# Welder_PSU.net
KiCad netlist of a schematic drawn in EAGLE
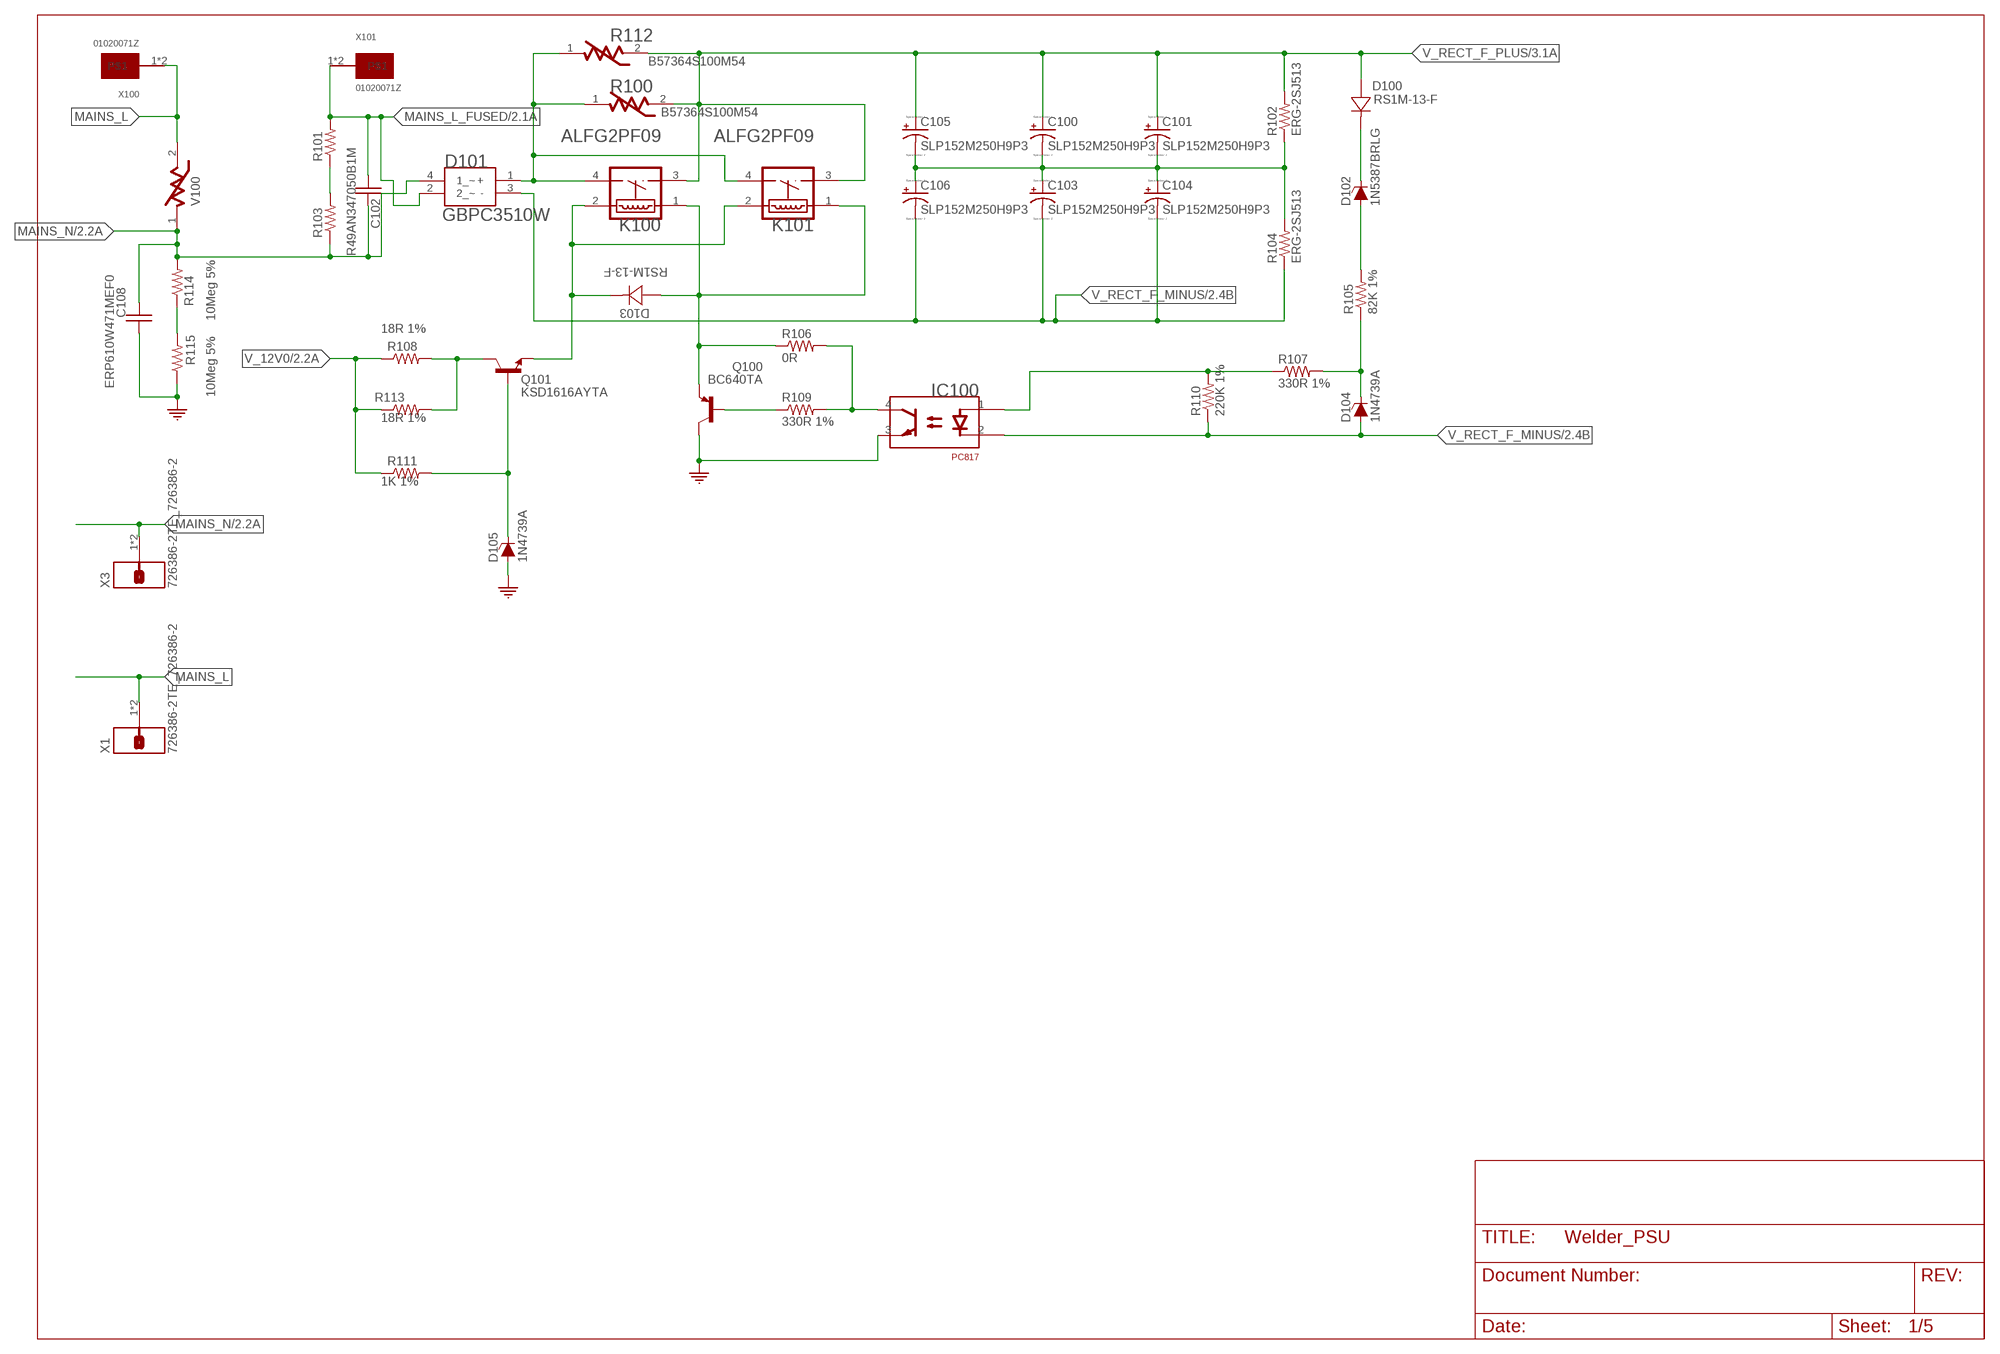
[diagram p0: schematic, sheet 1]
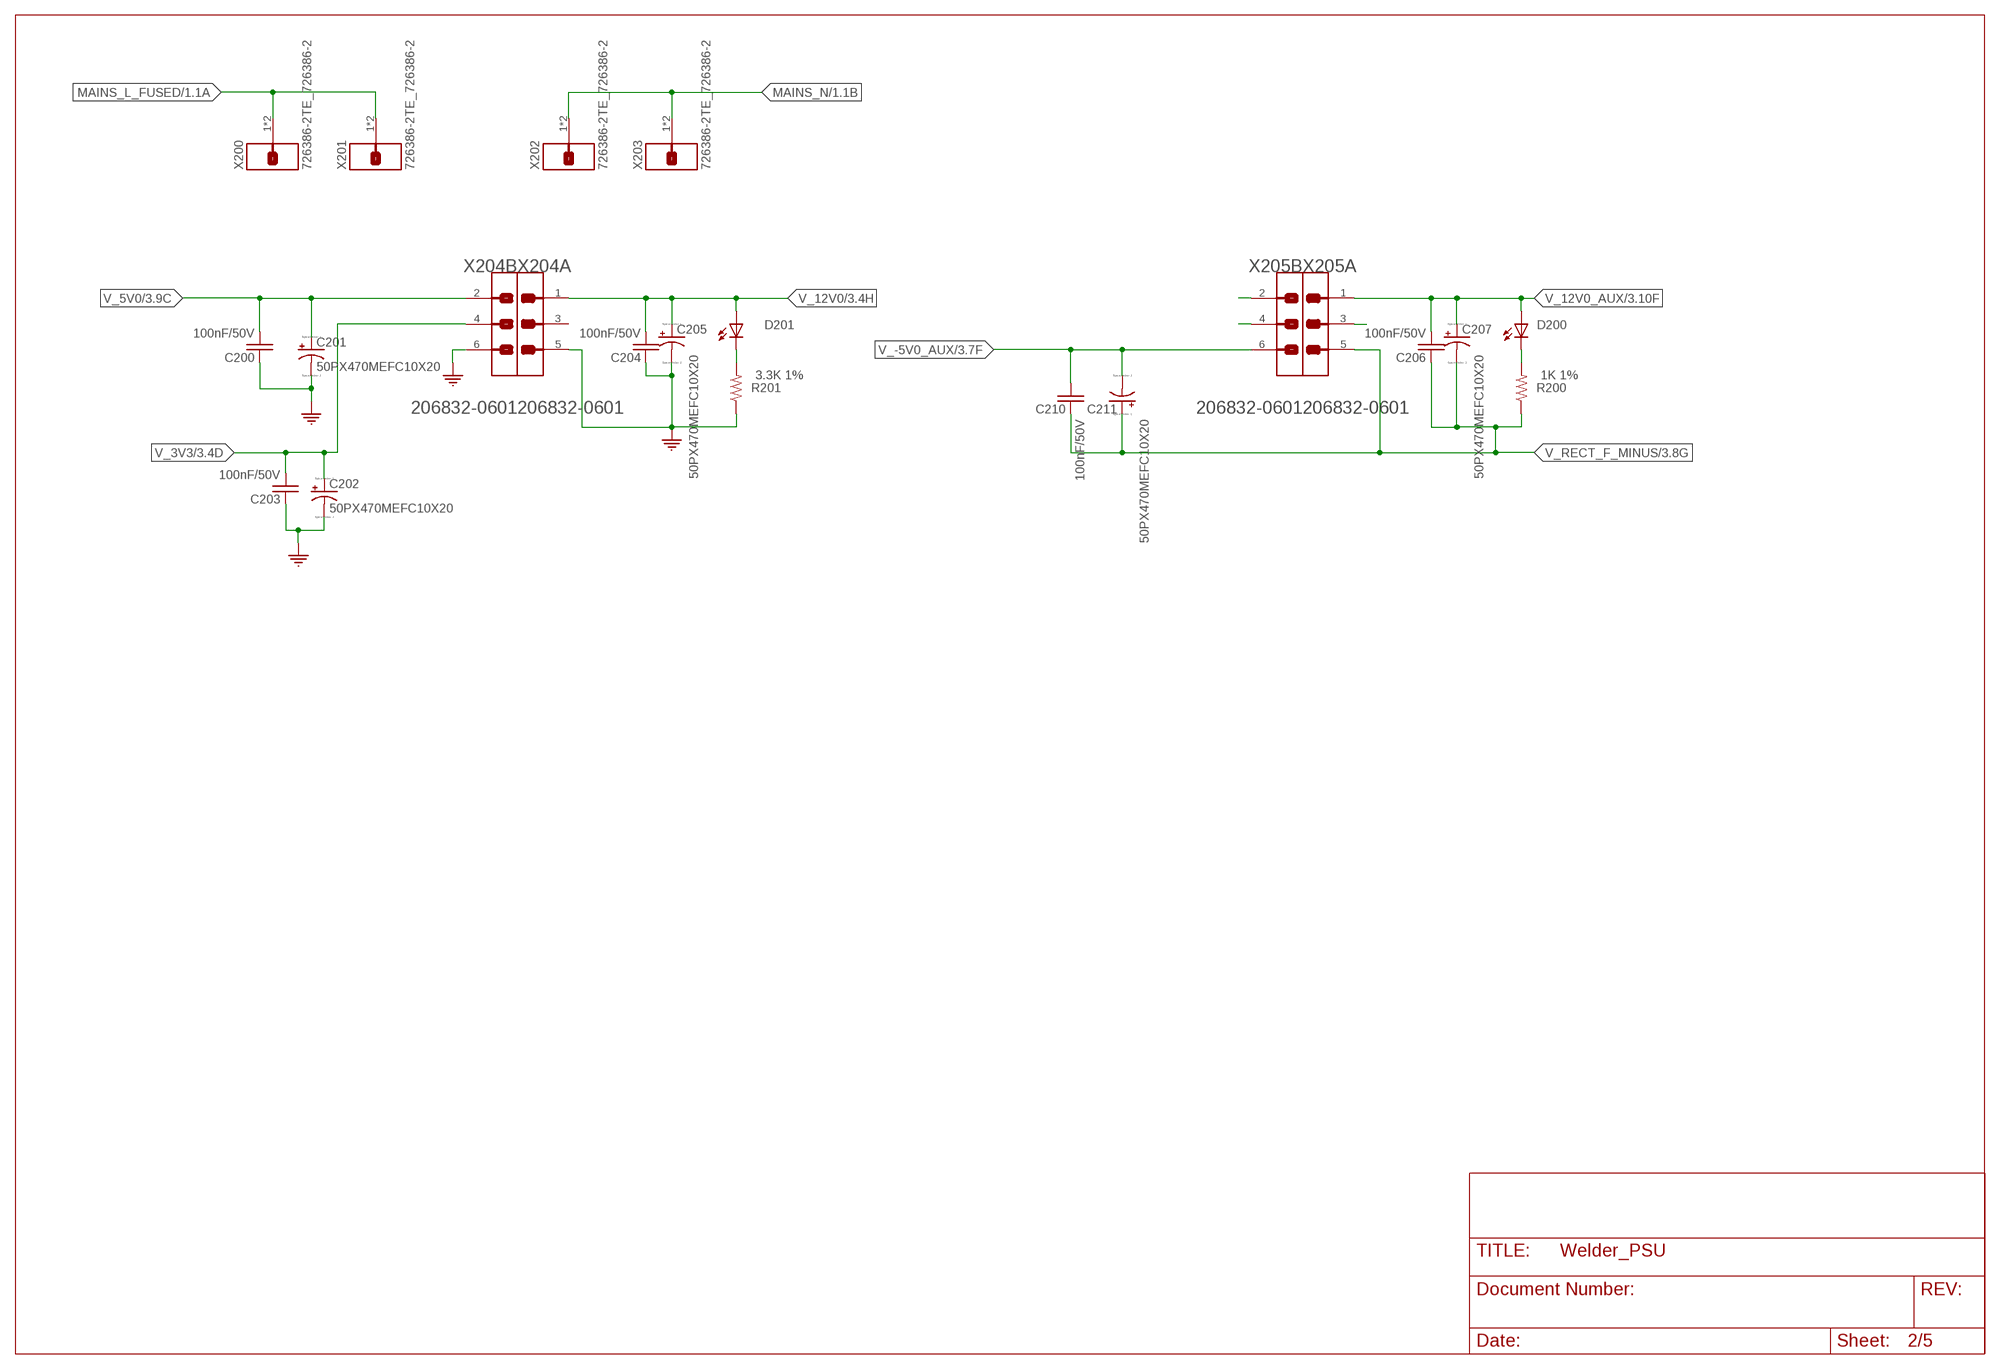
[diagram p1: schematic, sheet 2]
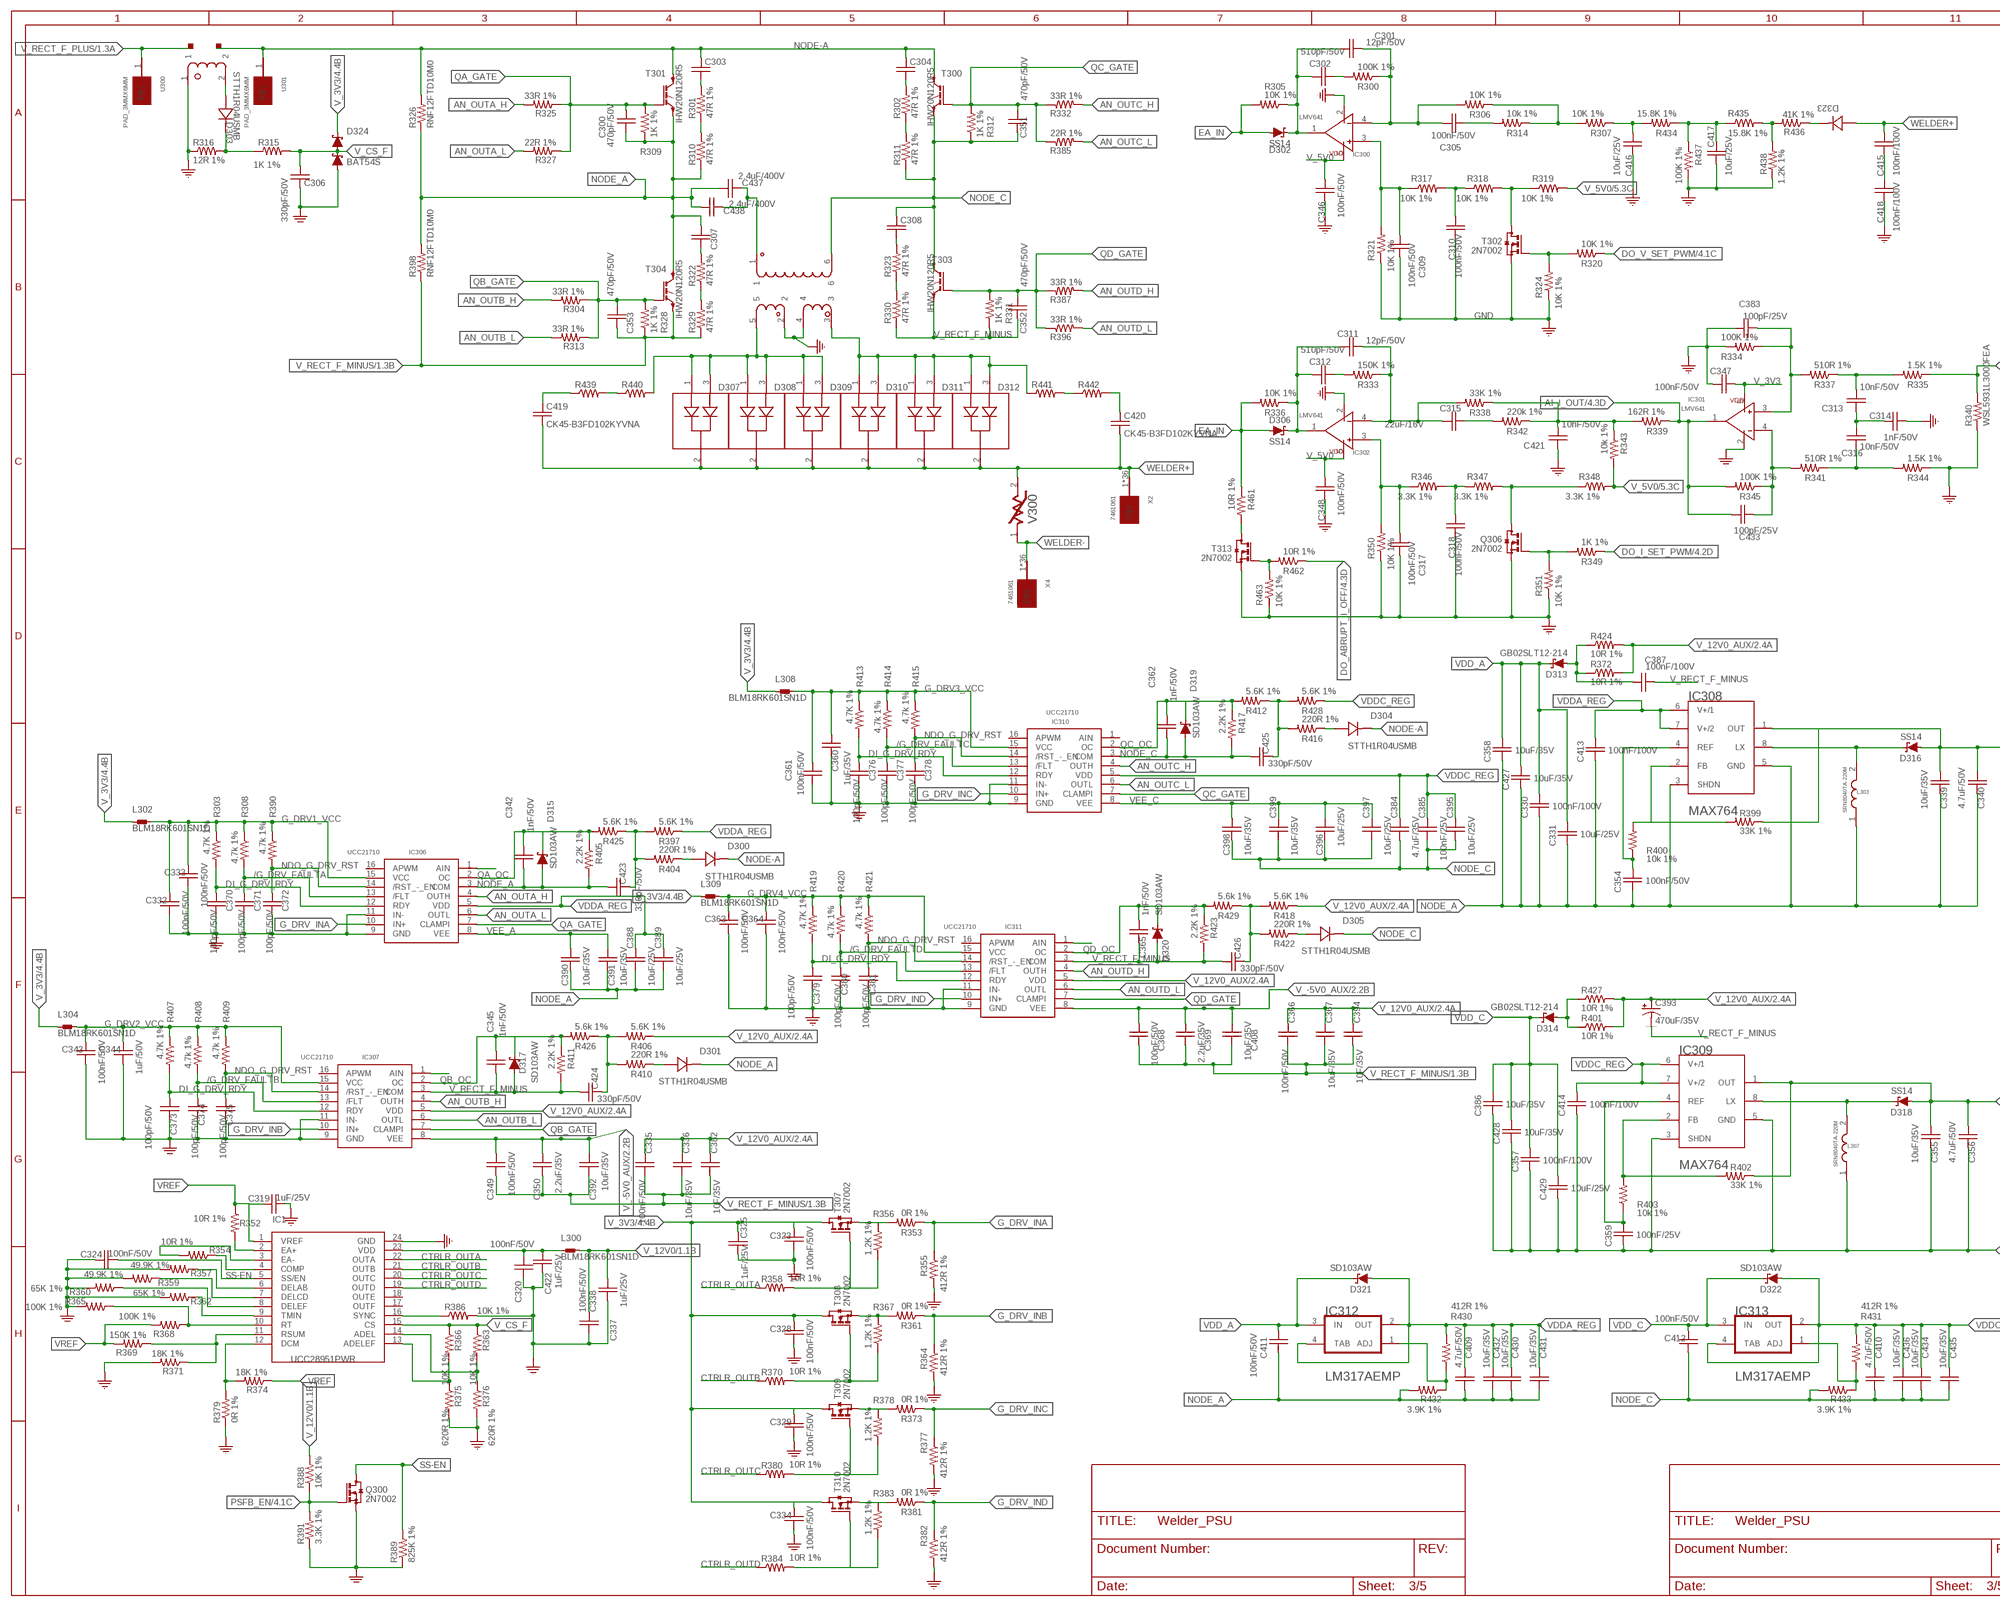
[diagram p2: schematic, sheet 3, part 1 of 2]
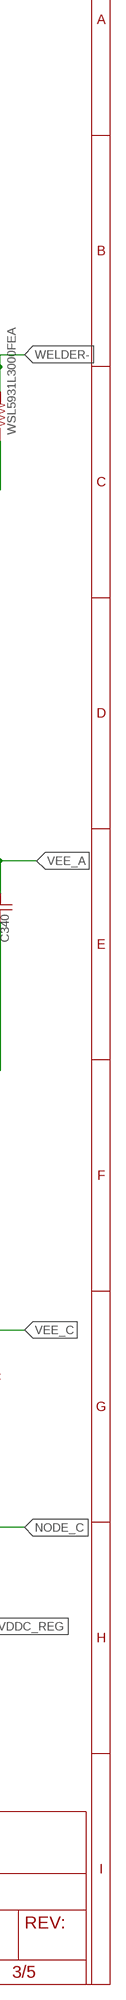
[diagram p3: schematic, sheet 3, part 2 of 2]
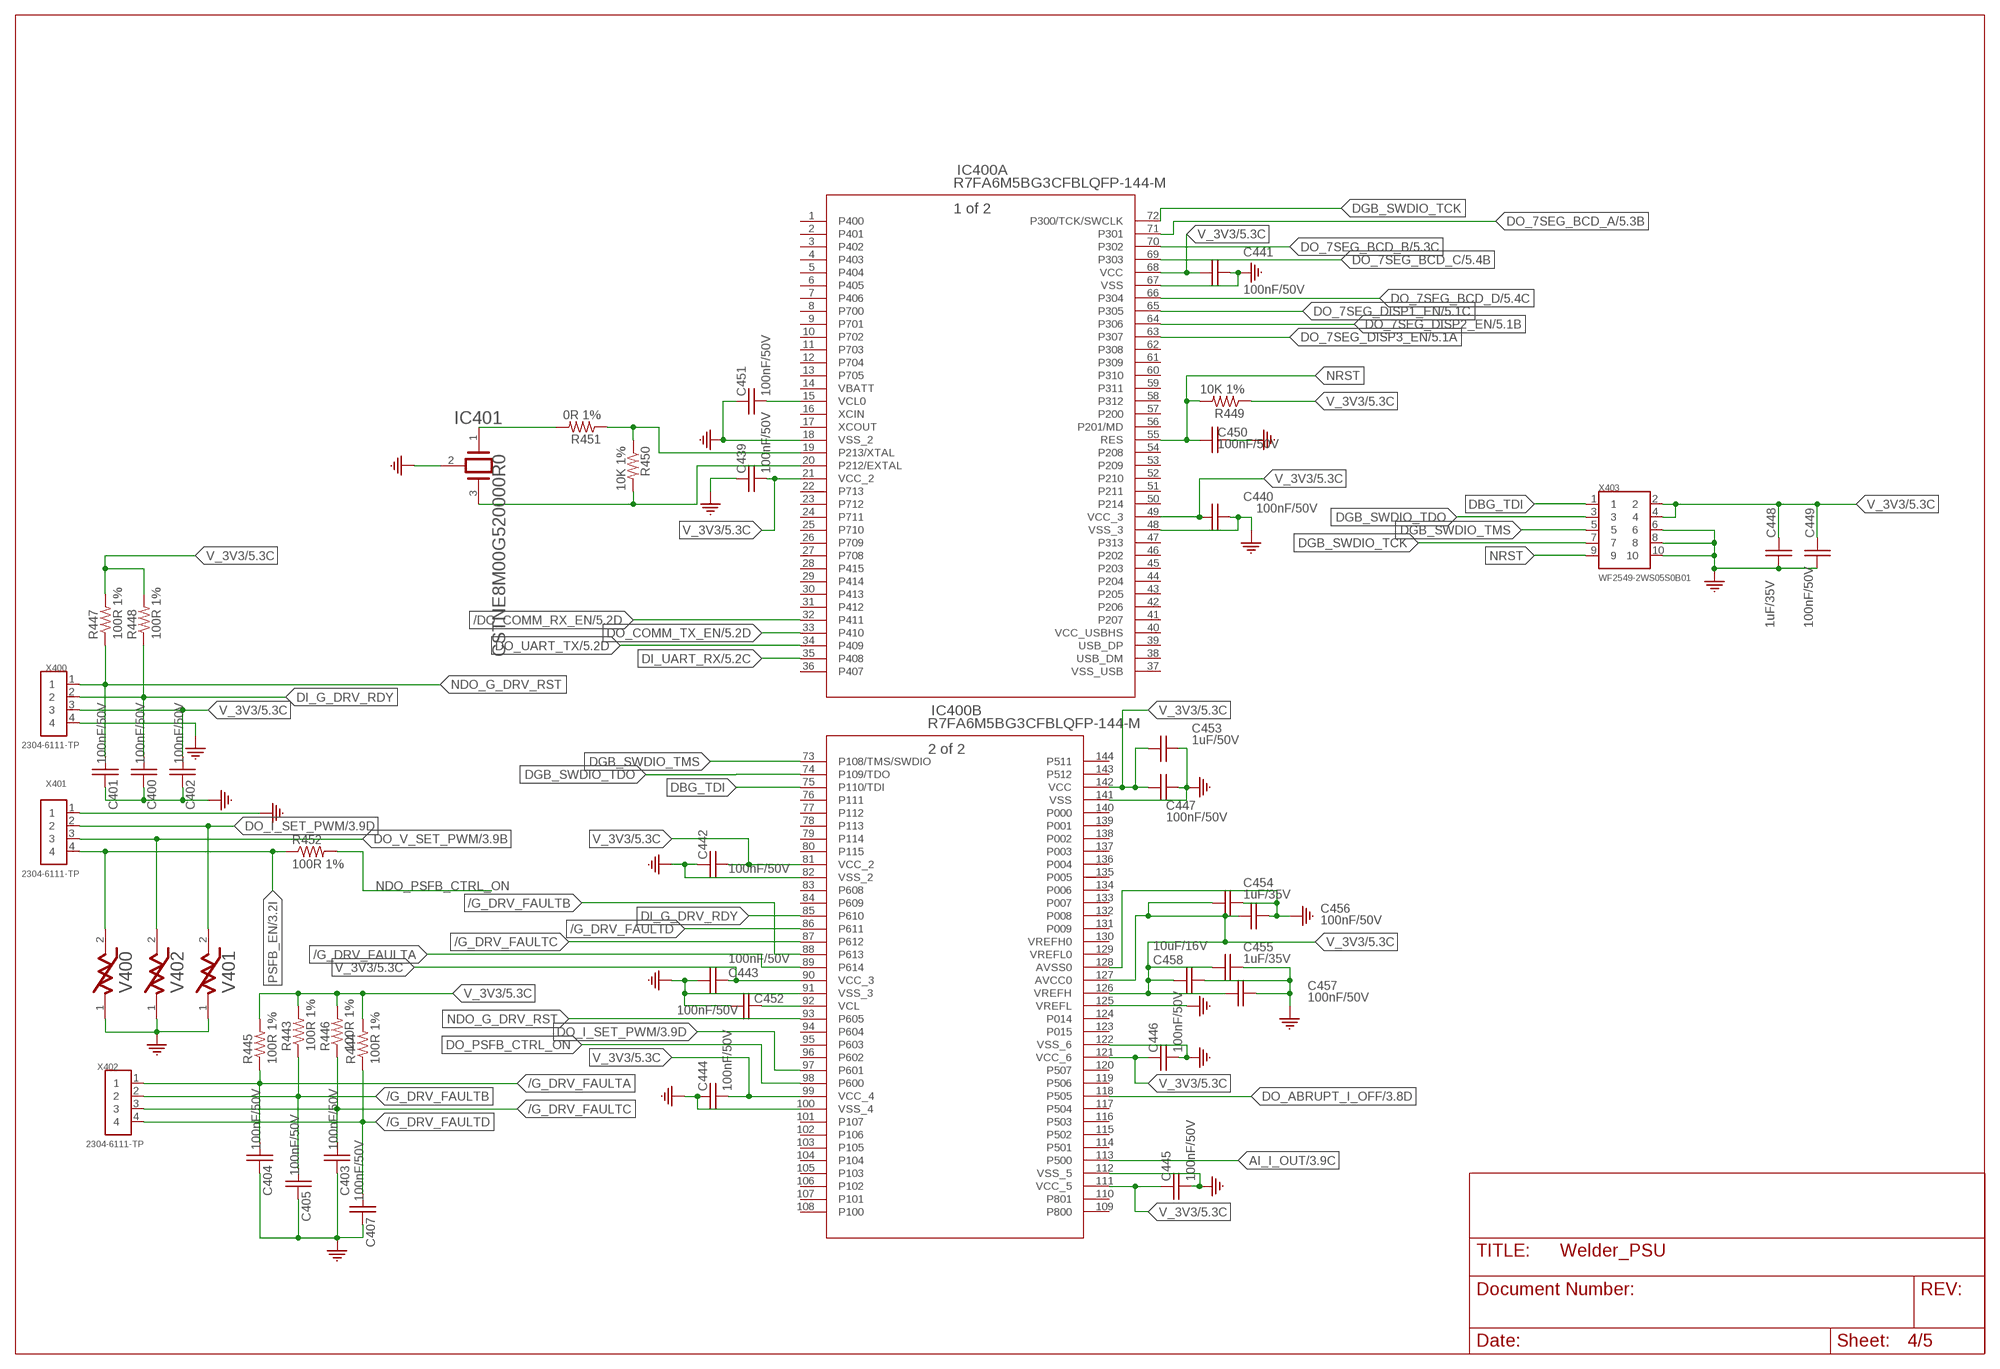
[diagram p4: schematic, sheet 4]
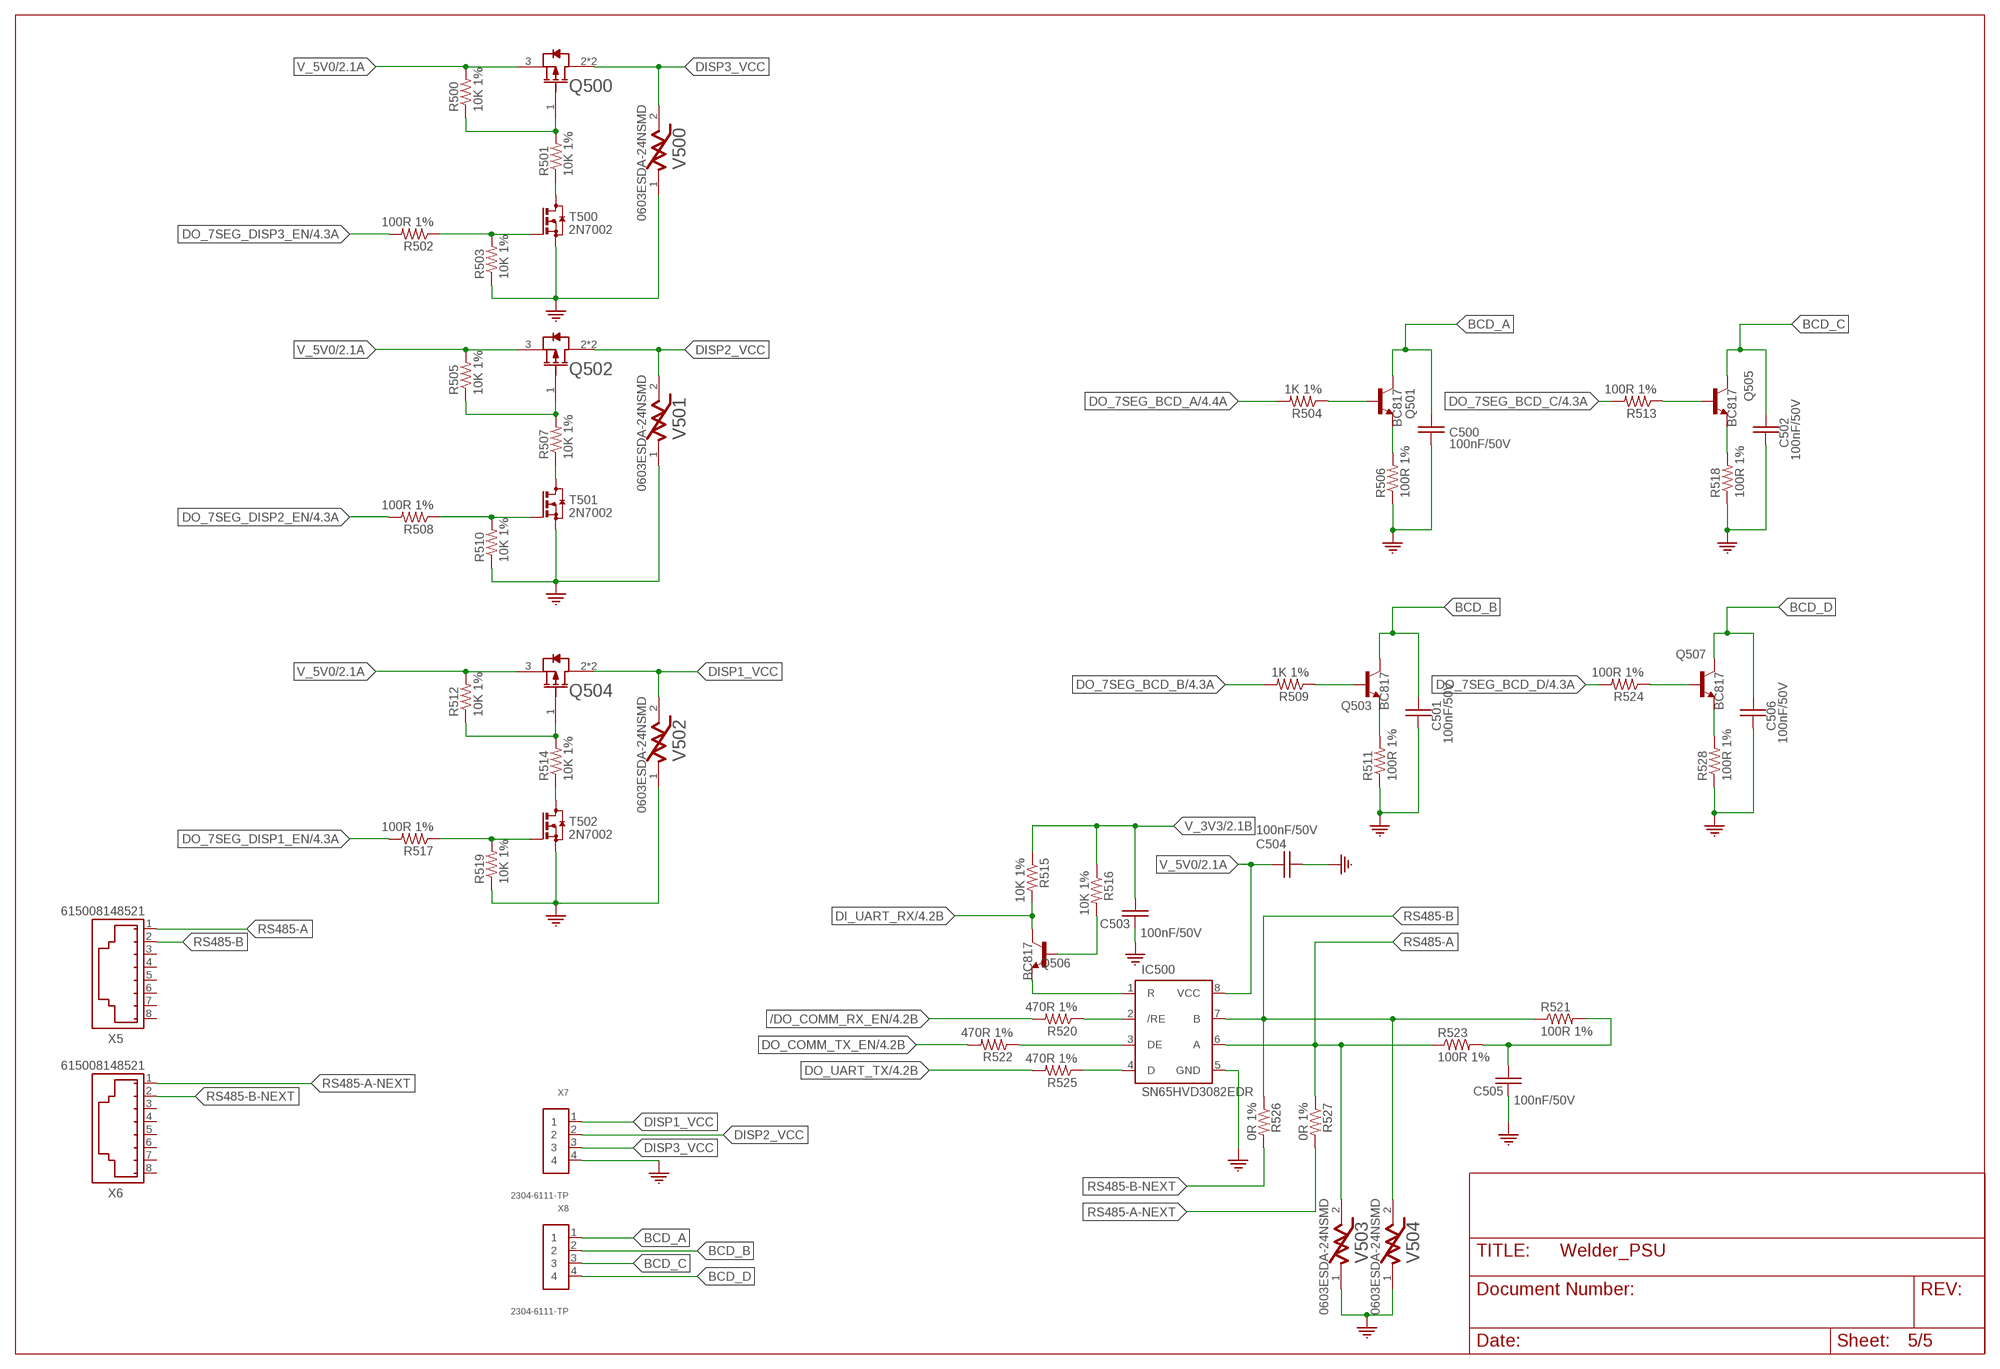
[diagram p5: schematic, sheet 5]

(export (version "E")
  (design (tool "Eeschema 10.0.6"))
  (components
    (comp (ref "C400")
      (value "100nF/50V")
      (footprint "eagle-import:EIA0603")
      (libsource (lib "eagle-import") (part "C_0603EIA0603"))
    )
    (comp (ref "C401")
      (value "100nF/50V")
      (footprint "eagle-import:EIA0603")
      (libsource (lib "eagle-import") (part "C_0603EIA0603"))
    )
    (comp (ref "C402")
      (value "100nF/50V")
      (footprint "eagle-import:EIA0603")
      (libsource (lib "eagle-import") (part "C_0603EIA0603"))
    )
    (comp (ref "C403")
      (value "100nF/50V")
      (footprint "eagle-import:EIA0603")
      (libsource (lib "eagle-import") (part "C_0603EIA0603"))
    )
    (comp (ref "C404")
      (value "100nF/50V")
      (footprint "eagle-import:EIA0603")
      (libsource (lib "eagle-import") (part "C_0603EIA0603"))
    )
    (comp (ref "C405")
      (value "100nF/50V")
      (footprint "eagle-import:EIA0603")
      (libsource (lib "eagle-import") (part "C_0603EIA0603"))
    )
    (comp (ref "C407")
      (value "100nF/50V")
      (footprint "eagle-import:EIA0603")
      (libsource (lib "eagle-import") (part "C_0603EIA0603"))
    )
    (comp (ref "C439")
      (value "100nF/50V")
      (footprint "eagle-import:EIA0603")
      (libsource (lib "eagle-import") (part "C_0603EIA0603"))
    )
    (comp (ref "C440")
      (value "100nF/50V")
      (footprint "eagle-import:EIA0603")
      (libsource (lib "eagle-import") (part "C_0603EIA0603"))
    )
    (comp (ref "C441")
      (value "100nF/50V")
      (footprint "eagle-import:EIA0603")
      (libsource (lib "eagle-import") (part "C_0603EIA0603"))
    )
    (comp (ref "C442")
      (value "100nF/50V")
      (footprint "eagle-import:EIA0603")
      (libsource (lib "eagle-import") (part "C_0603EIA0603"))
    )
    (comp (ref "C443")
      (value "100nF/50V")
      (footprint "eagle-import:EIA0603")
      (libsource (lib "eagle-import") (part "C_0603EIA0603"))
    )
    (comp (ref "C444")
      (value "100nF/50V")
      (footprint "eagle-import:EIA0603")
      (libsource (lib "eagle-import") (part "C_0603EIA0603"))
    )
    (comp (ref "C445")
      (value "100nF/50V")
      (footprint "eagle-import:EIA0603")
      (libsource (lib "eagle-import") (part "C_0603EIA0603"))
    )
    (comp (ref "C446")
      (value "100nF/50V")
      (footprint "eagle-import:EIA0603")
      (libsource (lib "eagle-import") (part "C_0603EIA0603"))
    )
    (comp (ref "C447")
      (value "100nF/50V")
      (footprint "eagle-import:EIA0603")
      (libsource (lib "eagle-import") (part "C_0603EIA0603"))
    )
    (comp (ref "C448")
      (value "1uF/35V")
      (footprint "eagle-import:EIA0603")
      (libsource (lib "eagle-import") (part "C_0603EIA0603"))
    )
    (comp (ref "C449")
      (value "100nF/50V")
      (footprint "eagle-import:EIA0603")
      (libsource (lib "eagle-import") (part "C_0603EIA0603"))
    )
    (comp (ref "C450")
      (value "100nF/50V")
      (footprint "eagle-import:EIA0603")
      (libsource (lib "eagle-import") (part "C_0603EIA0603"))
    )
    (comp (ref "C451")
      (value "100nF/50V")
      (footprint "eagle-import:EIA0603")
      (libsource (lib "eagle-import") (part "C_0603EIA0603"))
    )
    (comp (ref "C452")
      (value "100nF/50V")
      (footprint "eagle-import:EIA0603")
      (libsource (lib "eagle-import") (part "C_0603EIA0603"))
    )
    (comp (ref "C453")
      (value "1uF/50V")
      (footprint "eagle-import:EIA0603")
      (libsource (lib "eagle-import") (part "C_0603EIA0603"))
    )
    (comp (ref "C454")
      (value "1uF/35V")
      (footprint "eagle-import:EIA0603")
      (libsource (lib "eagle-import") (part "C_0603EIA0603"))
    )
    (comp (ref "C455")
      (value "1uF/35V")
      (footprint "eagle-import:EIA0603")
      (libsource (lib "eagle-import") (part "C_0603EIA0603"))
    )
    (comp (ref "C456")
      (value "100nF/50V")
      (footprint "eagle-import:EIA0603")
      (libsource (lib "eagle-import") (part "C_0603EIA0603"))
    )
    (comp (ref "C457")
      (value "100nF/50V")
      (footprint "eagle-import:EIA0603")
      (libsource (lib "eagle-import") (part "C_0603EIA0603"))
    )
    (comp (ref "C458")
      (value "10uF/16V")
      (footprint "eagle-import:EIA0603")
      (libsource (lib "eagle-import") (part "C_0603EIA0603"))
    )
    (comp (ref "IC400")
      (value "R7FA6M5BG3CFBLQFP-144-M")
      (footprint "eagle-import:LQFP-144-M")
      (fields (field (name "MFR") "Renesas"))
      (libsource (lib "eagle-import") (part "R7FA6M5BG3CFBLQFP-144-M"))
    )
    (comp (ref "IC401")
      (value "CSTNE8M00G520000R0")
      (footprint "eagle-import:CSTNE8M00G520000R0")
      (fields (field (name "MFR") "Murata"))
      (libsource (lib "eagle-import") (part "CSTNE8M00G520000R0"))
    )
    (comp (ref "R443")
      (value "100R 1%")
      (footprint "eagle-import:EIA0603")
      (libsource (lib "eagle-import") (part "R_0603"))
    )
    (comp (ref "R444")
      (value "100R 1%")
      (footprint "eagle-import:EIA0603")
      (libsource (lib "eagle-import") (part "R_0603"))
    )
    (comp (ref "R445")
      (value "100R 1%")
      (footprint "eagle-import:EIA0603")
      (libsource (lib "eagle-import") (part "R_0603"))
    )
    (comp (ref "R446")
      (value "100R 1%")
      (footprint "eagle-import:EIA0603")
      (libsource (lib "eagle-import") (part "R_0603"))
    )
    (comp (ref "R447")
      (value "100R 1%")
      (footprint "eagle-import:EIA0603")
      (libsource (lib "eagle-import") (part "R_0603"))
    )
    (comp (ref "R448")
      (value "100R 1%")
      (footprint "eagle-import:EIA0603")
      (libsource (lib "eagle-import") (part "R_0603"))
    )
    (comp (ref "R449")
      (value "10K 1%")
      (footprint "eagle-import:EIA0603")
      (libsource (lib "eagle-import") (part "R_0603"))
    )
    (comp (ref "R450")
      (value "10K 1%")
      (footprint "eagle-import:EIA0603")
      (libsource (lib "eagle-import") (part "R_0603"))
    )
    (comp (ref "R451")
      (value "0R 1%")
      (footprint "eagle-import:EIA0603")
      (libsource (lib "eagle-import") (part "R_0603"))
    )
    (comp (ref "R452")
      (value "100R 1%")
      (footprint "eagle-import:EIA0603")
      (libsource (lib "eagle-import") (part "R_0603"))
    )
    (comp (ref "V400")
      (value "0603ESDA-24NSMD")
      (footprint "eagle-import:EIA0603")
      (fields (field (name "MFR") "Bourns"))
      (libsource (lib "eagle-import") (part "0603ESDA-24NSMD"))
    )
    (comp (ref "V401")
      (value "0603ESDA-24NSMD")
      (footprint "eagle-import:EIA0603")
      (fields (field (name "MFR") "Bourns"))
      (libsource (lib "eagle-import") (part "0603ESDA-24NSMD"))
    )
    (comp (ref "V402")
      (value "0603ESDA-24NSMD")
      (footprint "eagle-import:EIA0603")
      (fields (field (name "MFR") "Bourns"))
      (libsource (lib "eagle-import") (part "0603ESDA-24NSMD"))
    )
    (comp (ref "X400")
      (value "2304-6111-TP")
      (footprint "eagle-import:X04_100MIL")
      (fields (field (name "MFR") "3M"))
      (libsource (lib "eagle-import") (part "2304-6111-TP"))
    )
    (comp (ref "X401")
      (value "2304-6111-TP")
      (footprint "eagle-import:X04_100MIL")
      (fields (field (name "MFR") "3M"))
      (libsource (lib "eagle-import") (part "2304-6111-TP"))
    )
    (comp (ref "X402")
      (value "2304-6111-TP")
      (footprint "eagle-import:X04_100MIL")
      (fields (field (name "MFR") "3M"))
      (libsource (lib "eagle-import") (part "2304-6111-TP"))
    )
    (comp (ref "X403")
      (value "WF2549-2WS05S0B01")
      (footprint "eagle-import:X10_100MIL_2XROW_VERT")
      (fields (field (name "MFR") "WCON"))
      (libsource (lib "eagle-import") (part "WF2549-2WS05S0B01"))
    )
    (comp (ref "C200")
      (value "100nF/50V")
      (footprint "eagle-import:EIA0603")
      (libsource (lib "eagle-import") (part "C_0603EIA0603"))
    )
    (comp (ref "C201")
      (value "50PX470MEFC10X20")
      (footprint "eagle-import:CAPACITOR-ELKO-RM5-10X16")
      (fields (field (name "MFR") "Rubicon"))
      (libsource (lib "eagle-import") (part "50PX470MEFC10X20"))
    )
    (comp (ref "C202")
      (value "50PX470MEFC10X20")
      (footprint "eagle-import:CAPACITOR-ELKO-RM5-10X16")
      (fields (field (name "MFR") "Rubicon"))
      (libsource (lib "eagle-import") (part "50PX470MEFC10X20"))
    )
    (comp (ref "C203")
      (value "100nF/50V")
      (footprint "eagle-import:EIA0603")
      (libsource (lib "eagle-import") (part "C_0603EIA0603"))
    )
    (comp (ref "C204")
      (value "100nF/50V")
      (footprint "eagle-import:EIA0603")
      (libsource (lib "eagle-import") (part "C_0603EIA0603"))
    )
    (comp (ref "C205")
      (value "50PX470MEFC10X20")
      (footprint "eagle-import:CAPACITOR-ELKO-RM5-10X16")
      (fields (field (name "MFR") "Rubicon"))
      (libsource (lib "eagle-import") (part "50PX470MEFC10X20"))
    )
    (comp (ref "C206")
      (value "100nF/50V")
      (footprint "eagle-import:EIA0603")
      (libsource (lib "eagle-import") (part "C_0603EIA0603"))
    )
    (comp (ref "C207")
      (value "50PX470MEFC10X20")
      (footprint "eagle-import:CAPACITOR-ELKO-RM5-10X16")
      (fields (field (name "MFR") "Rubicon"))
      (libsource (lib "eagle-import") (part "50PX470MEFC10X20"))
    )
    (comp (ref "C210")
      (value "100nF/50V")
      (footprint "eagle-import:EIA0603")
      (libsource (lib "eagle-import") (part "C_0603EIA0603"))
    )
    (comp (ref "C211")
      (value "50PX470MEFC10X20")
      (footprint "eagle-import:CAPACITOR-ELKO-RM5-10X16")
      (fields (field (name "MFR") "Rubicon"))
      (libsource (lib "eagle-import") (part "50PX470MEFC10X20"))
    )
    (comp (ref "D200")
      (value "26-21/GPC-F3138B/CA")
      (footprint "eagle-import:SMD1206-LED")
      (fields (field (name "MFR") "Everlight"))
      (libsource (lib "eagle-import") (part "26-21/GPC-F3138B/CA"))
    )
    (comp (ref "D201")
      (value "26-21/GPC-F3138B/CA")
      (footprint "eagle-import:SMD1206-LED")
      (fields (field (name "MFR") "Everlight"))
      (libsource (lib "eagle-import") (part "26-21/GPC-F3138B/CA"))
    )
    (comp (ref "R200")
      (value "1K 1%")
      (footprint "eagle-import:EIA0603")
      (libsource (lib "eagle-import") (part "R_0603"))
    )
    (comp (ref "R201")
      (value "3.3K 1%")
      (footprint "eagle-import:EIA0603")
      (libsource (lib "eagle-import") (part "R_0603"))
    )
    (comp (ref "X200")
      (value "726386-2TE_726386-2")
      (footprint "eagle-import:TE_726386-2")
      (fields
        (field (name "DIGIKEY_PART_NUMBER") "A114371-ND")
        (field (name "MF") "TE")
        (field (name "MOUSER_PART_NUMBER") "571-726386-2")
      )
      (libsource (lib "eagle-import") (part "726386-2TE_726386-2"))
    )
    (comp (ref "X201")
      (value "726386-2TE_726386-2")
      (footprint "eagle-import:TE_726386-2")
      (fields
        (field (name "DIGIKEY_PART_NUMBER") "A114371-ND")
        (field (name "MF") "TE")
        (field (name "MOUSER_PART_NUMBER") "571-726386-2")
      )
      (libsource (lib "eagle-import") (part "726386-2TE_726386-2"))
    )
    (comp (ref "X202")
      (value "726386-2TE_726386-2")
      (footprint "eagle-import:TE_726386-2")
      (fields
        (field (name "DIGIKEY_PART_NUMBER") "A114371-ND")
        (field (name "MF") "TE")
        (field (name "MOUSER_PART_NUMBER") "571-726386-2")
      )
      (libsource (lib "eagle-import") (part "726386-2TE_726386-2"))
    )
    (comp (ref "X203")
      (value "726386-2TE_726386-2")
      (footprint "eagle-import:TE_726386-2")
      (fields
        (field (name "DIGIKEY_PART_NUMBER") "A114371-ND")
        (field (name "MF") "TE")
        (field (name "MOUSER_PART_NUMBER") "571-726386-2")
      )
      (libsource (lib "eagle-import") (part "726386-2TE_726386-2"))
    )
    (comp (ref "X204")
      (value "MOLEX_206832-0601MOLEX_206832-0601")
      (footprint "eagle-import:MOLEX_206832-0601")
      (fields (field (name "MFR") "Molex"))
      (libsource (lib "eagle-import") (part "MOLEX_206832-0601MOLEX_206832-0601"))
    )
    (comp (ref "X205")
      (value "MOLEX_206832-0601MOLEX_206832-0601")
      (footprint "eagle-import:MOLEX_206832-0601")
      (fields (field (name "MFR") "Molex"))
      (libsource (lib "eagle-import") (part "MOLEX_206832-0601MOLEX_206832-0601"))
    )
    (comp (ref "C100")
      (value "SLP152M250H9P3")
      (footprint "eagle-import:CAPACITOR-ELKO-400V-RM10-35X50")
      (fields (field (name "MFR") "Cornell"))
      (libsource (lib "eagle-import") (part "SLP152M250H9P3"))
    )
    (comp (ref "C101")
      (value "SLP152M250H9P3")
      (footprint "eagle-import:CAPACITOR-ELKO-400V-RM10-35X50")
      (fields (field (name "MFR") "Cornell"))
      (libsource (lib "eagle-import") (part "SLP152M250H9P3"))
    )
    (comp (ref "C102")
      (value "R49AN347050B1M")
      (footprint "eagle-import:R49AN347050B1M")
      (fields (field (name "MFR") "Kemet"))
      (libsource (lib "eagle-import") (part "R49AN347050B1M"))
    )
    (comp (ref "C103")
      (value "SLP152M250H9P3")
      (footprint "eagle-import:CAPACITOR-ELKO-400V-RM10-35X50")
      (fields (field (name "MFR") "Cornell"))
      (libsource (lib "eagle-import") (part "SLP152M250H9P3"))
    )
    (comp (ref "C104")
      (value "SLP152M250H9P3")
      (footprint "eagle-import:CAPACITOR-ELKO-400V-RM10-35X50")
      (fields (field (name "MFR") "Cornell"))
      (libsource (lib "eagle-import") (part "SLP152M250H9P3"))
    )
    (comp (ref "C105")
      (value "SLP152M250H9P3")
      (footprint "eagle-import:CAPACITOR-ELKO-400V-RM10-35X50")
      (fields (field (name "MFR") "Cornell"))
      (libsource (lib "eagle-import") (part "SLP152M250H9P3"))
    )
    (comp (ref "C106")
      (value "SLP152M250H9P3")
      (footprint "eagle-import:CAPACITOR-ELKO-400V-RM10-35X50")
      (fields (field (name "MFR") "Cornell"))
      (libsource (lib "eagle-import") (part "SLP152M250H9P3"))
    )
    (comp (ref "C108")
      (value "ERP610W471MEF0")
      (footprint "eagle-import:CAPACITOR-FILM-RM12.5MM-12MM")
      (fields (field (name "MFR") "Vishay"))
      (libsource (lib "eagle-import") (part "ERP610W471MEF0"))
    )
    (comp (ref "D100")
      (value "RS1M-13-F")
      (footprint "eagle-import:SMA-DIODE")
      (fields (field (name "MFR") "Diodes") (field (name "PART_VALUE") "RS1M-13-F"))
      (libsource (lib "eagle-import") (part "RS1M-13-F"))
    )
    (comp (ref "D101")
      (value "GBPC3510W")
      (footprint "eagle-import:GBPC3510W")
      (libsource (lib "eagle-import") (part "GBPC3510W"))
    )
    (comp (ref "D102")
      (value "1N5387BRLG")
      (footprint "eagle-import:DO-201AD")
      (fields (field (name "MFR") "On Semi"))
      (libsource (lib "eagle-import") (part "1N5387BRLG"))
    )
    (comp (ref "D103")
      (value "RS1M-13-F")
      (footprint "eagle-import:SMA-DIODE")
      (fields (field (name "MFR") "Diodes"))
      (libsource (lib "eagle-import") (part "RS1M-13-F"))
    )
    (comp (ref "D104")
      (value "1N4739A")
      (footprint "eagle-import:DO-201AD")
      (libsource (lib "eagle-import") (part "1N4739A"))
    )
    (comp (ref "D105")
      (value "1N4739A")
      (footprint "eagle-import:DO-201AD")
      (libsource (lib "eagle-import") (part "1N4739A"))
    )
    (comp (ref "IC100")
      (value "PC817")
      (footprint "eagle-import:DIP04")
      (fields (field (name "MFR") "Sharp, UTC"))
      (libsource (lib "eagle-import") (part "PC817"))
    )
    (comp (ref "K100")
      (value "PANASONIC_ALFG2PF09PANASONIC_ALFG2PF09_0_0")
      (footprint "eagle-import:PANASONIC_ALFG2PF09_0")
      (fields (field (name "MF") "Panasonic") (field (name "MPN") "ALFG2PF09"))
      (libsource (lib "eagle-import") (part "PANASONIC_ALFG2PF09PANASONIC_ALFG2PF09_0_0"))
    )
    (comp (ref "K101")
      (value "PANASONIC_ALFG2PF09PANASONIC_ALFG2PF09_0_0")
      (footprint "eagle-import:PANASONIC_ALFG2PF09_0")
      (fields (field (name "MF") "Panasonic") (field (name "MPN") "ALFG2PF09"))
      (libsource (lib "eagle-import") (part "PANASONIC_ALFG2PF09PANASONIC_ALFG2PF09_0_0"))
    )
    (comp (ref "Q100")
      (value "BC640TA")
      (footprint "eagle-import:TO-92")
      (fields (field (name "MFR") "On Semi, "))
      (libsource (lib "eagle-import") (part "BC640TA"))
    )
    (comp (ref "Q101")
      (value "KSD1616AYTA")
      (footprint "eagle-import:TO-92")
      (fields (field (name "MFR") "On Semi"))
      (libsource (lib "eagle-import") (part "KSD1616AYTA"))
    )
    (comp (ref "R100")
      (value "B57364S100M54")
      (footprint "eagle-import:VARISTOR_D25_P7.5")
      (libsource (lib "eagle-import") (part "B57364S100M54"))
    )
    (comp (ref "R101")
      (value "R_1206EIA1206")
      (footprint "eagle-import:EIA1206")
      (libsource (lib "eagle-import") (part "R_1206EIA1206"))
    )
    (comp (ref "R102")
      (value "ERG-2SJ513")
      (footprint "eagle-import:ERG-2S")
      (fields (field (name "MFR") "Panasonic"))
      (libsource (lib "eagle-import") (part "ERG-2SJ513"))
    )
    (comp (ref "R103")
      (value "R_1206EIA1206")
      (footprint "eagle-import:EIA1206")
      (libsource (lib "eagle-import") (part "R_1206EIA1206"))
    )
    (comp (ref "R104")
      (value "ERG-2SJ513")
      (footprint "eagle-import:ERG-2S")
      (fields (field (name "MFR") "Panasonic"))
      (libsource (lib "eagle-import") (part "ERG-2SJ513"))
    )
    (comp (ref "R105")
      (value "82K 1%")
      (footprint "eagle-import:R2010")
      (libsource (lib "eagle-import") (part "R_2010"))
    )
    (comp (ref "R106")
      (value "0R")
      (footprint "eagle-import:EIA0603")
      (libsource (lib "eagle-import") (part "R_0603"))
    )
    (comp (ref "R107")
      (value "330R 1%")
      (footprint "eagle-import:EIA0603")
      (libsource (lib "eagle-import") (part "R_0603"))
    )
    (comp (ref "R108")
      (value "R_2010EIA2010")
      (footprint "eagle-import:EIA2010")
      (fields (field (name "PART_VALUE") "18R 1%"))
      (libsource (lib "eagle-import") (part "R_2010EIA2010"))
    )
    (comp (ref "R109")
      (value "330R 1%")
      (footprint "eagle-import:EIA0603")
      (libsource (lib "eagle-import") (part "R_0603"))
    )
    (comp (ref "R110")
      (value "220K 1%")
      (footprint "eagle-import:EIA0603")
      (libsource (lib "eagle-import") (part "R_0603"))
    )
    (comp (ref "R111")
      (value "R_1206EIA1206")
      (footprint "eagle-import:EIA1206")
      (fields (field (name "PART_VALUE") "1K 1%"))
      (libsource (lib "eagle-import") (part "R_1206EIA1206"))
    )
    (comp (ref "R112")
      (value "B57364S100M54")
      (footprint "eagle-import:VARISTOR_D25_P7.5")
      (libsource (lib "eagle-import") (part "B57364S100M54"))
    )
    (comp (ref "R113")
      (value "R_2010EIA2010")
      (footprint "eagle-import:EIA2010")
      (fields (field (name "PART_VALUE") "18R 1%"))
      (libsource (lib "eagle-import") (part "R_2010EIA2010"))
    )
    (comp (ref "R114")
      (value "RNF12FTD10M0")
      (footprint "eagle-import:RES-RM12.5-VR37")
      (fields (field (name "MFR") "Stackpole Electronics Inc") (field (name "PART_VALUE") "10Meg 5%"))
      (libsource (lib "eagle-import") (part "RNF12FTD10M0"))
    )
    (comp (ref "R115")
      (value "RNF12FTD10M0")
      (footprint "eagle-import:RES-RM12.5-VR37")
      (fields (field (name "MFR") "Stackpole Electronics Inc") (field (name "PART_VALUE") "10Meg 5%"))
      (libsource (lib "eagle-import") (part "RNF12FTD10M0"))
    )
    (comp (ref "V100")
      (value "B72205S0271K101B72205S2131K101")
      (footprint "eagle-import:EPCOS_B72205S0271K101_0")
      (fields (field (name "MFR") "EPCOS"))
      (libsource (lib "eagle-import") (part "B72205S0271K101B72205S2131K101"))
    )
    (comp (ref "X1")
      (value "726386-2TE_726386-2")
      (footprint "eagle-import:TE_726386-2")
      (fields
        (field (name "DIGIKEY_PART_NUMBER") "A114371-ND")
        (field (name "MF") "TE")
        (field (name "MOUSER_PART_NUMBER") "571-726386-2")
      )
      (libsource (lib "eagle-import") (part "726386-2TE_726386-2"))
    )
    (comp (ref "X3")
      (value "726386-2TE_726386-2")
      (footprint "eagle-import:TE_726386-2")
      (fields
        (field (name "DIGIKEY_PART_NUMBER") "A114371-ND")
        (field (name "MF") "TE")
        (field (name "MOUSER_PART_NUMBER") "571-726386-2")
      )
      (libsource (lib "eagle-import") (part "726386-2TE_726386-2"))
    )
    (comp (ref "X100")
      (value "01020071Z")
      (footprint "eagle-import:FUSE_CLIP_01020071Z")
      (fields (field (name "MFR") "LittleFuse"))
      (libsource (lib "eagle-import") (part "01020071Z"))
    )
    (comp (ref "X101")
      (value "01020071Z")
      (footprint "eagle-import:FUSE_CLIP_01020071Z")
      (fields (field (name "MFR") "LittleFuse"))
      (libsource (lib "eagle-import") (part "01020071Z"))
    )
    (comp (ref "C300")
      (value "470pF/50V")
      (footprint "eagle-import:EIA0603")
      (libsource (lib "eagle-import") (part "C_0603EIA0603"))
    )
    (comp (ref "C301")
      (value "12pF/50V")
      (footprint "eagle-import:EIA0603")
      (libsource (lib "eagle-import") (part "C_0603EIA0603"))
    )
    (comp (ref "C302")
      (value "510pF/50V")
      (footprint "eagle-import:EIA0603")
      (libsource (lib "eagle-import") (part "C_0603EIA0603"))
    )
    (comp (ref "C303")
      (value "HVCC153Y6P471MEAX")
      (footprint "eagle-import:CAPACITOR-FILM-RM12.5MM-12MM")
      (fields (field (name "MFR") "Vishay"))
      (libsource (lib "eagle-import") (part "HVCC153Y6P471MEAX"))
    )
    (comp (ref "C304")
      (value "HVCC153Y6P471MEAX")
      (footprint "eagle-import:CAPACITOR-FILM-RM12.5MM-12MM")
      (fields (field (name "MFR") "Vishay"))
      (libsource (lib "eagle-import") (part "HVCC153Y6P471MEAX"))
    )
    (comp (ref "C305")
      (value "100nF/50V")
      (footprint "eagle-import:EIA0603")
      (libsource (lib "eagle-import") (part "C_0603EIA0603"))
    )
    (comp (ref "C306")
      (value "330pF/50V")
      (footprint "eagle-import:EIA0603")
      (libsource (lib "eagle-import") (part "C_0603EIA0603"))
    )
    (comp (ref "C307")
      (value "HVCC153Y6P471MEAX")
      (footprint "eagle-import:CAPACITOR-FILM-RM12.5MM-12MM")
      (fields (field (name "MFR") "Vishay"))
      (libsource (lib "eagle-import") (part "HVCC153Y6P471MEAX"))
    )
    (comp (ref "C308")
      (value "HVCC153Y6P471MEAX")
      (footprint "eagle-import:CAPACITOR-FILM-RM12.5MM-12MM")
      (fields (field (name "MFR") "Vishay"))
      (libsource (lib "eagle-import") (part "HVCC153Y6P471MEAX"))
    )
    (comp (ref "C309")
      (value "100nF/50V")
      (footprint "eagle-import:EIA0603")
      (libsource (lib "eagle-import") (part "C_0603EIA0603"))
    )
    (comp (ref "C310")
      (value "100nF/50V")
      (footprint "eagle-import:EIA0603")
      (libsource (lib "eagle-import") (part "C_0603EIA0603"))
    )
    (comp (ref "C311")
      (value "12pF/50V")
      (footprint "eagle-import:EIA0603")
      (libsource (lib "eagle-import") (part "C_0603EIA0603"))
    )
    (comp (ref "C312")
      (value "510pF/50V")
      (footprint "eagle-import:EIA0603")
      (libsource (lib "eagle-import") (part "C_0603EIA0603"))
    )
    (comp (ref "C313")
      (value "10nF/50V")
      (footprint "eagle-import:EIA0603")
      (libsource (lib "eagle-import") (part "C_0603EIA0603"))
    )
    (comp (ref "C314")
      (value "1nF/50V")
      (footprint "eagle-import:EIA0603")
      (libsource (lib "eagle-import") (part "C_0603EIA0603"))
    )
    (comp (ref "C315")
      (value "22uF/16V")
      (footprint "eagle-import:EIA0603")
      (libsource (lib "eagle-import") (part "C_0603EIA0603"))
    )
    (comp (ref "C316")
      (value "10nF/50V")
      (footprint "eagle-import:EIA0603")
      (libsource (lib "eagle-import") (part "C_0603EIA0603"))
    )
    (comp (ref "C317")
      (value "100nF/50V")
      (footprint "eagle-import:EIA0603")
      (libsource (lib "eagle-import") (part "C_0603EIA0603"))
    )
    (comp (ref "C318")
      (value "100nF/50V")
      (footprint "eagle-import:EIA0603")
      (libsource (lib "eagle-import") (part "C_0603EIA0603"))
    )
    (comp (ref "C319")
      (value "1uF/25V")
      (footprint "eagle-import:EIA0603")
      (libsource (lib "eagle-import") (part "C_0603EIA0603"))
    )
    (comp (ref "C320")
      (value "100nF/50V")
      (footprint "eagle-import:EIA0603")
      (libsource (lib "eagle-import") (part "C_0603EIA0603"))
    )
    (comp (ref "C323")
      (value "100nF/50V")
      (footprint "eagle-import:EIA0603")
      (libsource (lib "eagle-import") (part "C_0603EIA0603"))
    )
    (comp (ref "C324")
      (value "100nF/50V")
      (footprint "eagle-import:EIA0603")
      (libsource (lib "eagle-import") (part "C_0603EIA0603"))
    )
    (comp (ref "C325")
      (value "1uF/25V")
      (footprint "eagle-import:EIA0603")
      (libsource (lib "eagle-import") (part "C_0603EIA0603"))
    )
    (comp (ref "C328")
      (value "100nF/50V")
      (footprint "eagle-import:EIA0603")
      (libsource (lib "eagle-import") (part "C_0603EIA0603"))
    )
    (comp (ref "C329")
      (value "100nF/50V")
      (footprint "eagle-import:EIA0603")
      (libsource (lib "eagle-import") (part "C_0603EIA0603"))
    )
    (comp (ref "C330")
      (value "100nF/100V")
      (footprint "eagle-import:EIA0603")
      (libsource (lib "eagle-import") (part "C_0603EIA0603"))
    )
    (comp (ref "C331")
      (value "10uF/25V")
      (footprint "eagle-import:EIA0603")
      (libsource (lib "eagle-import") (part "C_0603EIA0603"))
    )
    (comp (ref "C332")
      (value "100nF/50V")
      (footprint "eagle-import:EIA0603")
      (libsource (lib "eagle-import") (part "C_0603EIA0603"))
    )
    (comp (ref "C333")
      (value "100nF/50V")
      (footprint "eagle-import:EIA0603")
      (libsource (lib "eagle-import") (part "C_0603EIA0603"))
    )
    (comp (ref "C334")
      (value "100nF/50V")
      (footprint "eagle-import:EIA0603")
      (libsource (lib "eagle-import") (part "C_0603EIA0603"))
    )
    (comp (ref "C335")
      (value "100nF/50V")
      (footprint "eagle-import:EIA0603")
      (libsource (lib "eagle-import") (part "C_0603EIA0603"))
    )
    (comp (ref "C336")
      (value "10uF/35V")
      (footprint "eagle-import:EIA0603")
      (libsource (lib "eagle-import") (part "C_0603EIA0603"))
    )
    (comp (ref "C337")
      (value "1uF/25V")
      (footprint "eagle-import:EIA0603")
      (libsource (lib "eagle-import") (part "C_0603EIA0603"))
    )
    (comp (ref "C338")
      (value "100nF/50V")
      (footprint "eagle-import:EIA0603")
      (libsource (lib "eagle-import") (part "C_0603EIA0603"))
    )
    (comp (ref "C339")
      (value "10uF/35V")
      (footprint "eagle-import:EIA0603")
      (libsource (lib "eagle-import") (part "C_0603EIA0603"))
    )
    (comp (ref "C340")
      (value "4.7uF/50V")
      (footprint "eagle-import:EIA0603")
      (libsource (lib "eagle-import") (part "C_0603EIA0603"))
    )
    (comp (ref "C342")
      (value "1nF/50V")
      (footprint "eagle-import:EIA0603")
      (libsource (lib "eagle-import") (part "C_0603EIA0603"))
    )
    (comp (ref "C343")
      (value "100nF/50V")
      (footprint "eagle-import:EIA0603")
      (libsource (lib "eagle-import") (part "C_0603EIA0603"))
    )
    (comp (ref "C344")
      (value "1uF/50V")
      (footprint "eagle-import:EIA0603")
      (libsource (lib "eagle-import") (part "C_0603EIA0603"))
    )
    (comp (ref "C345")
      (value "1nF/50V")
      (footprint "eagle-import:EIA0603")
      (libsource (lib "eagle-import") (part "C_0603EIA0603"))
    )
    (comp (ref "C346")
      (value "100nF/50V")
      (footprint "eagle-import:EIA0603")
      (libsource (lib "eagle-import") (part "C_0603EIA0603"))
    )
    (comp (ref "C347")
      (value "100nF/50V")
      (footprint "eagle-import:EIA0603")
      (libsource (lib "eagle-import") (part "C_0603EIA0603"))
    )
    (comp (ref "C348")
      (value "100nF/50V")
      (footprint "eagle-import:EIA0603")
      (libsource (lib "eagle-import") (part "C_0603EIA0603"))
    )
    (comp (ref "C349")
      (value "100nF/50V")
      (footprint "eagle-import:EIA0603")
      (libsource (lib "eagle-import") (part "C_0603EIA0603"))
    )
    (comp (ref "C350")
      (value "2.2uF/35V")
      (footprint "eagle-import:EIA0603")
      (libsource (lib "eagle-import") (part "C_0603EIA0603"))
    )
    (comp (ref "C351")
      (value "470pF/50V")
      (footprint "eagle-import:EIA0603")
      (libsource (lib "eagle-import") (part "C_0603EIA0603"))
    )
    (comp (ref "C352")
      (value "470pF/50V")
      (footprint "eagle-import:EIA0603")
      (libsource (lib "eagle-import") (part "C_0603EIA0603"))
    )
    (comp (ref "C353")
      (value "470pF/50V")
      (footprint "eagle-import:EIA0603")
      (libsource (lib "eagle-import") (part "C_0603EIA0603"))
    )
    (comp (ref "C354")
      (value "100nF/50V")
      (footprint "eagle-import:EIA0603")
      (libsource (lib "eagle-import") (part "C_0603EIA0603"))
    )
    (comp (ref "C355")
      (value "10uF/35V")
      (footprint "eagle-import:EIA0603")
      (libsource (lib "eagle-import") (part "C_0603EIA0603"))
    )
    (comp (ref "C356")
      (value "4.7uF/50V")
      (footprint "eagle-import:EIA0603")
      (libsource (lib "eagle-import") (part "C_0603EIA0603"))
    )
    (comp (ref "C357")
      (value "100nF/100V")
      (footprint "eagle-import:EIA0603")
      (libsource (lib "eagle-import") (part "C_0603EIA0603"))
    )
    (comp (ref "C358")
      (value "10uF/35V")
      (footprint "eagle-import:EIA0603")
      (libsource (lib "eagle-import") (part "C_0603EIA0603"))
    )
    (comp (ref "C359")
      (value "100nF/25V")
      (footprint "eagle-import:EIA0603")
      (libsource (lib "eagle-import") (part "C_0603EIA0603"))
    )
    (comp (ref "C360")
      (value "1uF/35V")
      (footprint "eagle-import:EIA0603")
      (libsource (lib "eagle-import") (part "C_0603EIA0603"))
    )
    (comp (ref "C361")
      (value "100nF/50V")
      (footprint "eagle-import:EIA0603")
      (libsource (lib "eagle-import") (part "C_0603EIA0603"))
    )
    (comp (ref "C362")
      (value "1nF/50V")
      (footprint "eagle-import:EIA0603")
      (libsource (lib "eagle-import") (part "C_0603EIA0603"))
    )
    (comp (ref "C363")
      (value "100nF/50V")
      (footprint "eagle-import:EIA0603")
      (libsource (lib "eagle-import") (part "C_0603EIA0603"))
    )
    (comp (ref "C364")
      (value "100nF/50V")
      (footprint "eagle-import:EIA0603")
      (libsource (lib "eagle-import") (part "C_0603EIA0603"))
    )
    (comp (ref "C365")
      (value "1nF/50V")
      (footprint "eagle-import:EIA0603")
      (libsource (lib "eagle-import") (part "C_0603EIA0603"))
    )
    (comp (ref "C366")
      (value "100nF/50V")
      (footprint "eagle-import:EIA0603")
      (libsource (lib "eagle-import") (part "C_0603EIA0603"))
    )
    (comp (ref "C367")
      (value "10uF/35V")
      (footprint "eagle-import:EIA0603")
      (libsource (lib "eagle-import") (part "C_0603EIA0603"))
    )
    (comp (ref "C368")
      (value "100nF/50V")
      (footprint "eagle-import:EIA0603")
      (libsource (lib "eagle-import") (part "C_0603EIA0603"))
    )
    (comp (ref "C369")
      (value "2.2uF/35V")
      (footprint "eagle-import:EIA0603")
      (libsource (lib "eagle-import") (part "C_0603EIA0603"))
    )
    (comp (ref "C370")
      (value "100pF/50V")
      (footprint "eagle-import:EIA0603")
      (libsource (lib "eagle-import") (part "C_0603EIA0603"))
    )
    (comp (ref "C371")
      (value "100pF/50V")
      (footprint "eagle-import:EIA0603")
      (libsource (lib "eagle-import") (part "C_0603EIA0603"))
    )
    (comp (ref "C372")
      (value "100pF/50V")
      (footprint "eagle-import:EIA0603")
      (libsource (lib "eagle-import") (part "C_0603EIA0603"))
    )
    (comp (ref "C373")
      (value "100pF/50V")
      (footprint "eagle-import:EIA0603")
      (libsource (lib "eagle-import") (part "C_0603EIA0603"))
    )
    (comp (ref "C374")
      (value "100pF/50V")
      (footprint "eagle-import:EIA0603")
      (libsource (lib "eagle-import") (part "C_0603EIA0603"))
    )
    (comp (ref "C375")
      (value "100pF/50V")
      (footprint "eagle-import:EIA0603")
      (libsource (lib "eagle-import") (part "C_0603EIA0603"))
    )
    (comp (ref "C376")
      (value "100pF/50V")
      (footprint "eagle-import:EIA0603")
      (libsource (lib "eagle-import") (part "C_0603EIA0603"))
    )
    (comp (ref "C377")
      (value "100pF/50V")
      (footprint "eagle-import:EIA0603")
      (libsource (lib "eagle-import") (part "C_0603EIA0603"))
    )
    (comp (ref "C378")
      (value "100pF/50V")
      (footprint "eagle-import:EIA0603")
      (libsource (lib "eagle-import") (part "C_0603EIA0603"))
    )
    (comp (ref "C379")
      (value "100pF/50V")
      (footprint "eagle-import:EIA0603")
      (libsource (lib "eagle-import") (part "C_0603EIA0603"))
    )
    (comp (ref "C380")
      (value "100pF/50V")
      (footprint "eagle-import:EIA0603")
      (libsource (lib "eagle-import") (part "C_0603EIA0603"))
    )
    (comp (ref "C381")
      (value "100pF/50V")
      (footprint "eagle-import:EIA0603")
      (libsource (lib "eagle-import") (part "C_0603EIA0603"))
    )
    (comp (ref "C382")
      (value "10F/35V")
      (footprint "eagle-import:EIA0603")
      (libsource (lib "eagle-import") (part "C_0603EIA0603"))
    )
    (comp (ref "C383")
      (value "100pF/25V")
      (footprint "eagle-import:EIA0603")
      (libsource (lib "eagle-import") (part "C_0603EIA0603"))
    )
    (comp (ref "C384")
      (value "4.7uF/35V")
      (footprint "eagle-import:EIA0603")
      (libsource (lib "eagle-import") (part "C_0603EIA0603"))
    )
    (comp (ref "C385")
      (value "100nF/25V")
      (footprint "eagle-import:EIA0603")
      (libsource (lib "eagle-import") (part "C_0603EIA0603"))
    )
    (comp (ref "C386")
      (value "10uF/35V")
      (footprint "eagle-import:EIA0603")
      (libsource (lib "eagle-import") (part "C_0603EIA0603"))
    )
    (comp (ref "C387")
      (value "100nF/100V")
      (footprint "eagle-import:EIA0603")
      (libsource (lib "eagle-import") (part "C_0603EIA0603"))
    )
    (comp (ref "C388")
      (value "10uF/25V")
      (footprint "eagle-import:EIA0603")
      (libsource (lib "eagle-import") (part "C_0603EIA0603"))
    )
    (comp (ref "C389")
      (value "10uF/25V")
      (footprint "eagle-import:EIA0603")
      (libsource (lib "eagle-import") (part "C_0603EIA0603"))
    )
    (comp (ref "C390")
      (value "10uF/35V")
      (footprint "eagle-import:EIA0603")
      (libsource (lib "eagle-import") (part "C_0603EIA0603"))
    )
    (comp (ref "C391")
      (value "10uF/35V")
      (footprint "eagle-import:EIA0603")
      (libsource (lib "eagle-import") (part "C_0603EIA0603"))
    )
    (comp (ref "C392")
      (value "10uF/35V")
      (footprint "eagle-import:EIA0603")
      (libsource (lib "eagle-import") (part "C_0603EIA0603"))
    )
    (comp (ref "C393")
      (value "470uF/35V")
      (footprint "eagle-import:CAPACITOR-ELKO-RM5-10X16")
      (fields (field (name "MFR") "Rubicon"))
      (libsource (lib "eagle-import") (part "50PX470MEFC10X20"))
    )
    (comp (ref "C394")
      (value "10F/35V")
      (footprint "eagle-import:EIA0603")
      (libsource (lib "eagle-import") (part "C_0603EIA0603"))
    )
    (comp (ref "C395")
      (value "10uF/25V")
      (footprint "eagle-import:EIA0603")
      (libsource (lib "eagle-import") (part "C_0603EIA0603"))
    )
    (comp (ref "C396")
      (value "10uF/25V")
      (footprint "eagle-import:EIA0603")
      (libsource (lib "eagle-import") (part "C_0603EIA0603"))
    )
    (comp (ref "C397")
      (value "10uF/25V")
      (footprint "eagle-import:EIA0603")
      (libsource (lib "eagle-import") (part "C_0603EIA0603"))
    )
    (comp (ref "C398")
      (value "10uF/35V")
      (footprint "eagle-import:EIA0603")
      (libsource (lib "eagle-import") (part "C_0603EIA0603"))
    )
    (comp (ref "C399")
      (value "10uF/35V")
      (footprint "eagle-import:EIA0603")
      (libsource (lib "eagle-import") (part "C_0603EIA0603"))
    )
    (comp (ref "C408")
      (value "10uF/35V")
      (footprint "eagle-import:EIA0603")
      (libsource (lib "eagle-import") (part "C_0603EIA0603"))
    )
    (comp (ref "C409")
      (value "4.7uF/50V")
      (footprint "eagle-import:EIA0603")
      (libsource (lib "eagle-import") (part "C_0603EIA0603"))
    )
    (comp (ref "C410")
      (value "4.7uF/50V")
      (footprint "eagle-import:EIA0603")
      (libsource (lib "eagle-import") (part "C_0603EIA0603"))
    )
    (comp (ref "C411")
      (value "100nF/50V")
      (footprint "eagle-import:EIA0603")
      (libsource (lib "eagle-import") (part "C_0603EIA0603"))
    )
    (comp (ref "C412")
      (value "100nF/50V")
      (footprint "eagle-import:EIA0603")
      (libsource (lib "eagle-import") (part "C_0603EIA0603"))
    )
    (comp (ref "C413")
      (value "100nF/100V")
      (footprint "eagle-import:EIA0603")
      (libsource (lib "eagle-import") (part "C_0603EIA0603"))
    )
    (comp (ref "C414")
      (value "100nF/100V")
      (footprint "eagle-import:EIA0603")
      (libsource (lib "eagle-import") (part "C_0603EIA0603"))
    )
    (comp (ref "C415")
      (value "100nF/100V")
      (footprint "eagle-import:EIA0603")
      (libsource (lib "eagle-import") (part "C_0603EIA0603"))
    )
    (comp (ref "C416")
      (value "10uF/25V")
      (footprint "eagle-import:EIA0603")
      (libsource (lib "eagle-import") (part "C_0603EIA0603"))
    )
    (comp (ref "C417")
      (value "10uF/25V")
      (footprint "eagle-import:EIA0603")
      (libsource (lib "eagle-import") (part "C_0603EIA0603"))
    )
    (comp (ref "C418")
      (value "100nF/100V")
      (footprint "eagle-import:EIA0603")
      (libsource (lib "eagle-import") (part "C_0603EIA0603"))
    )
    (comp (ref "C419")
      (value "CK45-B3FD102KYVNA")
      (footprint "eagle-import:C_DISC_P7.5D12")
      (fields (field (name "MFR") "TDK"))
      (libsource (lib "eagle-import") (part "CK45-B3FD102KYVNA"))
    )
    (comp (ref "C420")
      (value "CK45-B3FD102KYVNA")
      (footprint "eagle-import:C_DISC_P7.5D12")
      (fields (field (name "MFR") "TDK"))
      (libsource (lib "eagle-import") (part "CK45-B3FD102KYVNA"))
    )
    (comp (ref "C421")
      (value "10nF/50V")
      (footprint "eagle-import:EIA0603")
      (libsource (lib "eagle-import") (part "C_0603EIA0603"))
    )
    (comp (ref "C422")
      (value "1uF/25V")
      (footprint "eagle-import:EIA0603")
      (libsource (lib "eagle-import") (part "C_0603EIA0603"))
    )
    (comp (ref "C423")
      (value "330pF/50V")
      (footprint "eagle-import:EIA0603")
      (libsource (lib "eagle-import") (part "C_0603EIA0603"))
    )
    (comp (ref "C424")
      (value "330pF/50V")
      (footprint "eagle-import:EIA0603")
      (libsource (lib "eagle-import") (part "C_0603EIA0603"))
    )
    (comp (ref "C425")
      (value "330pF/50V")
      (footprint "eagle-import:EIA0603")
      (libsource (lib "eagle-import") (part "C_0603EIA0603"))
    )
    (comp (ref "C426")
      (value "330pF/50V")
      (footprint "eagle-import:EIA0603")
      (libsource (lib "eagle-import") (part "C_0603EIA0603"))
    )
    (comp (ref "C427")
      (value "10uF/35V")
      (footprint "eagle-import:EIA0603")
      (libsource (lib "eagle-import") (part "C_0603EIA0603"))
    )
    (comp (ref "C428")
      (value "10uF/35V")
      (footprint "eagle-import:EIA0603")
      (libsource (lib "eagle-import") (part "C_0603EIA0603"))
    )
    (comp (ref "C429")
      (value "10uF/25V")
      (footprint "eagle-import:EIA0603")
      (libsource (lib "eagle-import") (part "C_0603EIA0603"))
    )
    (comp (ref "C430")
      (value "10uF/35V")
      (footprint "eagle-import:EIA0603")
      (libsource (lib "eagle-import") (part "C_0603EIA0603"))
    )
    (comp (ref "C431")
      (value "10uF/35V")
      (footprint "eagle-import:EIA0603")
      (libsource (lib "eagle-import") (part "C_0603EIA0603"))
    )
    (comp (ref "C432")
      (value "10uF/35V")
      (footprint "eagle-import:EIA0603")
      (libsource (lib "eagle-import") (part "C_0603EIA0603"))
    )
    (comp (ref "C433")
      (value "100pF/25V")
      (footprint "eagle-import:EIA0603")
      (libsource (lib "eagle-import") (part "C_0603EIA0603"))
    )
    (comp (ref "C434")
      (value "10uF/35V")
      (footprint "eagle-import:EIA0603")
      (libsource (lib "eagle-import") (part "C_0603EIA0603"))
    )
    (comp (ref "C435")
      (value "10uF/35V")
      (footprint "eagle-import:EIA0603")
      (libsource (lib "eagle-import") (part "C_0603EIA0603"))
    )
    (comp (ref "C436")
      (value "10uF/35V")
      (footprint "eagle-import:EIA0603")
      (libsource (lib "eagle-import") (part "C_0603EIA0603"))
    )
    (comp (ref "C437")
      (value "ECW-F4245JLB")
      (footprint "eagle-import:CAPACITOR-FILM-RM17.5-28X17.5X25")
      (fields (field (name "MFR") "Panasonic") (field (name "PART_VALUE") "2.4uF/400V"))
      (libsource (lib "eagle-import") (part "ECW-F4245JLB"))
    )
    (comp (ref "C438")
      (value "ECW-F4245JLB")
      (footprint "eagle-import:CAPACITOR-FILM-RM17.5-28X17.5X25")
      (fields (field (name "MFR") "Panasonic") (field (name "PART_VALUE") "2.4uF/400V"))
      (libsource (lib "eagle-import") (part "ECW-F4245JLB"))
    )
    (comp (ref "D300")
      (value "STTH1R04USMB")
      (footprint "eagle-import:SMB")
      (libsource (lib "eagle-import") (part "STTH1R04USMB"))
    )
    (comp (ref "D301")
      (value "STTH1R04USMB")
      (footprint "eagle-import:SMB")
      (libsource (lib "eagle-import") (part "STTH1R04USMB"))
    )
    (comp (ref "D302")
      (value "SS14")
      (footprint "eagle-import:SMA")
      (fields (field (name "MFR") "MCC"))
      (libsource (lib "eagle-import") (part "SS14"))
    )
    (comp (ref "D303")
      (value "STTH1R04USMB")
      (footprint "eagle-import:SMB")
      (libsource (lib "eagle-import") (part "STTH1R04USMB"))
    )
    (comp (ref "D304")
      (value "STTH1R04USMB")
      (footprint "eagle-import:SMB")
      (libsource (lib "eagle-import") (part "STTH1R04USMB"))
    )
    (comp (ref "D305")
      (value "STTH1R04USMB")
      (footprint "eagle-import:SMB")
      (libsource (lib "eagle-import") (part "STTH1R04USMB"))
    )
    (comp (ref "D306")
      (value "SS14")
      (footprint "eagle-import:SMA")
      (fields (field (name "MFR") "MCC"))
      (libsource (lib "eagle-import") (part "SS14"))
    )
    (comp (ref "D307")
      (value "FEP30DP-E3/45TO-247AD")
      (footprint "eagle-import:TO-247AD")
      (libsource (lib "eagle-import") (part "FEP30DP-E3/45TO-247AD"))
    )
    (comp (ref "D308")
      (value "FEP30DP-E3/45TO-247AD")
      (footprint "eagle-import:TO-247AD")
      (libsource (lib "eagle-import") (part "FEP30DP-E3/45TO-247AD"))
    )
    (comp (ref "D309")
      (value "FEP30DP-E3/45TO-247AD")
      (footprint "eagle-import:TO-247AD")
      (libsource (lib "eagle-import") (part "FEP30DP-E3/45TO-247AD"))
    )
    (comp (ref "D310")
      (value "FEP30DP-E3/45TO-247AD")
      (footprint "eagle-import:TO-247AD")
      (libsource (lib "eagle-import") (part "FEP30DP-E3/45TO-247AD"))
    )
    (comp (ref "D311")
      (value "FEP30DP-E3/45TO-247AD")
      (footprint "eagle-import:TO-247AD")
      (libsource (lib "eagle-import") (part "FEP30DP-E3/45TO-247AD"))
    )
    (comp (ref "D312")
      (value "FEP30DP-E3/45TO-247AD")
      (footprint "eagle-import:TO-247AD")
      (libsource (lib "eagle-import") (part "FEP30DP-E3/45TO-247AD"))
    )
    (comp (ref "D313")
      (value "GB02SLT12-214")
      (footprint "eagle-import:SMB")
      (fields (field (name "MFR") "GeneSic"))
      (libsource (lib "eagle-import") (part "GB02SLT12-214"))
    )
    (comp (ref "D314")
      (value "GB02SLT12-214")
      (footprint "eagle-import:SMB")
      (fields (field (name "MFR") "GeneSic"))
      (libsource (lib "eagle-import") (part "GB02SLT12-214"))
    )
    (comp (ref "D315")
      (value "SD103AW")
      (footprint "eagle-import:SOD-323")
      (fields (field (name "MFR") "Onsemi, Guanddong Hottech"))
      (libsource (lib "eagle-import") (part "SD103AW"))
    )
    (comp (ref "D316")
      (value "SS14")
      (footprint "eagle-import:SMA")
      (fields (field (name "MFR") "MCC"))
      (libsource (lib "eagle-import") (part "SS14"))
    )
    (comp (ref "D317")
      (value "SD103AW")
      (footprint "eagle-import:SOD-323")
      (fields (field (name "MFR") "Onsemi, Guanddong Hottech"))
      (libsource (lib "eagle-import") (part "SD103AW"))
    )
    (comp (ref "D318")
      (value "SS14")
      (footprint "eagle-import:SMA")
      (fields (field (name "MFR") "MCC"))
      (libsource (lib "eagle-import") (part "SS14"))
    )
    (comp (ref "D319")
      (value "SD103AW")
      (footprint "eagle-import:SOD-323")
      (fields (field (name "MFR") "Onsemi, Guanddong Hottech"))
      (libsource (lib "eagle-import") (part "SD103AW"))
    )
    (comp (ref "D320")
      (value "SD103AW")
      (footprint "eagle-import:SOD-323")
      (fields (field (name "MFR") "Onsemi, Guanddong Hottech"))
      (libsource (lib "eagle-import") (part "SD103AW"))
    )
    (comp (ref "D321")
      (value "SD103AW")
      (footprint "eagle-import:SOD-323")
      (fields (field (name "MFR") "Onsemi, Guanddong Hottech"))
      (libsource (lib "eagle-import") (part "SD103AW"))
    )
    (comp (ref "D322")
      (value "SD103AW")
      (footprint "eagle-import:SOD-323")
      (fields (field (name "MFR") "Onsemi, Guanddong Hottech"))
      (libsource (lib "eagle-import") (part "SD103AW"))
    )
    (comp (ref "D323")
      (value "STTH1R04USMB")
      (footprint "eagle-import:SMB")
      (libsource (lib "eagle-import") (part "STTH1R04USMB"))
    )
    (comp (ref "D324")
      (value "BAT54S")
      (footprint "eagle-import:SOT23DUALDIODE")
      (fields (field (name "MFR") "HT"))
      (libsource (lib "eagle-import") (part "BAT54S"))
    )
    (comp (ref "IC1")
      (value "UCC28951PWR")
      (footprint "eagle-import:TSSOP24")
      (fields (field (name "MFR") "Texas Instruments"))
      (libsource (lib "eagle-import") (part "UCC28951PWR"))
    )
    (comp (ref "IC300")
      (value "LMV641")
      (footprint "eagle-import:SOT-23-5")
      (fields (field (name "MFR") "Texas Instruments"))
      (libsource (lib "eagle-import") (part "LMV641"))
    )
    (comp (ref "IC301")
      (value "LMV641")
      (footprint "eagle-import:SOT-23-5")
      (fields (field (name "MFR") "Texas Instruments"))
      (libsource (lib "eagle-import") (part "LMV641"))
    )
    (comp (ref "IC302")
      (value "LMV641")
      (footprint "eagle-import:SOT-23-5")
      (fields (field (name "MFR") "Texas Instruments"))
      (libsource (lib "eagle-import") (part "LMV641"))
    )
    (comp (ref "IC306")
      (value "UCC21710")
      (footprint "eagle-import:SOIC16_WIDE_HV")
      (libsource (lib "eagle-import") (part "UCC21710"))
    )
    (comp (ref "IC307")
      (value "UCC21710")
      (footprint "eagle-import:SOIC16_WIDE_HV")
      (libsource (lib "eagle-import") (part "UCC21710"))
    )
    (comp (ref "IC308")
      (value "MAX764CSA+")
      (footprint "eagle-import:SOIC8")
      (fields (field (name "MFR") "Max IC"))
      (libsource (lib "eagle-import") (part "MAX764CSA+"))
    )
    (comp (ref "IC309")
      (value "MAX764CSA+")
      (footprint "eagle-import:SOIC8")
      (fields (field (name "MFR") "Max IC"))
      (libsource (lib "eagle-import") (part "MAX764CSA+"))
    )
    (comp (ref "IC310")
      (value "UCC21710")
      (footprint "eagle-import:SOIC16_WIDE_HV")
      (libsource (lib "eagle-import") (part "UCC21710"))
    )
    (comp (ref "IC311")
      (value "UCC21710")
      (footprint "eagle-import:SOIC16_WIDE_HV")
      (libsource (lib "eagle-import") (part "UCC21710"))
    )
    (comp (ref "IC312")
      (value "LM317AEMP")
      (footprint "eagle-import:SOT223_LM317AEMP")
      (libsource (lib "eagle-import") (part "LM317AEMP"))
    )
    (comp (ref "IC313")
      (value "LM317AEMP")
      (footprint "eagle-import:SOT223_LM317AEMP")
      (libsource (lib "eagle-import") (part "LM317AEMP"))
    )
    (comp (ref "L300")
      (value "BLM18RK601SN1D")
      (footprint "eagle-import:0603")
      (fields (field (name "MFR") "Murata"))
      (libsource (lib "eagle-import") (part "BLM18RK601SN1D"))
    )
    (comp (ref "L302")
      (value "BLM18RK601SN1D")
      (footprint "eagle-import:0603")
      (fields (field (name "MFR") "Murata"))
      (libsource (lib "eagle-import") (part "BLM18RK601SN1D"))
    )
    (comp (ref "L303")
      (value "SRN8040TA-220M")
      (footprint "eagle-import:SRN8040TA-220M")
      (fields (field (name "MFR") "Bourns"))
      (libsource (lib "eagle-import") (part "SRN8040TA-220M"))
    )
    (comp (ref "L304")
      (value "BLM18RK601SN1D")
      (footprint "eagle-import:0603")
      (fields (field (name "MFR") "Murata"))
      (libsource (lib "eagle-import") (part "BLM18RK601SN1D"))
    )
    (comp (ref "L307")
      (value "SRN8040TA-220M")
      (footprint "eagle-import:SRN8040TA-220M")
      (fields (field (name "MFR") "Bourns"))
      (libsource (lib "eagle-import") (part "SRN8040TA-220M"))
    )
    (comp (ref "L308")
      (value "BLM18RK601SN1D")
      (footprint "eagle-import:0603")
      (fields (field (name "MFR") "Murata"))
      (libsource (lib "eagle-import") (part "BLM18RK601SN1D"))
    )
    (comp (ref "L309")
      (value "BLM18RK601SN1D")
      (footprint "eagle-import:0603")
      (fields (field (name "MFR") "Murata"))
      (libsource (lib "eagle-import") (part "BLM18RK601SN1D"))
    )
    (comp (ref "Q300")
      (value "2N7002")
      (footprint "eagle-import:SOT23")
      (fields (field (name "MFR") "Diodes, Guangdong Hotetech,NXP"))
      (libsource (lib "eagle-import") (part "2N7002"))
    )
    (comp (ref "Q306")
      (value "2N7002")
      (footprint "eagle-import:SOT23")
      (fields (field (name "MFR") "Diodes, Guangdong Hotetech,NXP"))
      (libsource (lib "eagle-import") (part "2N7002"))
    )
    (comp (ref "R300")
      (value "100K 1%")
      (footprint "eagle-import:EIA0603")
      (libsource (lib "eagle-import") (part "R_0603"))
    )
    (comp (ref "R301")
      (value "47R 1%")
      (footprint "eagle-import:R2512")
      (libsource (lib "eagle-import") (part "R-US_R2512"))
    )
    (comp (ref "R302")
      (value "47R 1%")
      (footprint "eagle-import:R2512")
      (libsource (lib "eagle-import") (part "R-US_R2512"))
    )
    (comp (ref "R303")
      (value "4.7K 1%")
      (footprint "eagle-import:EIA0603")
      (libsource (lib "eagle-import") (part "R_0603"))
    )
    (comp (ref "R304")
      (value "33R 1%")
      (footprint "eagle-import:EIA2010")
      (libsource (lib "eagle-import") (part "R_2010EIA2010"))
    )
    (comp (ref "R305")
      (value "10K 1%")
      (footprint "eagle-import:EIA0603")
      (libsource (lib "eagle-import") (part "R_0603"))
    )
    (comp (ref "R306")
      (value "10K 1%")
      (footprint "eagle-import:EIA0603")
      (libsource (lib "eagle-import") (part "R_0603"))
    )
    (comp (ref "R307")
      (value "10K 1%")
      (footprint "eagle-import:EIA0603")
      (libsource (lib "eagle-import") (part "R_0603"))
    )
    (comp (ref "R308")
      (value "4.7k 1%")
      (footprint "eagle-import:EIA0603")
      (libsource (lib "eagle-import") (part "R_0603"))
    )
    (comp (ref "R309")
      (value "1K 1%")
      (footprint "eagle-import:EIA2010")
      (libsource (lib "eagle-import") (part "R_2010EIA2010"))
    )
    (comp (ref "R310")
      (value "47R 1%")
      (footprint "eagle-import:R2512")
      (libsource (lib "eagle-import") (part "R-US_R2512"))
    )
    (comp (ref "R311")
      (value "47R 1%")
      (footprint "eagle-import:R2512")
      (libsource (lib "eagle-import") (part "R-US_R2512"))
    )
    (comp (ref "R312")
      (value "1K 1%")
      (footprint "eagle-import:EIA2010")
      (libsource (lib "eagle-import") (part "R_2010EIA2010"))
    )
    (comp (ref "R313")
      (value "33R 1%")
      (footprint "eagle-import:EIA2010")
      (libsource (lib "eagle-import") (part "R_2010EIA2010"))
    )
    (comp (ref "R314")
      (value "10k 1%")
      (footprint "eagle-import:EIA0603")
      (libsource (lib "eagle-import") (part "R_0603"))
    )
    (comp (ref "R315")
      (value "1K 1%")
      (footprint "eagle-import:EIA0603")
      (libsource (lib "eagle-import") (part "R_0603"))
    )
    (comp (ref "R316")
      (value "12R 1%")
      (footprint "eagle-import:EIA2512")
      (libsource (lib "eagle-import") (part "R_2512"))
    )
    (comp (ref "R317")
      (value "10K 1%")
      (footprint "eagle-import:EIA0603")
      (libsource (lib "eagle-import") (part "R_0603"))
    )
    (comp (ref "R318")
      (value "10K 1%")
      (footprint "eagle-import:EIA0603")
      (libsource (lib "eagle-import") (part "R_0603"))
    )
    (comp (ref "R319")
      (value "10K 1%")
      (footprint "eagle-import:EIA0603")
      (libsource (lib "eagle-import") (part "R_0603"))
    )
    (comp (ref "R320")
      (value "10K 1%")
      (footprint "eagle-import:EIA0603")
      (libsource (lib "eagle-import") (part "R_0603"))
    )
    (comp (ref "R321")
      (value "10K 1%")
      (footprint "eagle-import:EIA0603")
      (libsource (lib "eagle-import") (part "R_0603"))
    )
    (comp (ref "R322")
      (value "47R 1%")
      (footprint "eagle-import:R2512")
      (libsource (lib "eagle-import") (part "R-US_R2512"))
    )
    (comp (ref "R323")
      (value "47R 1%")
      (footprint "eagle-import:R2512")
      (libsource (lib "eagle-import") (part "R-US_R2512"))
    )
    (comp (ref "R324")
      (value "10K 1%")
      (footprint "eagle-import:EIA0603")
      (libsource (lib "eagle-import") (part "R_0603"))
    )
    (comp (ref "R325")
      (value "33R 1%")
      (footprint "eagle-import:EIA2010")
      (libsource (lib "eagle-import") (part "R_2010EIA2010"))
    )
    (comp (ref "R326")
      (value "RNF12FTD10M0")
      (footprint "eagle-import:RES-RM12.5-VR37")
      (fields (field (name "MFR") "Stackpole Electronics Inc"))
      (libsource (lib "eagle-import") (part "RNF12FTD10M0"))
    )
    (comp (ref "R327")
      (value "22R 1%")
      (footprint "eagle-import:EIA2010")
      (libsource (lib "eagle-import") (part "R_2010EIA2010"))
    )
    (comp (ref "R328")
      (value "1K 1%")
      (footprint "eagle-import:EIA2010")
      (libsource (lib "eagle-import") (part "R_2010EIA2010"))
    )
    (comp (ref "R329")
      (value "47R 1%")
      (footprint "eagle-import:R2512")
      (libsource (lib "eagle-import") (part "R-US_R2512"))
    )
    (comp (ref "R330")
      (value "47R 1%")
      (footprint "eagle-import:R2512")
      (libsource (lib "eagle-import") (part "R-US_R2512"))
    )
    (comp (ref "R331")
      (value "1K 1%")
      (footprint "eagle-import:EIA2010")
      (libsource (lib "eagle-import") (part "R_2010EIA2010"))
    )
    (comp (ref "R332")
      (value "33R 1%")
      (footprint "eagle-import:EIA2010")
      (libsource (lib "eagle-import") (part "R_2010EIA2010"))
    )
    (comp (ref "R333")
      (value "150K 1%")
      (footprint "eagle-import:EIA0603")
      (libsource (lib "eagle-import") (part "R_0603"))
    )
    (comp (ref "R334")
      (value "100K 1%")
      (footprint "eagle-import:EIA0603")
      (libsource (lib "eagle-import") (part "R_0603"))
    )
    (comp (ref "R335")
      (value "1.5K 1%")
      (footprint "eagle-import:EIA0603")
      (libsource (lib "eagle-import") (part "R_0603"))
    )
    (comp (ref "R336")
      (value "10K 1%")
      (footprint "eagle-import:EIA0603")
      (libsource (lib "eagle-import") (part "R_0603"))
    )
    (comp (ref "R337")
      (value "510R 1%")
      (footprint "eagle-import:EIA0603")
      (libsource (lib "eagle-import") (part "R_0603"))
    )
    (comp (ref "R338")
      (value "33K 1%")
      (footprint "eagle-import:EIA0603")
      (libsource (lib "eagle-import") (part "R_0603"))
    )
    (comp (ref "R339")
      (value "162R 1%")
      (footprint "eagle-import:EIA0603")
      (libsource (lib "eagle-import") (part "R_0603"))
    )
    (comp (ref "R340")
      (value "WSL5931L3000FEA")
      (footprint "eagle-import:WSLP3921")
      (fields (field (name "MFR") "Vishay"))
      (libsource (lib "eagle-import") (part "WSL5931L3000FEA"))
    )
    (comp (ref "R341")
      (value "510R 1%")
      (footprint "eagle-import:EIA0603")
      (libsource (lib "eagle-import") (part "R_0603"))
    )
    (comp (ref "R342")
      (value "220k 1%")
      (footprint "eagle-import:EIA0603")
      (libsource (lib "eagle-import") (part "R_0603"))
    )
    (comp (ref "R343")
      (value "10k 1%")
      (footprint "eagle-import:EIA0603")
      (libsource (lib "eagle-import") (part "R_0603"))
    )
    (comp (ref "R344")
      (value "1.5K 1%")
      (footprint "eagle-import:EIA0603")
      (libsource (lib "eagle-import") (part "R_0603"))
    )
    (comp (ref "R345")
      (value "100K 1%")
      (footprint "eagle-import:EIA0603")
      (libsource (lib "eagle-import") (part "R_0603"))
    )
    (comp (ref "R346")
      (value "3.3K 1%")
      (footprint "eagle-import:EIA0603")
      (libsource (lib "eagle-import") (part "R_0603"))
    )
    (comp (ref "R347")
      (value "3.3K 1%")
      (footprint "eagle-import:EIA0603")
      (libsource (lib "eagle-import") (part "R_0603"))
    )
    (comp (ref "R348")
      (value "3.3K 1%")
      (footprint "eagle-import:EIA0603")
      (libsource (lib "eagle-import") (part "R_0603"))
    )
    (comp (ref "R349")
      (value "1K 1%")
      (footprint "eagle-import:EIA0603")
      (libsource (lib "eagle-import") (part "R_0603"))
    )
    (comp (ref "R350")
      (value "10K 1%")
      (footprint "eagle-import:EIA0603")
      (libsource (lib "eagle-import") (part "R_0603"))
    )
    (comp (ref "R351")
      (value "10K 1%")
      (footprint "eagle-import:EIA0603")
      (libsource (lib "eagle-import") (part "R_0603"))
    )
    (comp (ref "R352")
      (value "10R 1%")
      (footprint "eagle-import:EIA0603")
      (libsource (lib "eagle-import") (part "R_0603"))
    )
    (comp (ref "R353")
      (value "0R 1%")
      (footprint "eagle-import:EIA0603")
      (libsource (lib "eagle-import") (part "R_0603"))
    )
    (comp (ref "R354")
      (value "10R 1%")
      (footprint "eagle-import:EIA0603")
      (libsource (lib "eagle-import") (part "R_0603"))
    )
    (comp (ref "R355")
      (value "412R 1%")
      (footprint "eagle-import:EIA0603")
      (libsource (lib "eagle-import") (part "R_0603"))
    )
    (comp (ref "R356")
      (value "1.2K 1%")
      (footprint "eagle-import:EIA0603")
      (libsource (lib "eagle-import") (part "R_0603"))
    )
    (comp (ref "R357")
      (value "49.9K 1%")
      (footprint "eagle-import:EIA0603")
      (libsource (lib "eagle-import") (part "R_0603"))
    )
    (comp (ref "R358")
      (value "10R 1%")
      (footprint "eagle-import:EIA0603")
      (libsource (lib "eagle-import") (part "R_0603"))
    )
    (comp (ref "R359")
      (value "49.9K 1%")
      (footprint "eagle-import:EIA0603")
      (libsource (lib "eagle-import") (part "R_0603"))
    )
    (comp (ref "R360")
      (value "65K 1%")
      (footprint "eagle-import:EIA0603")
      (libsource (lib "eagle-import") (part "R_0603"))
    )
    (comp (ref "R361")
      (value "0R 1%")
      (footprint "eagle-import:EIA0603")
      (libsource (lib "eagle-import") (part "R_0603"))
    )
    (comp (ref "R362")
      (value "65K 1%")
      (footprint "eagle-import:EIA0603")
      (libsource (lib "eagle-import") (part "R_0603"))
    )
    (comp (ref "R363")
      (value "10K 1%")
      (footprint "eagle-import:EIA0603")
      (libsource (lib "eagle-import") (part "R_0603"))
    )
    (comp (ref "R364")
      (value "412R 1%")
      (footprint "eagle-import:EIA0603")
      (libsource (lib "eagle-import") (part "R_0603"))
    )
    (comp (ref "R365")
      (value "100K 1%")
      (footprint "eagle-import:EIA0603")
      (libsource (lib "eagle-import") (part "R_0603"))
    )
    (comp (ref "R366")
      (value "10K 1%")
      (footprint "eagle-import:EIA0603")
      (libsource (lib "eagle-import") (part "R_0603"))
    )
    (comp (ref "R367")
      (value "1.2K 1%")
      (footprint "eagle-import:EIA0603")
      (libsource (lib "eagle-import") (part "R_0603"))
    )
    (comp (ref "R368")
      (value "100K 1%")
      (footprint "eagle-import:EIA0603")
      (libsource (lib "eagle-import") (part "R_0603"))
    )
    (comp (ref "R369")
      (value "150K 1%")
      (footprint "eagle-import:EIA0603")
      (libsource (lib "eagle-import") (part "R_0603"))
    )
    (comp (ref "R370")
      (value "10R 1%")
      (footprint "eagle-import:EIA0603")
      (libsource (lib "eagle-import") (part "R_0603"))
    )
    (comp (ref "R371")
      (value "18K 1%")
      (footprint "eagle-import:EIA0603")
      (libsource (lib "eagle-import") (part "R_0603"))
    )
    (comp (ref "R372")
      (value "10R 1%")
      (footprint "eagle-import:EIA2512")
      (libsource (lib "eagle-import") (part "R_2512"))
    )
    (comp (ref "R373")
      (value "0R 1%")
      (footprint "eagle-import:EIA0603")
      (libsource (lib "eagle-import") (part "R_0603"))
    )
    (comp (ref "R374")
      (value "18K 1%")
      (footprint "eagle-import:EIA0603")
      (libsource (lib "eagle-import") (part "R_0603"))
    )
    (comp (ref "R375")
      (value "620R 1%")
      (footprint "eagle-import:EIA0603")
      (libsource (lib "eagle-import") (part "R_0603"))
    )
    (comp (ref "R376")
      (value "620R 1%")
      (footprint "eagle-import:EIA0603")
      (libsource (lib "eagle-import") (part "R_0603"))
    )
    (comp (ref "R377")
      (value "412R 1%")
      (footprint "eagle-import:EIA0603")
      (libsource (lib "eagle-import") (part "R_0603"))
    )
    (comp (ref "R378")
      (value "1.2K 1%")
      (footprint "eagle-import:EIA0603")
      (libsource (lib "eagle-import") (part "R_0603"))
    )
    (comp (ref "R379")
      (value "0R 1%")
      (footprint "eagle-import:EIA0603")
      (libsource (lib "eagle-import") (part "R_0603"))
    )
    (comp (ref "R380")
      (value "10R 1%")
      (footprint "eagle-import:EIA0603")
      (libsource (lib "eagle-import") (part "R_0603"))
    )
    (comp (ref "R381")
      (value "0R 1%")
      (footprint "eagle-import:EIA0603")
      (libsource (lib "eagle-import") (part "R_0603"))
    )
    (comp (ref "R382")
      (value "412R 1%")
      (footprint "eagle-import:EIA0603")
      (libsource (lib "eagle-import") (part "R_0603"))
    )
    (comp (ref "R383")
      (value "1.2K 1%")
      (footprint "eagle-import:EIA0603")
      (libsource (lib "eagle-import") (part "R_0603"))
    )
    (comp (ref "R384")
      (value "10R 1%")
      (footprint "eagle-import:EIA0603")
      (libsource (lib "eagle-import") (part "R_0603"))
    )
    (comp (ref "R385")
      (value "22R 1%")
      (footprint "eagle-import:EIA2010")
      (libsource (lib "eagle-import") (part "R_2010EIA2010"))
    )
    (comp (ref "R386")
      (value "10K 1%")
      (footprint "eagle-import:EIA0603")
      (libsource (lib "eagle-import") (part "R_0603"))
    )
    (comp (ref "R387")
      (value "33R 1%")
      (footprint "eagle-import:EIA2010")
      (libsource (lib "eagle-import") (part "R_2010EIA2010"))
    )
    (comp (ref "R388")
      (value "10K 1%")
      (footprint "eagle-import:EIA0603")
      (libsource (lib "eagle-import") (part "R_0603"))
    )
    (comp (ref "R389")
      (value "825K 1%")
      (footprint "eagle-import:EIA0603")
      (libsource (lib "eagle-import") (part "R_0603"))
    )
    (comp (ref "R390")
      (value "4.7k 1%")
      (footprint "eagle-import:EIA0603")
      (libsource (lib "eagle-import") (part "R_0603"))
    )
    (comp (ref "R391")
      (value "3.3K 1%")
      (footprint "eagle-import:EIA0603")
      (libsource (lib "eagle-import") (part "R_0603"))
    )
    (comp (ref "R396")
      (value "33R 1%")
      (footprint "eagle-import:EIA2010")
      (libsource (lib "eagle-import") (part "R_2010EIA2010"))
    )
    (comp (ref "R397")
      (value "5.6K 1%")
      (footprint "eagle-import:EIA0603")
      (libsource (lib "eagle-import") (part "R_0603"))
    )
    (comp (ref "R398")
      (value "RNF12FTD10M0")
      (footprint "eagle-import:RES-RM12.5-VR37")
      (fields (field (name "MFR") "Stackpole Electronics Inc"))
      (libsource (lib "eagle-import") (part "RNF12FTD10M0"))
    )
    (comp (ref "R399")
      (value "33K 1%")
      (footprint "eagle-import:EIA0603")
      (libsource (lib "eagle-import") (part "R_0603"))
    )
    (comp (ref "R400")
      (value "10k 1%")
      (footprint "eagle-import:EIA0603")
      (libsource (lib "eagle-import") (part "R_0603"))
    )
    (comp (ref "R401")
      (value "10R 1%")
      (footprint "eagle-import:EIA2512")
      (libsource (lib "eagle-import") (part "R_2512"))
    )
    (comp (ref "R402")
      (value "33K 1%")
      (footprint "eagle-import:EIA0603")
      (libsource (lib "eagle-import") (part "R_0603"))
    )
    (comp (ref "R403")
      (value "10k 1%")
      (footprint "eagle-import:EIA0603")
      (libsource (lib "eagle-import") (part "R_0603"))
    )
    (comp (ref "R404")
      (value "220R 1%")
      (footprint "eagle-import:EIA0603")
      (libsource (lib "eagle-import") (part "R_0603"))
    )
    (comp (ref "R405")
      (value "2.2K 1%")
      (footprint "eagle-import:EIA0603")
      (libsource (lib "eagle-import") (part "R_0603"))
    )
    (comp (ref "R406")
      (value "5.6K 1%")
      (footprint "eagle-import:EIA0603")
      (libsource (lib "eagle-import") (part "R_0603"))
    )
    (comp (ref "R407")
      (value "4.7K 1%")
      (footprint "eagle-import:EIA0603")
      (libsource (lib "eagle-import") (part "R_0603"))
    )
    (comp (ref "R408")
      (value "4.7k 1%")
      (footprint "eagle-import:EIA0603")
      (libsource (lib "eagle-import") (part "R_0603"))
    )
    (comp (ref "R409")
      (value "4.7k 1%")
      (footprint "eagle-import:EIA0603")
      (libsource (lib "eagle-import") (part "R_0603"))
    )
    (comp (ref "R410")
      (value "220R 1%")
      (footprint "eagle-import:EIA0603")
      (libsource (lib "eagle-import") (part "R_0603"))
    )
    (comp (ref "R411")
      (value "2.2K 1%")
      (footprint "eagle-import:EIA0603")
      (libsource (lib "eagle-import") (part "R_0603"))
    )
    (comp (ref "R412")
      (value "5.6K 1%")
      (footprint "eagle-import:EIA0603")
      (libsource (lib "eagle-import") (part "R_0603"))
    )
    (comp (ref "R413")
      (value "4.7K 1%")
      (footprint "eagle-import:EIA0603")
      (libsource (lib "eagle-import") (part "R_0603"))
    )
    (comp (ref "R414")
      (value "4.7k 1%")
      (footprint "eagle-import:EIA0603")
      (libsource (lib "eagle-import") (part "R_0603"))
    )
    (comp (ref "R415")
      (value "4.7k 1%")
      (footprint "eagle-import:EIA0603")
      (libsource (lib "eagle-import") (part "R_0603"))
    )
    (comp (ref "R416")
      (value "220R 1%")
      (footprint "eagle-import:EIA0603")
      (libsource (lib "eagle-import") (part "R_0603"))
    )
    (comp (ref "R417")
      (value "2.2K 1%")
      (footprint "eagle-import:EIA0603")
      (libsource (lib "eagle-import") (part "R_0603"))
    )
    (comp (ref "R418")
      (value "5.6K 1%")
      (footprint "eagle-import:EIA0603")
      (libsource (lib "eagle-import") (part "R_0603"))
    )
    (comp (ref "R419")
      (value "4.7K 1%")
      (footprint "eagle-import:EIA0603")
      (libsource (lib "eagle-import") (part "R_0603"))
    )
    (comp (ref "R420")
      (value "4.7k 1%")
      (footprint "eagle-import:EIA0603")
      (libsource (lib "eagle-import") (part "R_0603"))
    )
    (comp (ref "R421")
      (value "4.7k 1%")
      (footprint "eagle-import:EIA0603")
      (libsource (lib "eagle-import") (part "R_0603"))
    )
    (comp (ref "R422")
      (value "220R 1%")
      (footprint "eagle-import:EIA0603")
      (libsource (lib "eagle-import") (part "R_0603"))
    )
    (comp (ref "R423")
      (value "2.2K 1%")
      (footprint "eagle-import:EIA0603")
      (libsource (lib "eagle-import") (part "R_0603"))
    )
    (comp (ref "R424")
      (value "10R 1%")
      (footprint "eagle-import:EIA2512")
      (libsource (lib "eagle-import") (part "R_2512"))
    )
    (comp (ref "R425")
      (value "5.6K 1%")
      (footprint "eagle-import:EIA0603")
      (libsource (lib "eagle-import") (part "R_0603"))
    )
    (comp (ref "R426")
      (value "5.6k 1%")
      (footprint "eagle-import:EIA0603")
      (libsource (lib "eagle-import") (part "R_0603"))
    )
    (comp (ref "R427")
      (value "10R 1%")
      (footprint "eagle-import:EIA2512")
      (libsource (lib "eagle-import") (part "R_2512"))
    )
    (comp (ref "R428")
      (value "5.6K 1%")
      (footprint "eagle-import:EIA0603")
      (libsource (lib "eagle-import") (part "R_0603"))
    )
    (comp (ref "R429")
      (value "5.6k 1%")
      (footprint "eagle-import:EIA0603")
      (libsource (lib "eagle-import") (part "R_0603"))
    )
    (comp (ref "R430")
      (value "412R 1%")
      (footprint "eagle-import:EIA0603")
      (libsource (lib "eagle-import") (part "R_0603"))
    )
    (comp (ref "R431")
      (value "412R 1%")
      (footprint "eagle-import:EIA0603")
      (libsource (lib "eagle-import") (part "R_0603"))
    )
    (comp (ref "R432")
      (value "3.9K 1%")
      (footprint "eagle-import:EIA0603")
      (libsource (lib "eagle-import") (part "R_0603"))
    )
    (comp (ref "R433")
      (value "3.9K 1%")
      (footprint "eagle-import:EIA0603")
      (libsource (lib "eagle-import") (part "R_0603"))
    )
    (comp (ref "R434")
      (value "15.8K 1%")
      (footprint "eagle-import:EIA0603")
      (libsource (lib "eagle-import") (part "R_0603"))
    )
    (comp (ref "R435")
      (value "15.8K 1%")
      (footprint "eagle-import:EIA0603")
      (libsource (lib "eagle-import") (part "R_0603"))
    )
    (comp (ref "R436")
      (value "41K 1%")
      (footprint "eagle-import:EIA2010")
      (libsource (lib "eagle-import") (part "R_2010EIA2010"))
    )
    (comp (ref "R437")
      (value "100K 1%")
      (footprint "eagle-import:EIA0603")
      (libsource (lib "eagle-import") (part "R_0603"))
    )
    (comp (ref "R438")
      (value "1.2K 1%")
      (footprint "eagle-import:EIA2010")
      (libsource (lib "eagle-import") (part "R_2010EIA2010"))
    )
    (comp (ref "R439")
      (value "RR02J22RTB")
      (footprint "eagle-import:RES-RM15-RSF1W")
      (fields (field (name "MFR") "TE Connectivity"))
      (libsource (lib "eagle-import") (part "RR02J22RTB"))
    )
    (comp (ref "R440")
      (value "RR02J22RTB")
      (footprint "eagle-import:RES-RM15-RSF1W")
      (fields (field (name "MFR") "TE Connectivity"))
      (libsource (lib "eagle-import") (part "RR02J22RTB"))
    )
    (comp (ref "R441")
      (value "RR02J22RTB")
      (footprint "eagle-import:RES-RM15-RSF1W")
      (fields (field (name "MFR") "TE Connectivity"))
      (libsource (lib "eagle-import") (part "RR02J22RTB"))
    )
    (comp (ref "R442")
      (value "RR02J22RTB")
      (footprint "eagle-import:RES-RM15-RSF1W")
      (fields (field (name "MFR") "TE Connectivity"))
      (libsource (lib "eagle-import") (part "RR02J22RTB"))
    )
    (comp (ref "R461")
      (value "10R 1%")
      (footprint "eagle-import:EIA0603")
      (libsource (lib "eagle-import") (part "R_0603"))
    )
    (comp (ref "R462")
      (value "10R 1%")
      (footprint "eagle-import:EIA0603")
      (libsource (lib "eagle-import") (part "R_0603"))
    )
    (comp (ref "R463")
      (value "10K 1%")
      (footprint "eagle-import:EIA0603")
      (libsource (lib "eagle-import") (part "R_0603"))
    )
    (comp (ref "T300")
      (value "IHW20N120R5")
      (footprint "eagle-import:TO-247AC")
      (fields (field (name "MFR") "Infineon"))
      (libsource (lib "eagle-import") (part "IHW20N120R5"))
    )
    (comp (ref "T301")
      (value "IHW20N120R5")
      (footprint "eagle-import:TO-247AC")
      (fields (field (name "MFR") "Infineon"))
      (libsource (lib "eagle-import") (part "IHW20N120R5"))
    )
    (comp (ref "T302")
      (value "2N7002")
      (footprint "eagle-import:SOT23")
      (fields (field (name "MFR") "Diodes, Guangdong Hotetech,NXP"))
      (libsource (lib "eagle-import") (part "2N7002"))
    )
    (comp (ref "T303")
      (value "IHW20N120R5")
      (footprint "eagle-import:TO-247AC")
      (fields (field (name "MFR") "Infineon"))
      (libsource (lib "eagle-import") (part "IHW20N120R5"))
    )
    (comp (ref "T304")
      (value "IHW20N120R5")
      (footprint "eagle-import:TO-247AC")
      (fields (field (name "MFR") "Infineon"))
      (libsource (lib "eagle-import") (part "IHW20N120R5"))
    )
    (comp (ref "T307")
      (value "2N7002")
      (footprint "eagle-import:SOT23")
      (fields (field (name "MFR") "Diodes, Guangdong Hotetech,NXP"))
      (libsource (lib "eagle-import") (part "2N7002"))
    )
    (comp (ref "T308")
      (value "2N7002")
      (footprint "eagle-import:SOT23")
      (fields (field (name "MFR") "Diodes, Guangdong Hotetech,NXP"))
      (libsource (lib "eagle-import") (part "2N7002"))
    )
    (comp (ref "T309")
      (value "2N7002")
      (footprint "eagle-import:SOT23")
      (fields (field (name "MFR") "Diodes, Guangdong Hotetech,NXP"))
      (libsource (lib "eagle-import") (part "2N7002"))
    )
    (comp (ref "T310")
      (value "2N7002")
      (footprint "eagle-import:SOT23")
      (fields (field (name "MFR") "Diodes, Guangdong Hotetech,NXP"))
      (libsource (lib "eagle-import") (part "2N7002"))
    )
    (comp (ref "T313")
      (value "2N7002")
      (footprint "eagle-import:SOT23")
      (fields (field (name "MFR") "Diodes, Guangdong Hotetech,NXP"))
      (libsource (lib "eagle-import") (part "2N7002"))
    )
    (comp (ref "TR300")
      (value "CST206-2A")
      (footprint "eagle-import:CST206-2A")
      (fields (field (name "MFR") "Trriad Magnetics"))
      (libsource (lib "eagle-import") (part "CST206-2A"))
    )
    (comp (ref "TR305")
      (value "11-0060-A")
      (footprint "eagle-import:11-0060-A")
      (fields (field (name "MFR") "Dongguan Speed Electronics"))
      (libsource (lib "eagle-import") (part "11-0060-A"))
    )
    (comp (ref "U300")
      (value "PAD_3MMX6MM")
      (footprint "eagle-import:PAD-3.0X6.0MM")
      (fields (field (name "MFR") "NA"))
      (libsource (lib "eagle-import") (part "PAD_3MMX6MM"))
    )
    (comp (ref "U301")
      (value "PAD_3MMX6MM")
      (footprint "eagle-import:PAD-3.0X6.0MM")
      (fields (field (name "MFR") "NA"))
      (libsource (lib "eagle-import") (part "PAD_3MMX6MM"))
    )
    (comp (ref "V300")
      (value "B72205S0271K101B72205S2131K101")
      (footprint "eagle-import:EPCOS_B72205S0271K101_0")
      (fields (field (name "MFR") "EPCOS"))
      (libsource (lib "eagle-import") (part "B72205S0271K101B72205S2131K101"))
    )
    (comp (ref "X2")
      (value "7461061")
      (footprint "eagle-import:X01_M10_7461061")
      (libsource (lib "eagle-import") (part "7461061"))
    )
    (comp (ref "X4")
      (value "7461061")
      (footprint "eagle-import:X01_M10_7461061")
      (libsource (lib "eagle-import") (part "7461061"))
    )
    (comp (ref "C500")
      (value "100nF/50V")
      (footprint "eagle-import:EIA0603")
      (libsource (lib "eagle-import") (part "C_0603EIA0603"))
    )
    (comp (ref "C501")
      (value "100nF/50V")
      (footprint "eagle-import:EIA0603")
      (libsource (lib "eagle-import") (part "C_0603EIA0603"))
    )
    (comp (ref "C502")
      (value "100nF/50V")
      (footprint "eagle-import:EIA0603")
      (libsource (lib "eagle-import") (part "C_0603EIA0603"))
    )
    (comp (ref "C503")
      (value "100nF/50V")
      (footprint "eagle-import:EIA0603")
      (libsource (lib "eagle-import") (part "C_0603EIA0603"))
    )
    (comp (ref "C504")
      (value "100nF/50V")
      (footprint "eagle-import:EIA0603")
      (libsource (lib "eagle-import") (part "C_0603EIA0603"))
    )
    (comp (ref "C505")
      (value "100nF/50V")
      (footprint "eagle-import:EIA0603")
      (libsource (lib "eagle-import") (part "C_0603EIA0603"))
    )
    (comp (ref "C506")
      (value "100nF/50V")
      (footprint "eagle-import:EIA0603")
      (libsource (lib "eagle-import") (part "C_0603EIA0603"))
    )
    (comp (ref "IC500")
      (value "SN65HVD3082EDR")
      (footprint "eagle-import:SOIC8")
      (fields (field (name "MFR") "TI,3Peak"))
      (libsource (lib "eagle-import") (part "SN65HVD3082EDR"))
    )
    (comp (ref "Q500")
      (value "DMP6185SEQ-13")
      (footprint "eagle-import:SOT223")
      (fields (field (name "MFR") "Diodes"))
      (libsource (lib "eagle-import") (part "DMP6185SEQ-13"))
    )
    (comp (ref "Q501")
      (value "BC817")
      (footprint "eagle-import:SOT23")
      (fields (field (name "MFR") "NXP"))
      (libsource (lib "eagle-import") (part "BC817"))
    )
    (comp (ref "Q502")
      (value "DMP6185SEQ-13")
      (footprint "eagle-import:SOT223")
      (fields (field (name "MFR") "Diodes"))
      (libsource (lib "eagle-import") (part "DMP6185SEQ-13"))
    )
    (comp (ref "Q503")
      (value "BC817")
      (footprint "eagle-import:SOT23")
      (fields (field (name "MFR") "NXP"))
      (libsource (lib "eagle-import") (part "BC817"))
    )
    (comp (ref "Q504")
      (value "DMP6185SEQ-13")
      (footprint "eagle-import:SOT223")
      (fields (field (name "MFR") "Diodes"))
      (libsource (lib "eagle-import") (part "DMP6185SEQ-13"))
    )
    (comp (ref "Q505")
      (value "BC817")
      (footprint "eagle-import:SOT23")
      (fields (field (name "MFR") "NXP"))
      (libsource (lib "eagle-import") (part "BC817"))
    )
    (comp (ref "Q506")
      (value "BC817")
      (footprint "eagle-import:SOT23")
      (fields (field (name "MFR") "NXP"))
      (libsource (lib "eagle-import") (part "BC817"))
    )
    (comp (ref "Q507")
      (value "BC817")
      (footprint "eagle-import:SOT23")
      (fields (field (name "MFR") "NXP"))
      (libsource (lib "eagle-import") (part "BC817"))
    )
    (comp (ref "R500")
      (value "10K 1%")
      (footprint "eagle-import:EIA0603")
      (libsource (lib "eagle-import") (part "R_0603"))
    )
    (comp (ref "R501")
      (value "10K 1%")
      (footprint "eagle-import:EIA0603")
      (libsource (lib "eagle-import") (part "R_0603"))
    )
    (comp (ref "R502")
      (value "100R 1%")
      (footprint "eagle-import:EIA0603")
      (libsource (lib "eagle-import") (part "R_0603"))
    )
    (comp (ref "R503")
      (value "10K 1%")
      (footprint "eagle-import:EIA0603")
      (libsource (lib "eagle-import") (part "R_0603"))
    )
    (comp (ref "R504")
      (value "1K 1%")
      (footprint "eagle-import:EIA0603")
      (libsource (lib "eagle-import") (part "R_0603"))
    )
    (comp (ref "R505")
      (value "10K 1%")
      (footprint "eagle-import:EIA0603")
      (libsource (lib "eagle-import") (part "R_0603"))
    )
    (comp (ref "R506")
      (value "100R 1%")
      (footprint "eagle-import:EIA0603")
      (libsource (lib "eagle-import") (part "R_0603"))
    )
    (comp (ref "R507")
      (value "10K 1%")
      (footprint "eagle-import:EIA0603")
      (libsource (lib "eagle-import") (part "R_0603"))
    )
    (comp (ref "R508")
      (value "100R 1%")
      (footprint "eagle-import:EIA0603")
      (libsource (lib "eagle-import") (part "R_0603"))
    )
    (comp (ref "R509")
      (value "1K 1%")
      (footprint "eagle-import:EIA0603")
      (libsource (lib "eagle-import") (part "R_0603"))
    )
    (comp (ref "R510")
      (value "10K 1%")
      (footprint "eagle-import:EIA0603")
      (libsource (lib "eagle-import") (part "R_0603"))
    )
    (comp (ref "R511")
      (value "100R 1%")
      (footprint "eagle-import:EIA0603")
      (libsource (lib "eagle-import") (part "R_0603"))
    )
    (comp (ref "R512")
      (value "10K 1%")
      (footprint "eagle-import:EIA0603")
      (libsource (lib "eagle-import") (part "R_0603"))
    )
    (comp (ref "R513")
      (value "100R 1%")
      (footprint "eagle-import:EIA0603")
      (libsource (lib "eagle-import") (part "R_0603"))
    )
    (comp (ref "R514")
      (value "10K 1%")
      (footprint "eagle-import:EIA0603")
      (libsource (lib "eagle-import") (part "R_0603"))
    )
    (comp (ref "R515")
      (value "10K 1%")
      (footprint "eagle-import:EIA0603")
      (libsource (lib "eagle-import") (part "R_0603"))
    )
    (comp (ref "R516")
      (value "10K 1%")
      (footprint "eagle-import:EIA0603")
      (libsource (lib "eagle-import") (part "R_0603"))
    )
    (comp (ref "R517")
      (value "100R 1%")
      (footprint "eagle-import:EIA0603")
      (libsource (lib "eagle-import") (part "R_0603"))
    )
    (comp (ref "R518")
      (value "100R 1%")
      (footprint "eagle-import:EIA0603")
      (libsource (lib "eagle-import") (part "R_0603"))
    )
    (comp (ref "R519")
      (value "10K 1%")
      (footprint "eagle-import:EIA0603")
      (libsource (lib "eagle-import") (part "R_0603"))
    )
    (comp (ref "R520")
      (value "470R 1%")
      (footprint "eagle-import:EIA0603")
      (libsource (lib "eagle-import") (part "R_0603"))
    )
    (comp (ref "R521")
      (value "100R 1%")
      (footprint "eagle-import:EIA0603")
      (libsource (lib "eagle-import") (part "R_0603"))
    )
    (comp (ref "R522")
      (value "470R 1%")
      (footprint "eagle-import:EIA0603")
      (libsource (lib "eagle-import") (part "R_0603"))
    )
    (comp (ref "R523")
      (value "100R 1%")
      (footprint "eagle-import:EIA0603")
      (libsource (lib "eagle-import") (part "R_0603"))
    )
    (comp (ref "R524")
      (value "100R 1%")
      (footprint "eagle-import:EIA0603")
      (libsource (lib "eagle-import") (part "R_0603"))
    )
    (comp (ref "R525")
      (value "470R 1%")
      (footprint "eagle-import:EIA0603")
      (libsource (lib "eagle-import") (part "R_0603"))
    )
    (comp (ref "R526")
      (value "0R 1%")
      (footprint "eagle-import:EIA0603")
      (libsource (lib "eagle-import") (part "R_0603"))
    )
    (comp (ref "R527")
      (value "0R 1%")
      (footprint "eagle-import:EIA0603")
      (libsource (lib "eagle-import") (part "R_0603"))
    )
    (comp (ref "R528")
      (value "100R 1%")
      (footprint "eagle-import:EIA0603")
      (libsource (lib "eagle-import") (part "R_0603"))
    )
    (comp (ref "T500")
      (value "2N7002")
      (footprint "eagle-import:SOT23")
      (fields (field (name "MFR") "Diodes, Guangdong Hotetech,NXP"))
      (libsource (lib "eagle-import") (part "2N7002"))
    )
    (comp (ref "T501")
      (value "2N7002")
      (footprint "eagle-import:SOT23")
      (fields (field (name "MFR") "Diodes, Guangdong Hotetech,NXP"))
      (libsource (lib "eagle-import") (part "2N7002"))
    )
    (comp (ref "T502")
      (value "2N7002")
      (footprint "eagle-import:SOT23")
      (fields (field (name "MFR") "Diodes, Guangdong Hotetech,NXP"))
      (libsource (lib "eagle-import") (part "2N7002"))
    )
    (comp (ref "V500")
      (value "0603ESDA-24NSMD")
      (footprint "eagle-import:EIA0603")
      (fields (field (name "MFR") "Bourns"))
      (libsource (lib "eagle-import") (part "0603ESDA-24NSMD"))
    )
    (comp (ref "V501")
      (value "0603ESDA-24NSMD")
      (footprint "eagle-import:EIA0603")
      (fields (field (name "MFR") "Bourns"))
      (libsource (lib "eagle-import") (part "0603ESDA-24NSMD"))
    )
    (comp (ref "V502")
      (value "0603ESDA-24NSMD")
      (footprint "eagle-import:EIA0603")
      (fields (field (name "MFR") "Bourns"))
      (libsource (lib "eagle-import") (part "0603ESDA-24NSMD"))
    )
    (comp (ref "V503")
      (value "0603ESDA-24NSMD")
      (footprint "eagle-import:EIA0603")
      (fields (field (name "MFR") "Bourns"))
      (libsource (lib "eagle-import") (part "0603ESDA-24NSMD"))
    )
    (comp (ref "V504")
      (value "0603ESDA-24NSMD")
      (footprint "eagle-import:EIA0603")
      (fields (field (name "MFR") "Bourns"))
      (libsource (lib "eagle-import") (part "0603ESDA-24NSMD"))
    )
    (comp (ref "X5")
      (value "615008148521")
      (footprint "eagle-import:615008148521")
      (fields (field (name "MFR") "Wurth Elektronik"))
      (libsource (lib "eagle-import") (part "615008148521"))
    )
    (comp (ref "X6")
      (value "615008148521")
      (footprint "eagle-import:615008148521")
      (fields (field (name "MFR") "Wurth Elektronik"))
      (libsource (lib "eagle-import") (part "615008148521"))
    )
    (comp (ref "X7")
      (value "2304-6111-TP")
      (footprint "eagle-import:X04_100MIL")
      (fields (field (name "MFR") "3M"))
      (libsource (lib "eagle-import") (part "2304-6111-TP"))
    )
    (comp (ref "X8")
      (value "2304-6111-TP")
      (footprint "eagle-import:X04_100MIL")
      (fields (field (name "MFR") "3M"))
      (libsource (lib "eagle-import") (part "2304-6111-TP"))
    )
  )
  (nets
    (net (code "1") (name "AI_I_OUT") (class "Default")
      (node (ref "C433") (pin "2") (pinfunction "2_2") (pintype "passive"))
      (node (ref "IC301") (pin "1") (pinfunction "OUT_1") (pintype "passive"))
      (node (ref "IC400") (pin "113") (pinfunction "P500_113") (pintype "bidirectional"))
      (node (ref "R339") (pin "1") (pinfunction "1_1") (pintype "passive"))
      (node (ref "R345") (pin "2") (pinfunction "2_2") (pintype "passive"))
    )
    (net (code "2") (name "AN_OUTA_H") (class "Default")
      (node (ref "IC306") (pin "4") (pinfunction "OUTH_4") (pintype "passive"))
      (node (ref "R325") (pin "2") (pinfunction "2_2") (pintype "passive"))
    )
    (net (code "3") (name "AN_OUTA_L") (class "Default")
      (node (ref "IC306") (pin "6") (pinfunction "OUTL_6") (pintype "passive"))
      (node (ref "R327") (pin "2") (pinfunction "2_2") (pintype "passive"))
    )
    (net (code "4") (name "AN_OUTB_H") (class "Default")
      (node (ref "IC307") (pin "4") (pinfunction "OUTH_4") (pintype "passive"))
      (node (ref "R304") (pin "2") (pinfunction "2_2") (pintype "passive"))
    )
    (net (code "5") (name "AN_OUTB_L") (class "Default")
      (node (ref "IC307") (pin "6") (pinfunction "OUTL_6") (pintype "passive"))
      (node (ref "R313") (pin "2") (pinfunction "2_2") (pintype "passive"))
    )
    (net (code "6") (name "AN_OUTC_H") (class "Default")
      (node (ref "IC310") (pin "4") (pinfunction "OUTH_4") (pintype "passive"))
      (node (ref "R332") (pin "2") (pinfunction "2_2") (pintype "passive"))
    )
    (net (code "7") (name "AN_OUTC_L") (class "Default")
      (node (ref "IC310") (pin "6") (pinfunction "OUTL_6") (pintype "passive"))
      (node (ref "R385") (pin "2") (pinfunction "2_2") (pintype "passive"))
    )
    (net (code "8") (name "AN_OUTD_H") (class "Default")
      (node (ref "IC311") (pin "4") (pinfunction "OUTH_4") (pintype "passive"))
      (node (ref "R387") (pin "2") (pinfunction "2_2") (pintype "passive"))
    )
    (net (code "9") (name "AN_OUTD_L") (class "Default")
      (node (ref "IC311") (pin "6") (pinfunction "OUTL_6") (pintype "passive"))
      (node (ref "R396") (pin "2") (pinfunction "2_2") (pintype "passive"))
    )
    (net (code "10") (name "BCD_A") (class "Default")
      (node (ref "C500") (pin "1") (pinfunction "1_1") (pintype "passive"))
      (node (ref "Q501") (pin "3") (pinfunction "C_3") (pintype "passive"))
      (node (ref "X8") (pin "1") (pinfunction "1_1") (pintype "bidirectional"))
    )
    (net (code "11") (name "BCD_B") (class "Default")
      (node (ref "C501") (pin "1") (pinfunction "1_1") (pintype "passive"))
      (node (ref "Q503") (pin "3") (pinfunction "C_3") (pintype "passive"))
      (node (ref "X8") (pin "2") (pinfunction "2_2") (pintype "bidirectional"))
    )
    (net (code "12") (name "BCD_C") (class "Default")
      (node (ref "C502") (pin "1") (pinfunction "1_1") (pintype "passive"))
      (node (ref "Q505") (pin "3") (pinfunction "C_3") (pintype "passive"))
      (node (ref "X8") (pin "3") (pinfunction "3_3") (pintype "bidirectional"))
    )
    (net (code "13") (name "BCD_D") (class "Default")
      (node (ref "C506") (pin "1") (pinfunction "1_1") (pintype "passive"))
      (node (ref "Q507") (pin "3") (pinfunction "C_3") (pintype "passive"))
      (node (ref "X8") (pin "4") (pinfunction "4_4") (pintype "bidirectional"))
    )
    (net (code "14") (name "CTRLR_OUTA") (class "Default")
      (node (ref "IC1") (pin "22") (pinfunction "OUTA_22") (pintype "bidirectional"))
      (node (ref "R358") (pin "1") (pinfunction "1_1") (pintype "passive"))
    )
    (net (code "15") (name "CTRLR_OUTB") (class "Default")
      (node (ref "IC1") (pin "21") (pinfunction "OUTB_21") (pintype "bidirectional"))
      (node (ref "R370") (pin "1") (pinfunction "1_1") (pintype "passive"))
    )
    (net (code "16") (name "CTRLR_OUTC") (class "Default")
      (node (ref "IC1") (pin "20") (pinfunction "OUTC_20") (pintype "bidirectional"))
      (node (ref "R380") (pin "1") (pinfunction "1_1") (pintype "passive"))
    )
    (net (code "17") (name "CTRLR_OUTD") (class "Default")
      (node (ref "IC1") (pin "19") (pinfunction "OUTD_19") (pintype "bidirectional"))
      (node (ref "R384") (pin "1") (pinfunction "1_1") (pintype "passive"))
    )
    (net (code "18") (name "DBG_TDI") (class "Default")
      (node (ref "IC400") (pin "75") (pinfunction "P110/TDI_75") (pintype "bidirectional"))
      (node (ref "X403") (pin "1") (pinfunction "1_1") (pintype "bidirectional"))
    )
    (net (code "19") (name "DGB_SWDIO_TCK") (class "Default")
      (node (ref "IC400") (pin "72") (pinfunction "P300/TCK/SWCLK_72") (pintype "bidirectional"))
      (node (ref "X403") (pin "7") (pinfunction "7_7") (pintype "bidirectional"))
    )
    (net (code "20") (name "DGB_SWDIO_TDO") (class "Default")
      (node (ref "IC400") (pin "74") (pinfunction "P109/TDO_74") (pintype "bidirectional"))
      (node (ref "X403") (pin "3") (pinfunction "3_3") (pintype "bidirectional"))
    )
    (net (code "21") (name "DGB_SWDIO_TMS") (class "Default")
      (node (ref "IC400") (pin "73") (pinfunction "P108/TMS/SWDIO_73") (pintype "bidirectional"))
      (node (ref "X403") (pin "5") (pinfunction "5_5") (pintype "bidirectional"))
    )
    (net (code "22") (name "DISP1_VCC") (class "Default")
      (node (ref "Q504") (pin "2") (pinfunction "DRAIN_2") (pintype "passive"))
      (node (ref "Q504") (pin "4") (pinfunction "DRAIN_4") (pintype "passive"))
      (node (ref "V502") (pin "2") (pinfunction "2_2") (pintype "passive"))
      (node (ref "X7") (pin "1") (pinfunction "1_1") (pintype "bidirectional"))
    )
    (net (code "23") (name "DISP2_VCC") (class "Default")
      (node (ref "Q502") (pin "2") (pinfunction "DRAIN_2") (pintype "passive"))
      (node (ref "Q502") (pin "4") (pinfunction "DRAIN_4") (pintype "passive"))
      (node (ref "V501") (pin "2") (pinfunction "2_2") (pintype "passive"))
      (node (ref "X7") (pin "2") (pinfunction "2_2") (pintype "bidirectional"))
    )
    (net (code "24") (name "DISP3_VCC") (class "Default")
      (node (ref "Q500") (pin "2") (pinfunction "DRAIN_2") (pintype "passive"))
      (node (ref "Q500") (pin "4") (pinfunction "DRAIN_4") (pintype "passive"))
      (node (ref "V500") (pin "2") (pinfunction "2_2") (pintype "passive"))
      (node (ref "X7") (pin "3") (pinfunction "3_3") (pintype "bidirectional"))
    )
    (net (code "25") (name "DI_G_DRV_RDY") (class "Default")
      (node (ref "C370") (pin "2") (pinfunction "2_2") (pintype "passive"))
      (node (ref "C373") (pin "2") (pinfunction "2_2") (pintype "passive"))
      (node (ref "C376") (pin "2") (pinfunction "2_2") (pintype "passive"))
      (node (ref "C379") (pin "2") (pinfunction "2_2") (pintype "passive"))
      (node (ref "C400") (pin "2") (pinfunction "2_2") (pintype "passive"))
      (node (ref "IC306") (pin "12") (pinfunction "RDY_12") (pintype "passive"))
      (node (ref "IC307") (pin "12") (pinfunction "RDY_12") (pintype "passive"))
      (node (ref "IC310") (pin "12") (pinfunction "RDY_12") (pintype "passive"))
      (node (ref "IC311") (pin "12") (pinfunction "RDY_12") (pintype "passive"))
      (node (ref "IC400") (pin "85") (pinfunction "P610_85") (pintype "bidirectional"))
      (node (ref "R303") (pin "2") (pinfunction "2_2") (pintype "passive"))
      (node (ref "R407") (pin "2") (pinfunction "2_2") (pintype "passive"))
      (node (ref "R413") (pin "2") (pinfunction "2_2") (pintype "passive"))
      (node (ref "R419") (pin "2") (pinfunction "2_2") (pintype "passive"))
      (node (ref "R448") (pin "1") (pinfunction "1_1") (pintype "passive"))
      (node (ref "X400") (pin "2") (pinfunction "2_2") (pintype "bidirectional"))
    )
    (net (code "26") (name "DI_UART_RX") (class "Default")
      (node (ref "IC400") (pin "35") (pinfunction "P408_35") (pintype "bidirectional"))
      (node (ref "Q506") (pin "3") (pinfunction "C_3") (pintype "passive"))
      (node (ref "R515") (pin "2") (pinfunction "2_2") (pintype "passive"))
    )
    (net (code "27") (name "DO_7SEG_BCD_A") (class "Default")
      (node (ref "IC400") (pin "71") (pinfunction "P301_71") (pintype "bidirectional"))
      (node (ref "R504") (pin "2") (pinfunction "2_2") (pintype "passive"))
    )
    (net (code "28") (name "DO_7SEG_BCD_B") (class "Default")
      (node (ref "IC400") (pin "70") (pinfunction "P302_70") (pintype "bidirectional"))
      (node (ref "R509") (pin "2") (pinfunction "2_2") (pintype "passive"))
    )
    (net (code "29") (name "DO_7SEG_BCD_C") (class "Default")
      (node (ref "IC400") (pin "69") (pinfunction "P303_69") (pintype "bidirectional"))
      (node (ref "R513") (pin "2") (pinfunction "2_2") (pintype "passive"))
    )
    (net (code "30") (name "DO_7SEG_BCD_D") (class "Default")
      (node (ref "IC400") (pin "66") (pinfunction "P304_66") (pintype "bidirectional"))
      (node (ref "R524") (pin "2") (pinfunction "2_2") (pintype "passive"))
    )
    (net (code "31") (name "DO_7SEG_DISP1_EN") (class "Default")
      (node (ref "IC400") (pin "65") (pinfunction "P305_65") (pintype "bidirectional"))
      (node (ref "R517") (pin "2") (pinfunction "2_2") (pintype "passive"))
    )
    (net (code "32") (name "DO_7SEG_DISP2_EN") (class "Default")
      (node (ref "IC400") (pin "64") (pinfunction "P306_64") (pintype "bidirectional"))
      (node (ref "R508") (pin "2") (pinfunction "2_2") (pintype "passive"))
    )
    (net (code "33") (name "DO_7SEG_DISP3_EN") (class "Default")
      (node (ref "IC400") (pin "63") (pinfunction "P307_63") (pintype "bidirectional"))
      (node (ref "R502") (pin "2") (pinfunction "2_2") (pintype "passive"))
    )
    (net (code "34") (name "DO_ABRUPT_I_OFF") (class "Default")
      (node (ref "IC400") (pin "118") (pinfunction "P505_118") (pintype "bidirectional"))
      (node (ref "R462") (pin "1") (pinfunction "1_1") (pintype "passive"))
    )
    (net (code "35") (name "DO_COMM_TX_EN") (class "Default")
      (node (ref "IC400") (pin "33") (pinfunction "P410_33") (pintype "bidirectional"))
      (node (ref "R522") (pin "2") (pinfunction "2_2") (pintype "passive"))
    )
    (net (code "36") (name "DO_I_SET_PWM") (class "Default")
      (node (ref "IC400") (pin "97") (pinfunction "P601_97") (pintype "bidirectional"))
      (node (ref "R349") (pin "1") (pinfunction "1_1") (pintype "passive"))
      (node (ref "V401") (pin "2") (pinfunction "2_2") (pintype "passive"))
      (node (ref "X401") (pin "2") (pinfunction "2_2") (pintype "bidirectional"))
    )
    (net (code "37") (name "DO_PSFB_CTRL_ON") (class "Default")
      (node (ref "IC400") (pin "98") (pinfunction "P600_98") (pintype "bidirectional"))
    )
    (net (code "38") (name "DO_UART_TX") (class "Default")
      (node (ref "IC400") (pin "34") (pinfunction "P409_34") (pintype "bidirectional"))
      (node (ref "R525") (pin "2") (pinfunction "2_2") (pintype "passive"))
    )
    (net (code "39") (name "DO_V_SET_PWM") (class "Default")
      (node (ref "R320") (pin "1") (pinfunction "1_1") (pintype "passive"))
      (node (ref "V402") (pin "2") (pinfunction "2_2") (pintype "passive"))
      (node (ref "X401") (pin "3") (pinfunction "3_3") (pintype "bidirectional"))
    )
    (net (code "40") (name "EA_IN") (class "Default")
      (node (ref "D302") (pin "2") (pinfunction "A_2") (pintype "passive"))
      (node (ref "D306") (pin "2") (pinfunction "A_2") (pintype "passive"))
      (node (ref "R305") (pin "2") (pinfunction "2_2") (pintype "passive"))
      (node (ref "R336") (pin "2") (pinfunction "2_2") (pintype "passive"))
      (node (ref "R461") (pin "1") (pinfunction "1_1") (pintype "passive"))
    )
    (net (code "41") (name "GND") (class "Default")
      (node (ref "C108") (pin "1") (pinfunction "1_1") (pintype "passive"))
      (node (ref "C200") (pin "1") (pinfunction "1_1") (pintype "passive"))
      (node (ref "C201") (pin "2") (pinfunction "-_2") (pintype "passive"))
      (node (ref "C202") (pin "2") (pinfunction "-_2") (pintype "passive"))
      (node (ref "C203") (pin "1") (pinfunction "1_1") (pintype "passive"))
      (node (ref "C204") (pin "1") (pinfunction "1_1") (pintype "passive"))
      (node (ref "C205") (pin "2") (pinfunction "-_2") (pintype "passive"))
      (node (ref "C306") (pin "1") (pinfunction "1_1") (pintype "passive"))
      (node (ref "C309") (pin "2") (pinfunction "2_2") (pintype "passive"))
      (node (ref "C310") (pin "2") (pinfunction "2_2") (pintype "passive"))
      (node (ref "C314") (pin "2") (pinfunction "2_2") (pintype "passive"))
      (node (ref "C317") (pin "2") (pinfunction "2_2") (pintype "passive"))
      (node (ref "C318") (pin "2") (pinfunction "2_2") (pintype "passive"))
      (node (ref "C319") (pin "2") (pinfunction "2_2") (pintype "passive"))
      (node (ref "C320") (pin "1") (pinfunction "1_1") (pintype "passive"))
      (node (ref "C323") (pin "1") (pinfunction "1_1") (pintype "passive"))
      (node (ref "C324") (pin "1") (pinfunction "1_1") (pintype "passive"))
      (node (ref "C325") (pin "2") (pinfunction "2_2") (pintype "passive"))
      (node (ref "C328") (pin "1") (pinfunction "1_1") (pintype "passive"))
      (node (ref "C329") (pin "1") (pinfunction "1_1") (pintype "passive"))
      (node (ref "C332") (pin "1") (pinfunction "1_1") (pintype "passive"))
      (node (ref "C333") (pin "1") (pinfunction "1_1") (pintype "passive"))
      (node (ref "C334") (pin "1") (pinfunction "1_1") (pintype "passive"))
      (node (ref "C337") (pin "2") (pinfunction "2_2") (pintype "passive"))
      (node (ref "C338") (pin "1") (pinfunction "1_1") (pintype "passive"))
      (node (ref "C343") (pin "1") (pinfunction "1_1") (pintype "passive"))
      (node (ref "C344") (pin "1") (pinfunction "1_1") (pintype "passive"))
      (node (ref "C346") (pin "2") (pinfunction "2_2") (pintype "passive"))
      (node (ref "C347") (pin "2") (pinfunction "2_2") (pintype "passive"))
      (node (ref "C348") (pin "2") (pinfunction "2_2") (pintype "passive"))
      (node (ref "C360") (pin "1") (pinfunction "1_1") (pintype "passive"))
      (node (ref "C361") (pin "1") (pinfunction "1_1") (pintype "passive"))
      (node (ref "C363") (pin "1") (pinfunction "1_1") (pintype "passive"))
      (node (ref "C364") (pin "1") (pinfunction "1_1") (pintype "passive"))
      (node (ref "C370") (pin "1") (pinfunction "1_1") (pintype "passive"))
      (node (ref "C371") (pin "1") (pinfunction "1_1") (pintype "passive"))
      (node (ref "C372") (pin "1") (pinfunction "1_1") (pintype "passive"))
      (node (ref "C373") (pin "1") (pinfunction "1_1") (pintype "passive"))
      (node (ref "C374") (pin "1") (pinfunction "1_1") (pintype "passive"))
      (node (ref "C375") (pin "1") (pinfunction "1_1") (pintype "passive"))
      (node (ref "C376") (pin "1") (pinfunction "1_1") (pintype "passive"))
      (node (ref "C377") (pin "1") (pinfunction "1_1") (pintype "passive"))
      (node (ref "C378") (pin "1") (pinfunction "1_1") (pintype "passive"))
      (node (ref "C379") (pin "1") (pinfunction "1_1") (pintype "passive"))
      (node (ref "C380") (pin "1") (pinfunction "1_1") (pintype "passive"))
      (node (ref "C381") (pin "1") (pinfunction "1_1") (pintype "passive"))
      (node (ref "C383") (pin "1") (pinfunction "1_1") (pintype "passive"))
      (node (ref "C400") (pin "1") (pinfunction "1_1") (pintype "passive"))
      (node (ref "C401") (pin "1") (pinfunction "1_1") (pintype "passive"))
      (node (ref "C402") (pin "1") (pinfunction "1_1") (pintype "passive"))
      (node (ref "C403") (pin "1") (pinfunction "1_1") (pintype "passive"))
      (node (ref "C404") (pin "1") (pinfunction "1_1") (pintype "passive"))
      (node (ref "C405") (pin "1") (pinfunction "1_1") (pintype "passive"))
      (node (ref "C407") (pin "1") (pinfunction "1_1") (pintype "passive"))
      (node (ref "C416") (pin "2") (pinfunction "2_2") (pintype "passive"))
      (node (ref "C417") (pin "2") (pinfunction "2_2") (pintype "passive"))
      (node (ref "C418") (pin "2") (pinfunction "2_2") (pintype "passive"))
      (node (ref "C421") (pin "1") (pinfunction "1_1") (pintype "passive"))
      (node (ref "C422") (pin "2") (pinfunction "2_2") (pintype "passive"))
      (node (ref "C439") (pin "1") (pinfunction "1_1") (pintype "passive"))
      (node (ref "C440") (pin "2") (pinfunction "2_2") (pintype "passive"))
      (node (ref "C441") (pin "2") (pinfunction "2_2") (pintype "passive"))
      (node (ref "C442") (pin "1") (pinfunction "1_1") (pintype "passive"))
      (node (ref "C443") (pin "1") (pinfunction "1_1") (pintype "passive"))
      (node (ref "C444") (pin "1") (pinfunction "1_1") (pintype "passive"))
      (node (ref "C445") (pin "2") (pinfunction "2_2") (pintype "passive"))
      (node (ref "C446") (pin "2") (pinfunction "2_2") (pintype "passive"))
      (node (ref "C447") (pin "2") (pinfunction "2_2") (pintype "passive"))
      (node (ref "C448") (pin "1") (pinfunction "1_1") (pintype "passive"))
      (node (ref "C449") (pin "1") (pinfunction "1_1") (pintype "passive"))
      (node (ref "C450") (pin "2") (pinfunction "2_2") (pintype "passive"))
      (node (ref "C451") (pin "1") (pinfunction "1_1") (pintype "passive"))
      (node (ref "C452") (pin "2") (pinfunction "2_2") (pintype "passive"))
      (node (ref "C453") (pin "2") (pinfunction "2_2") (pintype "passive"))
      (node (ref "C454") (pin "2") (pinfunction "2_2") (pintype "passive"))
      (node (ref "C455") (pin "2") (pinfunction "2_2") (pintype "passive"))
      (node (ref "C456") (pin "2") (pinfunction "2_2") (pintype "passive"))
      (node (ref "C457") (pin "2") (pinfunction "2_2") (pintype "passive"))
      (node (ref "C458") (pin "2") (pinfunction "2_2") (pintype "passive"))
      (node (ref "C500") (pin "2") (pinfunction "2_2") (pintype "passive"))
      (node (ref "C501") (pin "2") (pinfunction "2_2") (pintype "passive"))
      (node (ref "C502") (pin "2") (pinfunction "2_2") (pintype "passive"))
      (node (ref "C503") (pin "1") (pinfunction "1_1") (pintype "passive"))
      (node (ref "C504") (pin "1") (pinfunction "1_1") (pintype "passive"))
      (node (ref "C505") (pin "1") (pinfunction "1_1") (pintype "passive"))
      (node (ref "C506") (pin "2") (pinfunction "2_2") (pintype "passive"))
      (node (ref "D105") (pin "A") (pinfunction "A_A") (pintype "passive"))
      (node (ref "D324") (pin "1") (pinfunction "A1_1") (pintype "passive"))
      (node (ref "IC1") (pin "24") (pinfunction "GND_24") (pintype "bidirectional"))
      (node (ref "IC100") (pin "3") (pinfunction "EMITTER_3") (pintype "passive"))
      (node (ref "IC300") (pin "2") (pinfunction "VEE_2") (pintype "passive"))
      (node (ref "IC301") (pin "2") (pinfunction "VEE_2") (pintype "passive"))
      (node (ref "IC302") (pin "2") (pinfunction "VEE_2") (pintype "passive"))
      (node (ref "IC306") (pin "11") (pinfunction "IN-_11") (pintype "passive"))
      (node (ref "IC306") (pin "9") (pinfunction "GND_9") (pintype "passive"))
      (node (ref "IC307") (pin "11") (pinfunction "IN-_11") (pintype "passive"))
      (node (ref "IC307") (pin "9") (pinfunction "GND_9") (pintype "passive"))
      (node (ref "IC310") (pin "11") (pinfunction "IN-_11") (pintype "passive"))
      (node (ref "IC310") (pin "9") (pinfunction "GND_9") (pintype "passive"))
      (node (ref "IC311") (pin "11") (pinfunction "IN-_11") (pintype "passive"))
      (node (ref "IC311") (pin "9") (pinfunction "GND_9") (pintype "passive"))
      (node (ref "IC400") (pin "100") (pinfunction "VSS_4_100") (pintype "power_in"))
      (node (ref "IC400") (pin "112") (pinfunction "VSS_5_112") (pintype "power_in"))
      (node (ref "IC400") (pin "122") (pinfunction "VSS_6_122") (pintype "power_in"))
      (node (ref "IC400") (pin "125") (pinfunction "VREFL_125") (pintype "power_in"))
      (node (ref "IC400") (pin "128") (pinfunction "AVSS0_128") (pintype "power_in"))
      (node (ref "IC400") (pin "141") (pinfunction "VSS_141") (pintype "power_in"))
      (node (ref "IC400") (pin "18") (pinfunction "VSS_2_18") (pintype "power_in"))
      (node (ref "IC400") (pin "48") (pinfunction "VSS_3_48") (pintype "power_in"))
      (node (ref "IC400") (pin "67") (pinfunction "VSS_67") (pintype "power_in"))
      (node (ref "IC400") (pin "82") (pinfunction "VSS_2_82") (pintype "power_in"))
      (node (ref "IC400") (pin "91") (pinfunction "VSS_3_91") (pintype "power_in"))
      (node (ref "IC401") (pin "2") (pinfunction "GND_2") (pintype "power_in"))
      (node (ref "IC500") (pin "5") (pinfunction "GND_5") (pintype "bidirectional"))
      (node (ref "Q100") (pin "2") (pinfunction "C_2") (pintype "passive"))
      (node (ref "Q300") (pin "2") (pinfunction "S_2") (pintype "passive"))
      (node (ref "Q306") (pin "2") (pinfunction "S_2") (pintype "passive"))
      (node (ref "R115") (pin "1") (pinfunction "1_1") (pintype "passive"))
      (node (ref "R201") (pin "1") (pinfunction "1_1") (pintype "passive"))
      (node (ref "R316") (pin "1") (pinfunction "1_1") (pintype "passive"))
      (node (ref "R321") (pin "1") (pinfunction "1_1") (pintype "passive"))
      (node (ref "R324") (pin "1") (pinfunction "1_1") (pintype "passive"))
      (node (ref "R334") (pin "2") (pinfunction "2_2") (pintype "passive"))
      (node (ref "R340") (pin "1") (pinfunction "1_1") (pintype "passive"))
      (node (ref "R344") (pin "1") (pinfunction "1_1") (pintype "passive"))
      (node (ref "R350") (pin "1") (pinfunction "1_1") (pintype "passive"))
      (node (ref "R351") (pin "1") (pinfunction "1_1") (pintype "passive"))
      (node (ref "R355") (pin "2") (pinfunction "2_2") (pintype "passive"))
      (node (ref "R357") (pin "2") (pinfunction "2_2") (pintype "passive"))
      (node (ref "R359") (pin "2") (pinfunction "2_2") (pintype "passive"))
      (node (ref "R360") (pin "2") (pinfunction "2_2") (pintype "passive"))
      (node (ref "R362") (pin "2") (pinfunction "2_2") (pintype "passive"))
      (node (ref "R364") (pin "2") (pinfunction "2_2") (pintype "passive"))
      (node (ref "R365") (pin "2") (pinfunction "2_2") (pintype "passive"))
      (node (ref "R371") (pin "2") (pinfunction "2_2") (pintype "passive"))
      (node (ref "R375") (pin "2") (pinfunction "2_2") (pintype "passive"))
      (node (ref "R376") (pin "2") (pinfunction "2_2") (pintype "passive"))
      (node (ref "R377") (pin "2") (pinfunction "2_2") (pintype "passive"))
      (node (ref "R379") (pin "1") (pinfunction "1_1") (pintype "passive"))
      (node (ref "R382") (pin "2") (pinfunction "2_2") (pintype "passive"))
      (node (ref "R386") (pin "2") (pinfunction "2_2") (pintype "passive"))
      (node (ref "R389") (pin "1") (pinfunction "1_1") (pintype "passive"))
      (node (ref "R391") (pin "1") (pinfunction "1_1") (pintype "passive"))
      (node (ref "R437") (pin "2") (pinfunction "2_2") (pintype "passive"))
      (node (ref "R438") (pin "1") (pinfunction "1_1") (pintype "passive"))
      (node (ref "R463") (pin "1") (pinfunction "1_1") (pintype "passive"))
      (node (ref "R503") (pin "1") (pinfunction "1_1") (pintype "passive"))
      (node (ref "R506") (pin "1") (pinfunction "1_1") (pintype "passive"))
      (node (ref "R510") (pin "1") (pinfunction "1_1") (pintype "passive"))
      (node (ref "R511") (pin "1") (pinfunction "1_1") (pintype "passive"))
      (node (ref "R518") (pin "1") (pinfunction "1_1") (pintype "passive"))
      (node (ref "R519") (pin "1") (pinfunction "1_1") (pintype "passive"))
      (node (ref "R528") (pin "1") (pinfunction "1_1") (pintype "passive"))
      (node (ref "T302") (pin "2") (pinfunction "S_2") (pintype "passive"))
      (node (ref "T313") (pin "2") (pinfunction "S_2") (pintype "passive"))
      (node (ref "T500") (pin "2") (pinfunction "S_2") (pintype "passive"))
      (node (ref "T501") (pin "2") (pinfunction "S_2") (pintype "passive"))
      (node (ref "T502") (pin "2") (pinfunction "S_2") (pintype "passive"))
      (node (ref "TR300") (pin "1") (pinfunction "1_1") (pintype "bidirectional"))
      (node (ref "TR305") (pin "2") (pinfunction "2_2") (pintype "bidirectional"))
      (node (ref "TR305") (pin "4") (pinfunction "4_4") (pintype "bidirectional"))
      (node (ref "V400") (pin "1") (pinfunction "1_1") (pintype "passive"))
      (node (ref "V401") (pin "1") (pinfunction "1_1") (pintype "passive"))
      (node (ref "V402") (pin "1") (pinfunction "1_1") (pintype "passive"))
      (node (ref "V500") (pin "1") (pinfunction "1_1") (pintype "passive"))
      (node (ref "V501") (pin "1") (pinfunction "1_1") (pintype "passive"))
      (node (ref "V502") (pin "1") (pinfunction "1_1") (pintype "passive"))
      (node (ref "V503") (pin "1") (pinfunction "1_1") (pintype "passive"))
      (node (ref "V504") (pin "1") (pinfunction "1_1") (pintype "passive"))
      (node (ref "X204") (pin "5") (pinfunction "5_5") (pintype "passive"))
      (node (ref "X204") (pin "6") (pinfunction "6_6") (pintype "passive"))
      (node (ref "X400") (pin "4") (pinfunction "4_4") (pintype "bidirectional"))
      (node (ref "X401") (pin "1") (pinfunction "1_1") (pintype "bidirectional"))
      (node (ref "X403") (pin "10") (pinfunction "10_10") (pintype "bidirectional"))
      (node (ref "X403") (pin "6") (pinfunction "6_6") (pintype "bidirectional"))
      (node (ref "X403") (pin "8") (pinfunction "8_8") (pintype "bidirectional"))
      (node (ref "X7") (pin "4") (pinfunction "4_4") (pintype "bidirectional"))
    )
    (net (code "42") (name "G_DRV1_VCC") (class "Default")
      (node (ref "C332") (pin "2") (pinfunction "2_2") (pintype "passive"))
      (node (ref "C333") (pin "2") (pinfunction "2_2") (pintype "passive"))
      (node (ref "IC306") (pin "15") (pinfunction "VCC_15") (pintype "passive"))
      (node (ref "L302") (pin "2") (pinfunction "P$2_2") (pintype "bidirectional"))
      (node (ref "R303") (pin "1") (pinfunction "1_1") (pintype "passive"))
      (node (ref "R308") (pin "1") (pinfunction "1_1") (pintype "passive"))
      (node (ref "R390") (pin "1") (pinfunction "1_1") (pintype "passive"))
    )
    (net (code "43") (name "G_DRV2_VCC") (class "Default")
      (node (ref "C343") (pin "2") (pinfunction "2_2") (pintype "passive"))
      (node (ref "C344") (pin "2") (pinfunction "2_2") (pintype "passive"))
      (node (ref "IC307") (pin "15") (pinfunction "VCC_15") (pintype "passive"))
      (node (ref "L304") (pin "2") (pinfunction "P$2_2") (pintype "bidirectional"))
      (node (ref "R407") (pin "1") (pinfunction "1_1") (pintype "passive"))
      (node (ref "R408") (pin "1") (pinfunction "1_1") (pintype "passive"))
      (node (ref "R409") (pin "1") (pinfunction "1_1") (pintype "passive"))
    )
    (net (code "44") (name "G_DRV3_VCC") (class "Default")
      (node (ref "C360") (pin "2") (pinfunction "2_2") (pintype "passive"))
      (node (ref "C361") (pin "2") (pinfunction "2_2") (pintype "passive"))
      (node (ref "IC310") (pin "15") (pinfunction "VCC_15") (pintype "passive"))
      (node (ref "L308") (pin "2") (pinfunction "P$2_2") (pintype "bidirectional"))
      (node (ref "R413") (pin "1") (pinfunction "1_1") (pintype "passive"))
      (node (ref "R414") (pin "1") (pinfunction "1_1") (pintype "passive"))
      (node (ref "R415") (pin "1") (pinfunction "1_1") (pintype "passive"))
    )
    (net (code "45") (name "G_DRV4_VCC") (class "Default")
      (node (ref "C363") (pin "2") (pinfunction "2_2") (pintype "passive"))
      (node (ref "C364") (pin "2") (pinfunction "2_2") (pintype "passive"))
      (node (ref "IC311") (pin "15") (pinfunction "VCC_15") (pintype "passive"))
      (node (ref "L309") (pin "2") (pinfunction "P$2_2") (pintype "bidirectional"))
      (node (ref "R419") (pin "1") (pinfunction "1_1") (pintype "passive"))
      (node (ref "R420") (pin "1") (pinfunction "1_1") (pintype "passive"))
      (node (ref "R421") (pin "1") (pinfunction "1_1") (pintype "passive"))
    )
    (net (code "46") (name "G_DRV_INA") (class "Default")
      (node (ref "IC306") (pin "10") (pinfunction "IN+_10") (pintype "passive"))
      (node (ref "R353") (pin "1") (pinfunction "1_1") (pintype "passive"))
      (node (ref "R355") (pin "1") (pinfunction "1_1") (pintype "passive"))
    )
    (net (code "47") (name "G_DRV_INB") (class "Default")
      (node (ref "IC307") (pin "10") (pinfunction "IN+_10") (pintype "passive"))
      (node (ref "R361") (pin "1") (pinfunction "1_1") (pintype "passive"))
      (node (ref "R364") (pin "1") (pinfunction "1_1") (pintype "passive"))
    )
    (net (code "48") (name "G_DRV_INC") (class "Default")
      (node (ref "IC310") (pin "10") (pinfunction "IN+_10") (pintype "passive"))
      (node (ref "R373") (pin "1") (pinfunction "1_1") (pintype "passive"))
      (node (ref "R377") (pin "1") (pinfunction "1_1") (pintype "passive"))
    )
    (net (code "49") (name "G_DRV_IND") (class "Default")
      (node (ref "IC311") (pin "10") (pinfunction "IN+_10") (pintype "passive"))
      (node (ref "R381") (pin "1") (pinfunction "1_1") (pintype "passive"))
      (node (ref "R382") (pin "1") (pinfunction "1_1") (pintype "passive"))
    )
    (net (code "50") (name "MAINS_L") (class "Default")
      (node (ref "V100") (pin "2") (pinfunction "2_2") (pintype "passive"))
      (node (ref "X1") (pin "1") (pinfunction "1_1") (pintype "passive"))
      (node (ref "X1") (pin "1-2") (pinfunction "1_1-2") (pintype "passive"))
      (node (ref "X100") (pin "1") (pinfunction "P$1_1") (pintype "bidirectional"))
      (node (ref "X100") (pin "1-1") (pinfunction "P$1_1-1") (pintype "bidirectional"))
    )
    (net (code "51") (name "MAINS_L_FUSED") (class "Default")
      (node (ref "C102") (pin "2") (pinfunction "2_2") (pintype "passive"))
      (node (ref "D101") (pin "2") (pinfunction "2_~{}_2") (pintype "bidirectional"))
      (node (ref "R101") (pin "2") (pinfunction "2_2") (pintype "passive"))
      (node (ref "X101") (pin "1") (pinfunction "P$1_1") (pintype "bidirectional"))
      (node (ref "X101") (pin "1-1") (pinfunction "P$1_1-1") (pintype "bidirectional"))
      (node (ref "X200") (pin "1") (pinfunction "1_1") (pintype "passive"))
      (node (ref "X200") (pin "1-2") (pinfunction "1_1-2") (pintype "passive"))
      (node (ref "X201") (pin "1") (pinfunction "1_1") (pintype "passive"))
      (node (ref "X201") (pin "1-2") (pinfunction "1_1-2") (pintype "passive"))
    )
    (net (code "52") (name "MAINS_N") (class "Default")
      (node (ref "C102") (pin "1") (pinfunction "1_1") (pintype "passive"))
      (node (ref "C108") (pin "2") (pinfunction "2_2") (pintype "passive"))
      (node (ref "D101") (pin "4") (pinfunction "1_~{}_4") (pintype "bidirectional"))
      (node (ref "R103") (pin "1") (pinfunction "1_1") (pintype "passive"))
      (node (ref "R114") (pin "2") (pinfunction "2_2") (pintype "passive"))
      (node (ref "V100") (pin "1") (pinfunction "1_1") (pintype "passive"))
      (node (ref "X202") (pin "1") (pinfunction "1_1") (pintype "passive"))
      (node (ref "X202") (pin "1-2") (pinfunction "1_1-2") (pintype "passive"))
      (node (ref "X203") (pin "1") (pinfunction "1_1") (pintype "passive"))
      (node (ref "X203") (pin "1-2") (pinfunction "1_1-2") (pintype "passive"))
      (node (ref "X3") (pin "1") (pinfunction "1_1") (pintype "passive"))
      (node (ref "X3") (pin "1-2") (pinfunction "1_1-2") (pintype "passive"))
    )
    (net (code "53") (name "NDO_G_DRV_RST") (class "Default")
      (node (ref "C372") (pin "2") (pinfunction "2_2") (pintype "passive"))
      (node (ref "C375") (pin "2") (pinfunction "2_2") (pintype "passive"))
      (node (ref "C378") (pin "2") (pinfunction "2_2") (pintype "passive"))
      (node (ref "C381") (pin "2") (pinfunction "2_2") (pintype "passive"))
      (node (ref "C401") (pin "2") (pinfunction "2_2") (pintype "passive"))
      (node (ref "IC306") (pin "14") (pinfunction "/RST_-_EN_14") (pintype "passive"))
      (node (ref "IC307") (pin "14") (pinfunction "/RST_-_EN_14") (pintype "passive"))
      (node (ref "IC310") (pin "14") (pinfunction "/RST_-_EN_14") (pintype "passive"))
      (node (ref "IC311") (pin "14") (pinfunction "/RST_-_EN_14") (pintype "passive"))
      (node (ref "IC400") (pin "93") (pinfunction "P605_93") (pintype "bidirectional"))
      (node (ref "R390") (pin "2") (pinfunction "2_2") (pintype "passive"))
      (node (ref "R409") (pin "2") (pinfunction "2_2") (pintype "passive"))
      (node (ref "R415") (pin "2") (pinfunction "2_2") (pintype "passive"))
      (node (ref "R421") (pin "2") (pinfunction "2_2") (pintype "passive"))
      (node (ref "R447") (pin "1") (pinfunction "1_1") (pintype "passive"))
      (node (ref "X400") (pin "1") (pinfunction "1_1") (pintype "bidirectional"))
    )
    (net (code "54") (name "NDO_PSFB_CTRL_ON") (class "Default")
      (node (ref "R452") (pin "2") (pinfunction "2_2") (pintype "passive"))
    )
    (net (code "55") (name "NODE-A") (class "Default")
      (node (ref "C303") (pin "1") (pinfunction "1_1") (pintype "passive"))
      (node (ref "C304") (pin "1") (pinfunction "1_1") (pintype "passive"))
      (node (ref "D300") (pin "K") (pinfunction "C_K") (pintype "passive"))
      (node (ref "D304") (pin "K") (pinfunction "C_K") (pintype "passive"))
      (node (ref "R326") (pin "2") (pinfunction "2_2") (pintype "passive"))
      (node (ref "T300") (pin "2") (pinfunction "D_2") (pintype "passive"))
      (node (ref "T301") (pin "2") (pinfunction "D_2") (pintype "passive"))
      (node (ref "U301") (pin "1") (pinfunction "P$1_1") (pintype "bidirectional"))
    )
    (net (code "56") (name "NODE_A") (class "Default")
      (node (ref "C300") (pin "1") (pinfunction "1_1") (pintype "passive"))
      (node (ref "C307") (pin "1") (pinfunction "1_1") (pintype "passive"))
      (node (ref "C330") (pin "2") (pinfunction "2_2") (pintype "passive"))
      (node (ref "C331") (pin "2") (pinfunction "2_2") (pintype "passive"))
      (node (ref "C339") (pin "1") (pinfunction "1_1") (pintype "passive"))
      (node (ref "C340") (pin "1") (pinfunction "1_1") (pintype "passive"))
      (node (ref "C342") (pin "1") (pinfunction "1_1") (pintype "passive"))
      (node (ref "C354") (pin "2") (pinfunction "2_2") (pintype "passive"))
      (node (ref "C358") (pin "2") (pinfunction "2_2") (pintype "passive"))
      (node (ref "C388") (pin "1") (pinfunction "1_1") (pintype "passive"))
      (node (ref "C389") (pin "1") (pinfunction "1_1") (pintype "passive"))
      (node (ref "C390") (pin "1") (pinfunction "1_1") (pintype "passive"))
      (node (ref "C391") (pin "1") (pinfunction "1_1") (pintype "passive"))
      (node (ref "C409") (pin "1") (pinfunction "1_1") (pintype "passive"))
      (node (ref "C411") (pin "1") (pinfunction "1_1") (pintype "passive"))
      (node (ref "C413") (pin "2") (pinfunction "2_2") (pintype "passive"))
      (node (ref "C423") (pin "1") (pinfunction "1_1") (pintype "passive"))
      (node (ref "C427") (pin "2") (pinfunction "2_2") (pintype "passive"))
      (node (ref "C430") (pin "1") (pinfunction "1_1") (pintype "passive"))
      (node (ref "C431") (pin "1") (pinfunction "1_1") (pintype "passive"))
      (node (ref "C432") (pin "1") (pinfunction "1_1") (pintype "passive"))
      (node (ref "C437") (pin "1") (pinfunction "1_1") (pintype "passive"))
      (node (ref "C438") (pin "1") (pinfunction "1_1") (pintype "passive"))
      (node (ref "D301") (pin "K") (pinfunction "C_K") (pintype "passive"))
      (node (ref "D315") (pin "A") (pinfunction "A_A") (pintype "passive"))
      (node (ref "IC306") (pin "3") (pinfunction "COM_3") (pintype "passive"))
      (node (ref "IC308") (pin "3") (pinfunction "SHDN_3") (pintype "bidirectional"))
      (node (ref "IC308") (pin "5") (pinfunction "GND_5") (pintype "bidirectional"))
      (node (ref "L303") (pin "1") (pinfunction "P$1_1") (pintype "bidirectional"))
      (node (ref "R309") (pin "1") (pinfunction "1_1") (pintype "passive"))
      (node (ref "R310") (pin "1") (pinfunction "1_1") (pintype "passive"))
      (node (ref "R326") (pin "1") (pinfunction "1_1") (pintype "passive"))
      (node (ref "R398") (pin "2") (pinfunction "2_2") (pintype "passive"))
      (node (ref "R405") (pin "2") (pinfunction "2_2") (pintype "passive"))
      (node (ref "R432") (pin "2") (pinfunction "2_2") (pintype "passive"))
      (node (ref "T301") (pin "3") (pinfunction "S_3") (pintype "passive"))
      (node (ref "T304") (pin "2") (pinfunction "D_2") (pintype "passive"))
    )
    (net (code "57") (name "NODE_C") (class "Default")
      (node (ref "C308") (pin "1") (pinfunction "1_1") (pintype "passive"))
      (node (ref "C351") (pin "1") (pinfunction "1_1") (pintype "passive"))
      (node (ref "C355") (pin "1") (pinfunction "1_1") (pintype "passive"))
      (node (ref "C356") (pin "1") (pinfunction "1_1") (pintype "passive"))
      (node (ref "C357") (pin "2") (pinfunction "2_2") (pintype "passive"))
      (node (ref "C359") (pin "2") (pinfunction "2_2") (pintype "passive"))
      (node (ref "C362") (pin "1") (pinfunction "1_1") (pintype "passive"))
      (node (ref "C384") (pin "1") (pinfunction "1_1") (pintype "passive"))
      (node (ref "C385") (pin "1") (pinfunction "1_1") (pintype "passive"))
      (node (ref "C386") (pin "2") (pinfunction "2_2") (pintype "passive"))
      (node (ref "C395") (pin "1") (pinfunction "1_1") (pintype "passive"))
      (node (ref "C396") (pin "1") (pinfunction "1_1") (pintype "passive"))
      (node (ref "C397") (pin "1") (pinfunction "1_1") (pintype "passive"))
      (node (ref "C398") (pin "1") (pinfunction "1_1") (pintype "passive"))
      (node (ref "C399") (pin "1") (pinfunction "1_1") (pintype "passive"))
      (node (ref "C410") (pin "1") (pinfunction "1_1") (pintype "passive"))
      (node (ref "C412") (pin "1") (pinfunction "1_1") (pintype "passive"))
      (node (ref "C414") (pin "2") (pinfunction "2_2") (pintype "passive"))
      (node (ref "C425") (pin "1") (pinfunction "1_1") (pintype "passive"))
      (node (ref "C428") (pin "2") (pinfunction "2_2") (pintype "passive"))
      (node (ref "C429") (pin "2") (pinfunction "2_2") (pintype "passive"))
      (node (ref "C434") (pin "1") (pinfunction "1_1") (pintype "passive"))
      (node (ref "C435") (pin "1") (pinfunction "1_1") (pintype "passive"))
      (node (ref "C436") (pin "1") (pinfunction "1_1") (pintype "passive"))
      (node (ref "D305") (pin "K") (pinfunction "C_K") (pintype "passive"))
      (node (ref "D319") (pin "A") (pinfunction "A_A") (pintype "passive"))
      (node (ref "IC309") (pin "3") (pinfunction "SHDN_3") (pintype "bidirectional"))
      (node (ref "IC309") (pin "5") (pinfunction "GND_5") (pintype "bidirectional"))
      (node (ref "IC310") (pin "3") (pinfunction "COM_3") (pintype "passive"))
      (node (ref "L307") (pin "1") (pinfunction "P$1_1") (pintype "bidirectional"))
      (node (ref "R311") (pin "1") (pinfunction "1_1") (pintype "passive"))
      (node (ref "R312") (pin "1") (pinfunction "1_1") (pintype "passive"))
      (node (ref "R417") (pin "2") (pinfunction "2_2") (pintype "passive"))
      (node (ref "R433") (pin "2") (pinfunction "2_2") (pintype "passive"))
      (node (ref "T300") (pin "3") (pinfunction "S_3") (pintype "passive"))
      (node (ref "T303") (pin "2") (pinfunction "D_2") (pintype "passive"))
      (node (ref "TR305") (pin "6") (pinfunction "6_6") (pintype "bidirectional"))
    )
    (net (code "58") (name "NRST") (class "Default")
      (node (ref "C450") (pin "1") (pinfunction "1_1") (pintype "passive"))
      (node (ref "IC400") (pin "55") (pinfunction "RES_55") (pintype "passive"))
      (node (ref "R449") (pin "2") (pinfunction "2_2") (pintype "passive"))
      (node (ref "X403") (pin "9") (pinfunction "9_9") (pintype "bidirectional"))
    )
    (net (code "59") (name "Net-(C100--)") (class "Default")
      (node (ref "C100") (pin "2") (pinfunction "-_2") (pintype "passive"))
      (node (ref "C101") (pin "2") (pinfunction "-_2") (pintype "passive"))
      (node (ref "C103") (pin "1") (pinfunction "+_1") (pintype "passive"))
      (node (ref "C104") (pin "1") (pinfunction "+_1") (pintype "passive"))
      (node (ref "C105") (pin "2") (pinfunction "-_2") (pintype "passive"))
      (node (ref "C106") (pin "1") (pinfunction "+_1") (pintype "passive"))
      (node (ref "R102") (pin "1") (pinfunction "1_1") (pintype "passive"))
      (node (ref "R104") (pin "2") (pinfunction "2_2") (pintype "passive"))
    )
    (net (code "60") (name "Net-(C302-Pad1)") (class "Default")
      (node (ref "C302") (pin "1") (pinfunction "1_1") (pintype "passive"))
      (node (ref "R300") (pin "2") (pinfunction "2_2") (pintype "passive"))
    )
    (net (code "61") (name "Net-(C303-Pad2)") (class "Default")
      (node (ref "C303") (pin "2") (pinfunction "2_2") (pintype "passive"))
      (node (ref "R301") (pin "2") (pinfunction "2_2") (pintype "passive"))
    )
    (net (code "62") (name "Net-(C304-Pad2)") (class "Default")
      (node (ref "C304") (pin "2") (pinfunction "2_2") (pintype "passive"))
      (node (ref "R302") (pin "2") (pinfunction "2_2") (pintype "passive"))
    )
    (net (code "63") (name "Net-(C305-Pad1)") (class "Default")
      (node (ref "C305") (pin "1") (pinfunction "1_1") (pintype "passive"))
      (node (ref "R314") (pin "2") (pinfunction "2_2") (pintype "passive"))
    )
    (net (code "64") (name "Net-(C307-Pad2)") (class "Default")
      (node (ref "C307") (pin "2") (pinfunction "2_2") (pintype "passive"))
      (node (ref "R322") (pin "2") (pinfunction "2_2") (pintype "passive"))
    )
    (net (code "65") (name "Net-(C308-Pad2)") (class "Default")
      (node (ref "C308") (pin "2") (pinfunction "2_2") (pintype "passive"))
      (node (ref "R323") (pin "2") (pinfunction "2_2") (pintype "passive"))
    )
    (net (code "66") (name "Net-(C310-Pad1)") (class "Default")
      (node (ref "C310") (pin "1") (pinfunction "1_1") (pintype "passive"))
      (node (ref "R317") (pin "2") (pinfunction "2_2") (pintype "passive"))
      (node (ref "R318") (pin "1") (pinfunction "1_1") (pintype "passive"))
    )
    (net (code "67") (name "Net-(C312-Pad1)") (class "Default")
      (node (ref "C312") (pin "1") (pinfunction "1_1") (pintype "passive"))
      (node (ref "R333") (pin "2") (pinfunction "2_2") (pintype "passive"))
    )
    (net (code "68") (name "Net-(C313-Pad1)") (class "Default")
      (node (ref "C313") (pin "1") (pinfunction "1_1") (pintype "passive"))
      (node (ref "C314") (pin "1") (pinfunction "1_1") (pintype "passive"))
      (node (ref "C316") (pin "2") (pinfunction "2_2") (pintype "passive"))
    )
    (net (code "69") (name "Net-(C313-Pad2)") (class "Default")
      (node (ref "C313") (pin "2") (pinfunction "2_2") (pintype "passive"))
      (node (ref "R335") (pin "2") (pinfunction "2_2") (pintype "passive"))
      (node (ref "R337") (pin "1") (pinfunction "1_1") (pintype "passive"))
    )
    (net (code "70") (name "Net-(C315-Pad1)") (class "Default")
      (node (ref "C315") (pin "1") (pinfunction "1_1") (pintype "passive"))
      (node (ref "R342") (pin "2") (pinfunction "2_2") (pintype "passive"))
    )
    (net (code "71") (name "Net-(C316-Pad1)") (class "Default")
      (node (ref "C316") (pin "1") (pinfunction "1_1") (pintype "passive"))
      (node (ref "R341") (pin "1") (pinfunction "1_1") (pintype "passive"))
      (node (ref "R344") (pin "2") (pinfunction "2_2") (pintype "passive"))
    )
    (net (code "72") (name "Net-(C318-Pad1)") (class "Default")
      (node (ref "C318") (pin "1") (pinfunction "1_1") (pintype "passive"))
      (node (ref "R346") (pin "2") (pinfunction "2_2") (pintype "passive"))
      (node (ref "R347") (pin "1") (pinfunction "1_1") (pintype "passive"))
    )
    (net (code "73") (name "Net-(C387-Pad1)") (class "Default")
      (node (ref "C387") (pin "1") (pinfunction "1_1") (pintype "passive"))
      (node (ref "D313") (pin "A") (pinfunction "A_A") (pintype "passive"))
      (node (ref "R372") (pin "1") (pinfunction "1_1") (pintype "passive"))
      (node (ref "R424") (pin "1") (pinfunction "1_1") (pintype "passive"))
    )
    (net (code "74") (name "Net-(C415-Pad2)") (class "Default")
      (node (ref "C415") (pin "2") (pinfunction "2_2") (pintype "passive"))
      (node (ref "C418") (pin "1") (pinfunction "1_1") (pintype "passive"))
    )
    (net (code "75") (name "Net-(C416-Pad1)") (class "Default")
      (node (ref "C416") (pin "1") (pinfunction "1_1") (pintype "passive"))
      (node (ref "R307") (pin "1") (pinfunction "1_1") (pintype "passive"))
      (node (ref "R434") (pin "2") (pinfunction "2_2") (pintype "passive"))
    )
    (net (code "76") (name "Net-(C417-Pad1)") (class "Default")
      (node (ref "C417") (pin "1") (pinfunction "1_1") (pintype "passive"))
      (node (ref "R434") (pin "1") (pinfunction "1_1") (pintype "passive"))
      (node (ref "R435") (pin "1") (pinfunction "1_1") (pintype "passive"))
      (node (ref "R437") (pin "1") (pinfunction "1_1") (pintype "passive"))
    )
    (net (code "77") (name "Net-(C419-Pad1)") (class "Default")
      (node (ref "C419") (pin "1") (pinfunction "1_1") (pintype "passive"))
      (node (ref "R439") (pin "1") (pinfunction "1_1") (pintype "passive"))
    )
    (net (code "78") (name "Net-(C420-Pad1)") (class "Default")
      (node (ref "C420") (pin "1") (pinfunction "1_1") (pintype "passive"))
      (node (ref "R442") (pin "2") (pinfunction "2_2") (pintype "passive"))
    )
    (net (code "79") (name "Net-(C421-Pad2)") (class "Default")
      (node (ref "C421") (pin "2") (pinfunction "2_2") (pintype "passive"))
      (node (ref "R338") (pin "1") (pinfunction "1_1") (pintype "passive"))
      (node (ref "R339") (pin "2") (pinfunction "2_2") (pintype "passive"))
      (node (ref "R342") (pin "1") (pinfunction "1_1") (pintype "passive"))
      (node (ref "R343") (pin "1") (pinfunction "1_1") (pintype "passive"))
    )
    (net (code "80") (name "Net-(C423-Pad2)") (class "Default")
      (node (ref "C423") (pin "2") (pinfunction "2_2") (pintype "passive"))
      (node (ref "R397") (pin "2") (pinfunction "2_2") (pintype "passive"))
      (node (ref "R404") (pin "2") (pinfunction "2_2") (pintype "passive"))
      (node (ref "R425") (pin "1") (pinfunction "1_1") (pintype "passive"))
    )
    (net (code "81") (name "Net-(C424-Pad2)") (class "Default")
      (node (ref "C424") (pin "2") (pinfunction "2_2") (pintype "passive"))
      (node (ref "R406") (pin "2") (pinfunction "2_2") (pintype "passive"))
      (node (ref "R410") (pin "2") (pinfunction "2_2") (pintype "passive"))
      (node (ref "R426") (pin "1") (pinfunction "1_1") (pintype "passive"))
    )
    (net (code "82") (name "Net-(C425-Pad2)") (class "Default")
      (node (ref "C425") (pin "2") (pinfunction "2_2") (pintype "passive"))
      (node (ref "R412") (pin "1") (pinfunction "1_1") (pintype "passive"))
      (node (ref "R416") (pin "2") (pinfunction "2_2") (pintype "passive"))
      (node (ref "R428") (pin "2") (pinfunction "2_2") (pintype "passive"))
    )
    (net (code "83") (name "Net-(C426-Pad2)") (class "Default")
      (node (ref "C426") (pin "2") (pinfunction "2_2") (pintype "passive"))
      (node (ref "R418") (pin "2") (pinfunction "2_2") (pintype "passive"))
      (node (ref "R422") (pin "2") (pinfunction "2_2") (pintype "passive"))
      (node (ref "R429") (pin "1") (pinfunction "1_1") (pintype "passive"))
    )
    (net (code "84") (name "Net-(C437-Pad2)") (class "Default")
      (node (ref "C437") (pin "2") (pinfunction "2_2") (pintype "passive"))
      (node (ref "C438") (pin "2") (pinfunction "2_2") (pintype "passive"))
      (node (ref "TR305") (pin "1") (pinfunction "1_1") (pintype "bidirectional"))
    )
    (net (code "85") (name "Net-(C505-Pad2)") (class "Default")
      (node (ref "C505") (pin "2") (pinfunction "2_2") (pintype "passive"))
      (node (ref "R521") (pin "2") (pinfunction "2_2") (pintype "passive"))
      (node (ref "R523") (pin "2") (pinfunction "2_2") (pintype "passive"))
    )
    (net (code "86") (name "Net-(D101-+)") (class "Default")
      (node (ref "D101") (pin "1") (pinfunction "+_1") (pintype "bidirectional"))
      (node (ref "K100") (pin "4") (pinfunction "COM_4") (pintype "passive"))
      (node (ref "K101") (pin "4") (pinfunction "COM_4") (pintype "passive"))
      (node (ref "R100") (pin "1") (pinfunction "1_1") (pintype "passive"))
      (node (ref "R112") (pin "1") (pinfunction "1_1") (pintype "passive"))
    )
    (net (code "87") (name "Net-(D102-C)") (class "Default")
      (node (ref "D100") (pin "C") (pinfunction "C_C") (pintype "passive"))
      (node (ref "D102") (pin "K") (pinfunction "C_K") (pintype "passive"))
    )
    (net (code "88") (name "Net-(D102-PadA)") (class "Default")
      (node (ref "D102") (pin "A") (pinfunction "A_A") (pintype "passive"))
      (node (ref "R105") (pin "2") (pinfunction "2_2") (pintype "passive"))
    )
    (net (code "89") (name "Net-(D104-C)") (class "Default")
      (node (ref "D104") (pin "K") (pinfunction "C_K") (pintype "passive"))
      (node (ref "R105") (pin "1") (pinfunction "1_1") (pintype "passive"))
      (node (ref "R107") (pin "2") (pinfunction "2_2") (pintype "passive"))
    )
    (net (code "90") (name "Net-(D105-C)") (class "Default")
      (node (ref "D105") (pin "K") (pinfunction "C_K") (pintype "passive"))
      (node (ref "Q101") (pin "3") (pinfunction "B_3") (pintype "passive"))
      (node (ref "R111") (pin "2") (pinfunction "2_2") (pintype "passive"))
    )
    (net (code "91") (name "Net-(D200-C)") (class "Default")
      (node (ref "D200") (pin "2") (pinfunction "C_2") (pintype "passive"))
      (node (ref "R200") (pin "2") (pinfunction "2_2") (pintype "passive"))
    )
    (net (code "92") (name "Net-(D201-C)") (class "Default")
      (node (ref "D201") (pin "2") (pinfunction "C_2") (pintype "passive"))
      (node (ref "R201") (pin "2") (pinfunction "2_2") (pintype "passive"))
    )
    (net (code "93") (name "Net-(D300-PadA)") (class "Default")
      (node (ref "D300") (pin "A") (pinfunction "A_A") (pintype "passive"))
      (node (ref "R404") (pin "1") (pinfunction "1_1") (pintype "passive"))
    )
    (net (code "94") (name "Net-(D301-PadA)") (class "Default")
      (node (ref "D301") (pin "A") (pinfunction "A_A") (pintype "passive"))
      (node (ref "R410") (pin "1") (pinfunction "1_1") (pintype "passive"))
    )
    (net (code "95") (name "Net-(D302-C)") (class "Default")
      (node (ref "C301") (pin "2") (pinfunction "2_2") (pintype "passive"))
      (node (ref "C302") (pin "2") (pinfunction "2_2") (pintype "passive"))
      (node (ref "D302") (pin "1") (pinfunction "C_1") (pintype "passive"))
      (node (ref "IC300") (pin "1") (pinfunction "OUT_1") (pintype "passive"))
      (node (ref "R305") (pin "1") (pinfunction "1_1") (pintype "passive"))
    )
    (net (code "96") (name "Net-(D303-C)") (class "Default")
      (node (ref "D303") (pin "K") (pinfunction "C_K") (pintype "passive"))
      (node (ref "R315") (pin "1") (pinfunction "1_1") (pintype "passive"))
      (node (ref "R316") (pin "2") (pinfunction "2_2") (pintype "passive"))
    )
    (net (code "97") (name "Net-(D303-PadA)") (class "Default")
      (node (ref "D303") (pin "A") (pinfunction "A_A") (pintype "passive"))
      (node (ref "TR300") (pin "2") (pinfunction "2_2") (pintype "bidirectional"))
    )
    (net (code "98") (name "Net-(D304-PadA)") (class "Default")
      (node (ref "D304") (pin "A") (pinfunction "A_A") (pintype "passive"))
      (node (ref "R416") (pin "1") (pinfunction "1_1") (pintype "passive"))
    )
    (net (code "99") (name "Net-(D305-PadA)") (class "Default")
      (node (ref "D305") (pin "A") (pinfunction "A_A") (pintype "passive"))
      (node (ref "R422") (pin "1") (pinfunction "1_1") (pintype "passive"))
    )
    (net (code "100") (name "Net-(D306-C)") (class "Default")
      (node (ref "C311") (pin "2") (pinfunction "2_2") (pintype "passive"))
      (node (ref "C312") (pin "2") (pinfunction "2_2") (pintype "passive"))
      (node (ref "D306") (pin "1") (pinfunction "C_1") (pintype "passive"))
      (node (ref "IC302") (pin "1") (pinfunction "OUT_1") (pintype "passive"))
      (node (ref "R336") (pin "1") (pinfunction "1_1") (pintype "passive"))
    )
    (net (code "101") (name "Net-(D307-Pad1)") (class "Default")
      (node (ref "D307") (pin "1") (pinfunction "1_1") (pintype "passive"))
      (node (ref "D307") (pin "3") (pinfunction "3_3") (pintype "passive"))
      (node (ref "D308") (pin "1") (pinfunction "1_1") (pintype "passive"))
      (node (ref "D308") (pin "3") (pinfunction "3_3") (pintype "passive"))
      (node (ref "D309") (pin "1") (pinfunction "1_1") (pintype "passive"))
      (node (ref "D309") (pin "3") (pinfunction "3_3") (pintype "passive"))
      (node (ref "R440") (pin "2") (pinfunction "2_2") (pintype "passive"))
      (node (ref "TR305") (pin "5") (pinfunction "5_5") (pintype "bidirectional"))
    )
    (net (code "102") (name "Net-(D310-Pad1)") (class "Default")
      (node (ref "D310") (pin "1") (pinfunction "1_1") (pintype "passive"))
      (node (ref "D310") (pin "3") (pinfunction "3_3") (pintype "passive"))
      (node (ref "D311") (pin "1") (pinfunction "1_1") (pintype "passive"))
      (node (ref "D311") (pin "3") (pinfunction "3_3") (pintype "passive"))
      (node (ref "D312") (pin "1") (pinfunction "1_1") (pintype "passive"))
      (node (ref "D312") (pin "3") (pinfunction "3_3") (pintype "passive"))
      (node (ref "R441") (pin "1") (pinfunction "1_1") (pintype "passive"))
      (node (ref "TR305") (pin "3") (pinfunction "3_3") (pintype "bidirectional"))
    )
    (net (code "103") (name "Net-(D314-PadA)") (class "Default")
      (node (ref "D314") (pin "A") (pinfunction "A_A") (pintype "passive"))
      (node (ref "R401") (pin "1") (pinfunction "1_1") (pintype "passive"))
      (node (ref "R427") (pin "1") (pinfunction "1_1") (pintype "passive"))
    )
    (net (code "104") (name "Net-(D316-C)") (class "Default")
      (node (ref "D316") (pin "1") (pinfunction "C_1") (pintype "passive"))
      (node (ref "IC308") (pin "8") (pinfunction "LX_8") (pintype "bidirectional"))
      (node (ref "L303") (pin "2") (pinfunction "P$2_2") (pintype "bidirectional"))
    )
    (net (code "105") (name "Net-(D318-C)") (class "Default")
      (node (ref "D318") (pin "1") (pinfunction "C_1") (pintype "passive"))
      (node (ref "IC309") (pin "8") (pinfunction "LX_8") (pintype "bidirectional"))
      (node (ref "L307") (pin "2") (pinfunction "P$2_2") (pintype "bidirectional"))
    )
    (net (code "106") (name "Net-(D323-C)") (class "Default")
      (node (ref "D323") (pin "K") (pinfunction "C_K") (pintype "passive"))
      (node (ref "R436") (pin "1") (pinfunction "1_1") (pintype "passive"))
    )
    (net (code "107") (name "Net-(IC1-ADEL)") (class "Default")
      (node (ref "IC1") (pin "14") (pinfunction "ADEL_14") (pintype "bidirectional"))
      (node (ref "R363") (pin "2") (pinfunction "2_2") (pintype "passive"))
      (node (ref "R376") (pin "1") (pinfunction "1_1") (pintype "passive"))
    )
    (net (code "108") (name "Net-(IC1-ADELEF)") (class "Default")
      (node (ref "IC1") (pin "13") (pinfunction "ADELEF_13") (pintype "bidirectional"))
      (node (ref "R366") (pin "2") (pinfunction "2_2") (pintype "passive"))
      (node (ref "R375") (pin "1") (pinfunction "1_1") (pintype "passive"))
    )
    (net (code "109") (name "Net-(IC1-COMP)") (class "Default")
      (node (ref "IC1") (pin "4") (pinfunction "COMP_4") (pintype "bidirectional"))
      (node (ref "R354") (pin "1") (pinfunction "1_1") (pintype "passive"))
    )
    (net (code "110") (name "Net-(IC1-DCM)") (class "Default")
      (node (ref "IC1") (pin "12") (pinfunction "DCM_12") (pintype "bidirectional"))
      (node (ref "R374") (pin "2") (pinfunction "2_2") (pintype "passive"))
      (node (ref "R379") (pin "2") (pinfunction "2_2") (pintype "passive"))
    )
    (net (code "111") (name "Net-(IC1-DELAB)") (class "Default")
      (node (ref "IC1") (pin "6") (pinfunction "DELAB_6") (pintype "bidirectional"))
      (node (ref "R357") (pin "1") (pinfunction "1_1") (pintype "passive"))
    )
    (net (code "112") (name "Net-(IC1-DELCD)") (class "Default")
      (node (ref "IC1") (pin "7") (pinfunction "DELCD_7") (pintype "bidirectional"))
      (node (ref "R359") (pin "1") (pinfunction "1_1") (pintype "passive"))
    )
    (net (code "113") (name "Net-(IC1-DELEF)") (class "Default")
      (node (ref "IC1") (pin "8") (pinfunction "DELEF_8") (pintype "bidirectional"))
      (node (ref "R360") (pin "1") (pinfunction "1_1") (pintype "passive"))
    )
    (net (code "114") (name "Net-(IC1-EA+)") (class "Default")
      (node (ref "IC1") (pin "2") (pinfunction "EA+_2") (pintype "bidirectional"))
      (node (ref "R352") (pin "2") (pinfunction "2_2") (pintype "passive"))
    )
    (net (code "115") (name "Net-(IC1-EA-)") (class "Default")
      (node (ref "IC1") (pin "3") (pinfunction "EA-_3") (pintype "bidirectional"))
      (node (ref "R354") (pin "2") (pinfunction "2_2") (pintype "passive"))
    )
    (net (code "116") (name "Net-(IC1-RSUM)") (class "Default")
      (node (ref "IC1") (pin "11") (pinfunction "RSUM_11") (pintype "bidirectional"))
      (node (ref "R369") (pin "1") (pinfunction "1_1") (pintype "passive"))
      (node (ref "R371") (pin "1") (pinfunction "1_1") (pintype "passive"))
    )
    (net (code "117") (name "Net-(IC1-RT)") (class "Default")
      (node (ref "IC1") (pin "10") (pinfunction "RT_10") (pintype "bidirectional"))
      (node (ref "R365") (pin "1") (pinfunction "1_1") (pintype "passive"))
      (node (ref "R368") (pin "1") (pinfunction "1_1") (pintype "passive"))
    )
    (net (code "118") (name "Net-(IC1-SYNC)") (class "Default")
      (node (ref "IC1") (pin "16") (pinfunction "SYNC_16") (pintype "bidirectional"))
      (node (ref "R386") (pin "1") (pinfunction "1_1") (pintype "passive"))
    )
    (net (code "119") (name "Net-(IC1-TMIN)") (class "Default")
      (node (ref "IC1") (pin "9") (pinfunction "TMIN_9") (pintype "bidirectional"))
      (node (ref "R362") (pin "1") (pinfunction "1_1") (pintype "passive"))
    )
    (net (code "120") (name "Net-(IC1-VDD)") (class "Default")
      (node (ref "C320") (pin "2") (pinfunction "2_2") (pintype "passive"))
      (node (ref "C422") (pin "1") (pinfunction "1_1") (pintype "passive"))
      (node (ref "IC1") (pin "23") (pinfunction "VDD_23") (pintype "bidirectional"))
      (node (ref "L300") (pin "1") (pinfunction "P$1_1") (pintype "bidirectional"))
    )
    (net (code "121") (name "Net-(IC100-ANODE)") (class "Default")
      (node (ref "IC100") (pin "1") (pinfunction "ANODE_1") (pintype "passive"))
      (node (ref "R107") (pin "1") (pinfunction "1_1") (pintype "passive"))
      (node (ref "R110") (pin "2") (pinfunction "2_2") (pintype "passive"))
    )
    (net (code "122") (name "Net-(IC100-COLLECTOR)") (class "Default")
      (node (ref "IC100") (pin "4") (pinfunction "COLLECTOR_4") (pintype "passive"))
      (node (ref "R106") (pin "2") (pinfunction "2_2") (pintype "passive"))
      (node (ref "R109") (pin "2") (pinfunction "2_2") (pintype "passive"))
    )
    (net (code "123") (name "Net-(IC300-IN+)") (class "Default")
      (node (ref "C309") (pin "1") (pinfunction "1_1") (pintype "passive"))
      (node (ref "IC300") (pin "3") (pinfunction "IN+_3") (pintype "passive"))
      (node (ref "R317") (pin "1") (pinfunction "1_1") (pintype "passive"))
      (node (ref "R321") (pin "2") (pinfunction "2_2") (pintype "passive"))
    )
    (net (code "124") (name "Net-(IC300-IN-)") (class "Default")
      (node (ref "C301") (pin "1") (pinfunction "1_1") (pintype "passive"))
      (node (ref "C305") (pin "2") (pinfunction "2_2") (pintype "passive"))
      (node (ref "IC300") (pin "4") (pinfunction "IN-_4") (pintype "passive"))
      (node (ref "R300") (pin "1") (pinfunction "1_1") (pintype "passive"))
      (node (ref "R306") (pin "2") (pinfunction "2_2") (pintype "passive"))
    )
    (net (code "125") (name "Net-(IC301-IN+)") (class "Default")
      (node (ref "C383") (pin "2") (pinfunction "2_2") (pintype "passive"))
      (node (ref "IC301") (pin "3") (pinfunction "IN+_3") (pintype "passive"))
      (node (ref "R334") (pin "1") (pinfunction "1_1") (pintype "passive"))
      (node (ref "R337") (pin "2") (pinfunction "2_2") (pintype "passive"))
    )
    (net (code "126") (name "Net-(IC301-IN-)") (class "Default")
      (node (ref "C433") (pin "1") (pinfunction "1_1") (pintype "passive"))
      (node (ref "IC301") (pin "4") (pinfunction "IN-_4") (pintype "passive"))
      (node (ref "R341") (pin "2") (pinfunction "2_2") (pintype "passive"))
      (node (ref "R345") (pin "1") (pinfunction "1_1") (pintype "passive"))
    )
    (net (code "127") (name "Net-(IC302-IN+)") (class "Default")
      (node (ref "C317") (pin "1") (pinfunction "1_1") (pintype "passive"))
      (node (ref "IC302") (pin "3") (pinfunction "IN+_3") (pintype "passive"))
      (node (ref "R346") (pin "1") (pinfunction "1_1") (pintype "passive"))
      (node (ref "R350") (pin "2") (pinfunction "2_2") (pintype "passive"))
    )
    (net (code "128") (name "Net-(IC302-IN-)") (class "Default")
      (node (ref "C311") (pin "1") (pinfunction "1_1") (pintype "passive"))
      (node (ref "C315") (pin "2") (pinfunction "2_2") (pintype "passive"))
      (node (ref "IC302") (pin "4") (pinfunction "IN-_4") (pintype "passive"))
      (node (ref "R333") (pin "1") (pinfunction "1_1") (pintype "passive"))
      (node (ref "R338") (pin "2") (pinfunction "2_2") (pintype "passive"))
    )
    (net (code "129") (name "Net-(IC308-FB)") (class "Default")
      (node (ref "IC308") (pin "2") (pinfunction "FB_2") (pintype "bidirectional"))
      (node (ref "R399") (pin "2") (pinfunction "2_2") (pintype "passive"))
      (node (ref "R400") (pin "2") (pinfunction "2_2") (pintype "passive"))
    )
    (net (code "130") (name "Net-(IC308-REF)") (class "Default")
      (node (ref "C354") (pin "1") (pinfunction "1_1") (pintype "passive"))
      (node (ref "IC308") (pin "4") (pinfunction "REF_4") (pintype "bidirectional"))
      (node (ref "R400") (pin "1") (pinfunction "1_1") (pintype "passive"))
    )
    (net (code "131") (name "Net-(IC309-FB)") (class "Default")
      (node (ref "IC309") (pin "2") (pinfunction "FB_2") (pintype "bidirectional"))
      (node (ref "R402") (pin "2") (pinfunction "2_2") (pintype "passive"))
      (node (ref "R403") (pin "2") (pinfunction "2_2") (pintype "passive"))
    )
    (net (code "132") (name "Net-(IC309-REF)") (class "Default")
      (node (ref "C359") (pin "1") (pinfunction "1_1") (pintype "passive"))
      (node (ref "IC309") (pin "4") (pinfunction "REF_4") (pintype "bidirectional"))
      (node (ref "R403") (pin "1") (pinfunction "1_1") (pintype "passive"))
    )
    (net (code "133") (name "Net-(IC312-ADJ)") (class "Default")
      (node (ref "IC312") (pin "1") (pinfunction "ADJ_1") (pintype "input"))
      (node (ref "R430") (pin "1") (pinfunction "1_1") (pintype "passive"))
      (node (ref "R432") (pin "1") (pinfunction "1_1") (pintype "passive"))
    )
    (net (code "134") (name "Net-(IC313-ADJ)") (class "Default")
      (node (ref "IC313") (pin "1") (pinfunction "ADJ_1") (pintype "input"))
      (node (ref "R431") (pin "1") (pinfunction "1_1") (pintype "passive"))
      (node (ref "R433") (pin "1") (pinfunction "1_1") (pintype "passive"))
    )
    (net (code "135") (name "Net-(IC400A-P212{slash}EXTAL)") (class "Default")
      (node (ref "IC400") (pin "20") (pinfunction "P212/EXTAL_20") (pintype "bidirectional"))
      (node (ref "IC401") (pin "3") (pinfunction "OUTPUT_3") (pintype "passive"))
      (node (ref "R450") (pin "2") (pinfunction "2_2") (pintype "passive"))
    )
    (net (code "136") (name "Net-(IC400A-P213{slash}XTAL)") (class "Default")
      (node (ref "IC400") (pin "19") (pinfunction "P213/XTAL_19") (pintype "bidirectional"))
      (node (ref "R450") (pin "1") (pinfunction "1_1") (pintype "passive"))
      (node (ref "R451") (pin "1") (pinfunction "1_1") (pintype "passive"))
    )
    (net (code "137") (name "Net-(IC400A-VCL0)") (class "Default")
      (node (ref "C451") (pin "2") (pinfunction "2_2") (pintype "passive"))
      (node (ref "IC400") (pin "15") (pinfunction "VCL0_15") (pintype "power_in"))
    )
    (net (code "138") (name "Net-(IC400B-VCL)") (class "Default")
      (node (ref "C452") (pin "1") (pinfunction "1_1") (pintype "passive"))
      (node (ref "IC400") (pin "92") (pinfunction "VCL_92") (pintype "power_in"))
    )
    (net (code "139") (name "Net-(IC401-INPUT)") (class "Default")
      (node (ref "IC401") (pin "1") (pinfunction "INPUT_1") (pintype "passive"))
      (node (ref "R451") (pin "2") (pinfunction "2_2") (pintype "passive"))
    )
    (net (code "140") (name "Net-(IC500-D)") (class "Default")
      (node (ref "IC500") (pin "4") (pinfunction "D_4") (pintype "bidirectional"))
      (node (ref "R525") (pin "1") (pinfunction "1_1") (pintype "passive"))
    )
    (net (code "141") (name "Net-(IC500-DE)") (class "Default")
      (node (ref "IC500") (pin "3") (pinfunction "DE_3") (pintype "bidirectional"))
      (node (ref "R522") (pin "1") (pinfunction "1_1") (pintype "passive"))
    )
    (net (code "142") (name "Net-(IC500-R)") (class "Default")
      (node (ref "IC500") (pin "1") (pinfunction "R_1") (pintype "bidirectional"))
      (node (ref "Q506") (pin "2") (pinfunction "E_2") (pintype "passive"))
    )
    (net (code "143") (name "Net-(IC500-{slash}RE)") (class "Default")
      (node (ref "IC500") (pin "2") (pinfunction "/RE_2") (pintype "bidirectional"))
      (node (ref "R520") (pin "1") (pinfunction "1_1") (pintype "passive"))
    )
    (net (code "144") (name "Net-(Q100-B)") (class "Default")
      (node (ref "Q100") (pin "3") (pinfunction "B_3") (pintype "passive"))
      (node (ref "R109") (pin "1") (pinfunction "1_1") (pintype "passive"))
    )
    (net (code "145") (name "Net-(Q100-E)") (class "Default")
      (node (ref "D103") (pin "A") (pinfunction "A_A") (pintype "passive"))
      (node (ref "K100") (pin "1") (pinfunction "1_1") (pintype "passive"))
      (node (ref "K101") (pin "1") (pinfunction "1_1") (pintype "passive"))
      (node (ref "Q100") (pin "1") (pinfunction "E_1") (pintype "passive"))
      (node (ref "R106") (pin "1") (pinfunction "1_1") (pintype "passive"))
    )
    (net (code "146") (name "Net-(Q101-C)") (class "Default")
      (node (ref "Q101") (pin "2") (pinfunction "C_2") (pintype "passive"))
      (node (ref "R108") (pin "2") (pinfunction "2_2") (pintype "passive"))
      (node (ref "R113") (pin "2") (pinfunction "2_2") (pintype "passive"))
    )
    (net (code "147") (name "Net-(Q101-E)") (class "Default")
      (node (ref "D103") (pin "C") (pinfunction "C_C") (pintype "passive"))
      (node (ref "K100") (pin "2") (pinfunction "2_2") (pintype "passive"))
      (node (ref "K101") (pin "2") (pinfunction "2_2") (pintype "passive"))
      (node (ref "Q101") (pin "1") (pinfunction "E_1") (pintype "passive"))
    )
    (net (code "148") (name "Net-(Q306-D)") (class "Default")
      (node (ref "Q306") (pin "3") (pinfunction "D_3") (pintype "passive"))
      (node (ref "R347") (pin "2") (pinfunction "2_2") (pintype "passive"))
      (node (ref "R348") (pin "1") (pinfunction "1_1") (pintype "passive"))
    )
    (net (code "149") (name "Net-(Q306-G)") (class "Default")
      (node (ref "Q306") (pin "1") (pinfunction "G_1") (pintype "passive"))
      (node (ref "R349") (pin "2") (pinfunction "2_2") (pintype "passive"))
      (node (ref "R351") (pin "2") (pinfunction "2_2") (pintype "passive"))
    )
    (net (code "150") (name "Net-(Q500-GATE)") (class "Default")
      (node (ref "Q500") (pin "1") (pinfunction "GATE_1") (pintype "passive"))
      (node (ref "R500") (pin "1") (pinfunction "1_1") (pintype "passive"))
      (node (ref "R501") (pin "2") (pinfunction "2_2") (pintype "passive"))
    )
    (net (code "151") (name "Net-(Q501-B)") (class "Default")
      (node (ref "Q501") (pin "1") (pinfunction "B_1") (pintype "passive"))
      (node (ref "R504") (pin "1") (pinfunction "1_1") (pintype "passive"))
    )
    (net (code "152") (name "Net-(Q501-E)") (class "Default")
      (node (ref "Q501") (pin "2") (pinfunction "E_2") (pintype "passive"))
      (node (ref "R506") (pin "2") (pinfunction "2_2") (pintype "passive"))
    )
    (net (code "153") (name "Net-(Q502-GATE)") (class "Default")
      (node (ref "Q502") (pin "1") (pinfunction "GATE_1") (pintype "passive"))
      (node (ref "R505") (pin "1") (pinfunction "1_1") (pintype "passive"))
      (node (ref "R507") (pin "2") (pinfunction "2_2") (pintype "passive"))
    )
    (net (code "154") (name "Net-(Q503-B)") (class "Default")
      (node (ref "Q503") (pin "1") (pinfunction "B_1") (pintype "passive"))
      (node (ref "R509") (pin "1") (pinfunction "1_1") (pintype "passive"))
    )
    (net (code "155") (name "Net-(Q503-E)") (class "Default")
      (node (ref "Q503") (pin "2") (pinfunction "E_2") (pintype "passive"))
      (node (ref "R511") (pin "2") (pinfunction "2_2") (pintype "passive"))
    )
    (net (code "156") (name "Net-(Q504-GATE)") (class "Default")
      (node (ref "Q504") (pin "1") (pinfunction "GATE_1") (pintype "passive"))
      (node (ref "R512") (pin "1") (pinfunction "1_1") (pintype "passive"))
      (node (ref "R514") (pin "2") (pinfunction "2_2") (pintype "passive"))
    )
    (net (code "157") (name "Net-(Q505-B)") (class "Default")
      (node (ref "Q505") (pin "1") (pinfunction "B_1") (pintype "passive"))
      (node (ref "R513") (pin "1") (pinfunction "1_1") (pintype "passive"))
    )
    (net (code "158") (name "Net-(Q505-E)") (class "Default")
      (node (ref "Q505") (pin "2") (pinfunction "E_2") (pintype "passive"))
      (node (ref "R518") (pin "2") (pinfunction "2_2") (pintype "passive"))
    )
    (net (code "159") (name "Net-(Q506-B)") (class "Default")
      (node (ref "Q506") (pin "1") (pinfunction "B_1") (pintype "passive"))
      (node (ref "R516") (pin "2") (pinfunction "2_2") (pintype "passive"))
    )
    (net (code "160") (name "Net-(Q507-B)") (class "Default")
      (node (ref "Q507") (pin "1") (pinfunction "B_1") (pintype "passive"))
      (node (ref "R524") (pin "1") (pinfunction "1_1") (pintype "passive"))
    )
    (net (code "161") (name "Net-(Q507-E)") (class "Default")
      (node (ref "Q507") (pin "2") (pinfunction "E_2") (pintype "passive"))
      (node (ref "R528") (pin "2") (pinfunction "2_2") (pintype "passive"))
    )
    (net (code "162") (name "Net-(R101-Pad1)") (class "Default")
      (node (ref "R101") (pin "1") (pinfunction "1_1") (pintype "passive"))
      (node (ref "R103") (pin "2") (pinfunction "2_2") (pintype "passive"))
    )
    (net (code "163") (name "Net-(R114-Pad1)") (class "Default")
      (node (ref "R114") (pin "1") (pinfunction "1_1") (pintype "passive"))
      (node (ref "R115") (pin "2") (pinfunction "2_2") (pintype "passive"))
    )
    (net (code "164") (name "Net-(R301-Pad1)") (class "Default")
      (node (ref "R301") (pin "1") (pinfunction "1_1") (pintype "passive"))
      (node (ref "R310") (pin "2") (pinfunction "2_2") (pintype "passive"))
    )
    (net (code "165") (name "Net-(R302-Pad1)") (class "Default")
      (node (ref "R302") (pin "1") (pinfunction "1_1") (pintype "passive"))
      (node (ref "R311") (pin "2") (pinfunction "2_2") (pintype "passive"))
    )
    (net (code "166") (name "Net-(R306-Pad1)") (class "Default")
      (node (ref "R306") (pin "1") (pinfunction "1_1") (pintype "passive"))
      (node (ref "R307") (pin "2") (pinfunction "2_2") (pintype "passive"))
      (node (ref "R314") (pin "1") (pinfunction "1_1") (pintype "passive"))
    )
    (net (code "167") (name "Net-(R322-Pad1)") (class "Default")
      (node (ref "R322") (pin "1") (pinfunction "1_1") (pintype "passive"))
      (node (ref "R329") (pin "2") (pinfunction "2_2") (pintype "passive"))
    )
    (net (code "168") (name "Net-(R323-Pad1)") (class "Default")
      (node (ref "R323") (pin "1") (pinfunction "1_1") (pintype "passive"))
      (node (ref "R330") (pin "2") (pinfunction "2_2") (pintype "passive"))
    )
    (net (code "169") (name "Net-(R435-Pad2)") (class "Default")
      (node (ref "R435") (pin "2") (pinfunction "2_2") (pintype "passive"))
      (node (ref "R436") (pin "2") (pinfunction "2_2") (pintype "passive"))
      (node (ref "R438") (pin "2") (pinfunction "2_2") (pintype "passive"))
    )
    (net (code "170") (name "Net-(R439-Pad2)") (class "Default")
      (node (ref "R439") (pin "2") (pinfunction "2_2") (pintype "passive"))
      (node (ref "R440") (pin "1") (pinfunction "1_1") (pintype "passive"))
    )
    (net (code "171") (name "Net-(R441-Pad2)") (class "Default")
      (node (ref "R441") (pin "2") (pinfunction "2_2") (pintype "passive"))
      (node (ref "R442") (pin "1") (pinfunction "1_1") (pintype "passive"))
    )
    (net (code "172") (name "Net-(T302-D)") (class "Default")
      (node (ref "R318") (pin "2") (pinfunction "2_2") (pintype "passive"))
      (node (ref "R319") (pin "1") (pinfunction "1_1") (pintype "passive"))
      (node (ref "T302") (pin "3") (pinfunction "D_3") (pintype "passive"))
    )
    (net (code "173") (name "Net-(T302-G)") (class "Default")
      (node (ref "R320") (pin "2") (pinfunction "2_2") (pintype "passive"))
      (node (ref "R324") (pin "2") (pinfunction "2_2") (pintype "passive"))
      (node (ref "T302") (pin "1") (pinfunction "G_1") (pintype "passive"))
    )
    (net (code "174") (name "Net-(T307-G)") (class "Default")
      (node (ref "R356") (pin "1") (pinfunction "1_1") (pintype "passive"))
      (node (ref "R358") (pin "2") (pinfunction "2_2") (pintype "passive"))
      (node (ref "T307") (pin "1") (pinfunction "G_1") (pintype "passive"))
    )
    (net (code "175") (name "Net-(T307-S)") (class "Default")
      (node (ref "R353") (pin "2") (pinfunction "2_2") (pintype "passive"))
      (node (ref "R356") (pin "2") (pinfunction "2_2") (pintype "passive"))
      (node (ref "T307") (pin "2") (pinfunction "S_2") (pintype "passive"))
    )
    (net (code "176") (name "Net-(T308-G)") (class "Default")
      (node (ref "R367") (pin "1") (pinfunction "1_1") (pintype "passive"))
      (node (ref "R370") (pin "2") (pinfunction "2_2") (pintype "passive"))
      (node (ref "T308") (pin "1") (pinfunction "G_1") (pintype "passive"))
    )
    (net (code "177") (name "Net-(T308-S)") (class "Default")
      (node (ref "R361") (pin "2") (pinfunction "2_2") (pintype "passive"))
      (node (ref "R367") (pin "2") (pinfunction "2_2") (pintype "passive"))
      (node (ref "T308") (pin "2") (pinfunction "S_2") (pintype "passive"))
    )
    (net (code "178") (name "Net-(T309-G)") (class "Default")
      (node (ref "R378") (pin "1") (pinfunction "1_1") (pintype "passive"))
      (node (ref "R380") (pin "2") (pinfunction "2_2") (pintype "passive"))
      (node (ref "T309") (pin "1") (pinfunction "G_1") (pintype "passive"))
    )
    (net (code "179") (name "Net-(T309-S)") (class "Default")
      (node (ref "R373") (pin "2") (pinfunction "2_2") (pintype "passive"))
      (node (ref "R378") (pin "2") (pinfunction "2_2") (pintype "passive"))
      (node (ref "T309") (pin "2") (pinfunction "S_2") (pintype "passive"))
    )
    (net (code "180") (name "Net-(T310-G)") (class "Default")
      (node (ref "R383") (pin "1") (pinfunction "1_1") (pintype "passive"))
      (node (ref "R384") (pin "2") (pinfunction "2_2") (pintype "passive"))
      (node (ref "T310") (pin "1") (pinfunction "G_1") (pintype "passive"))
    )
    (net (code "181") (name "Net-(T310-S)") (class "Default")
      (node (ref "R381") (pin "2") (pinfunction "2_2") (pintype "passive"))
      (node (ref "R383") (pin "2") (pinfunction "2_2") (pintype "passive"))
      (node (ref "T310") (pin "2") (pinfunction "S_2") (pintype "passive"))
    )
    (net (code "182") (name "Net-(T313-D)") (class "Default")
      (node (ref "R461") (pin "2") (pinfunction "2_2") (pintype "passive"))
      (node (ref "T313") (pin "3") (pinfunction "D_3") (pintype "passive"))
    )
    (net (code "183") (name "Net-(T313-G)") (class "Default")
      (node (ref "R462") (pin "2") (pinfunction "2_2") (pintype "passive"))
      (node (ref "R463") (pin "2") (pinfunction "2_2") (pintype "passive"))
      (node (ref "T313") (pin "1") (pinfunction "G_1") (pintype "passive"))
    )
    (net (code "184") (name "Net-(T500-D)") (class "Default")
      (node (ref "R501") (pin "1") (pinfunction "1_1") (pintype "passive"))
      (node (ref "T500") (pin "3") (pinfunction "D_3") (pintype "passive"))
    )
    (net (code "185") (name "Net-(T500-G)") (class "Default")
      (node (ref "R502") (pin "1") (pinfunction "1_1") (pintype "passive"))
      (node (ref "R503") (pin "2") (pinfunction "2_2") (pintype "passive"))
      (node (ref "T500") (pin "1") (pinfunction "G_1") (pintype "passive"))
    )
    (net (code "186") (name "Net-(T501-D)") (class "Default")
      (node (ref "R507") (pin "1") (pinfunction "1_1") (pintype "passive"))
      (node (ref "T501") (pin "3") (pinfunction "D_3") (pintype "passive"))
    )
    (net (code "187") (name "Net-(T501-G)") (class "Default")
      (node (ref "R508") (pin "1") (pinfunction "1_1") (pintype "passive"))
      (node (ref "R510") (pin "2") (pinfunction "2_2") (pintype "passive"))
      (node (ref "T501") (pin "1") (pinfunction "G_1") (pintype "passive"))
    )
    (net (code "188") (name "Net-(T502-D)") (class "Default")
      (node (ref "R514") (pin "1") (pinfunction "1_1") (pintype "passive"))
      (node (ref "T502") (pin "3") (pinfunction "D_3") (pintype "passive"))
    )
    (net (code "189") (name "Net-(T502-G)") (class "Default")
      (node (ref "R517") (pin "1") (pinfunction "1_1") (pintype "passive"))
      (node (ref "R519") (pin "2") (pinfunction "2_2") (pintype "passive"))
      (node (ref "T502") (pin "1") (pinfunction "G_1") (pintype "passive"))
    )
    (net (code "190") (name "PSFB_EN") (class "Default")
      (node (ref "Q300") (pin "1") (pinfunction "G_1") (pintype "passive"))
      (node (ref "R388") (pin "1") (pinfunction "1_1") (pintype "passive"))
      (node (ref "R391") (pin "2") (pinfunction "2_2") (pintype "passive"))
      (node (ref "R452") (pin "1") (pinfunction "1_1") (pintype "passive"))
      (node (ref "V400") (pin "2") (pinfunction "2_2") (pintype "passive"))
      (node (ref "X401") (pin "4") (pinfunction "4_4") (pintype "bidirectional"))
    )
    (net (code "191") (name "QA_GATE") (class "Default")
      (node (ref "C300") (pin "2") (pinfunction "2_2") (pintype "passive"))
      (node (ref "IC306") (pin "7") (pinfunction "CLAMPI_7") (pintype "passive"))
      (node (ref "R309") (pin "2") (pinfunction "2_2") (pintype "passive"))
      (node (ref "R325") (pin "1") (pinfunction "1_1") (pintype "passive"))
      (node (ref "R327") (pin "1") (pinfunction "1_1") (pintype "passive"))
      (node (ref "T301") (pin "1") (pinfunction "G_1") (pintype "passive"))
    )
    (net (code "192") (name "QA_OC") (class "Default")
      (node (ref "C342") (pin "2") (pinfunction "2_2") (pintype "passive"))
      (node (ref "D315") (pin "C") (pinfunction "C_C") (pintype "passive"))
      (node (ref "IC306") (pin "2") (pinfunction "OC_2") (pintype "passive"))
      (node (ref "R405") (pin "1") (pinfunction "1_1") (pintype "passive"))
      (node (ref "R425") (pin "2") (pinfunction "2_2") (pintype "passive"))
    )
    (net (code "193") (name "QB_GATE") (class "Default")
      (node (ref "C353") (pin "2") (pinfunction "2_2") (pintype "passive"))
      (node (ref "IC307") (pin "7") (pinfunction "CLAMPI_7") (pintype "passive"))
      (node (ref "R304") (pin "1") (pinfunction "1_1") (pintype "passive"))
      (node (ref "R313") (pin "1") (pinfunction "1_1") (pintype "passive"))
      (node (ref "R328") (pin "2") (pinfunction "2_2") (pintype "passive"))
      (node (ref "T304") (pin "1") (pinfunction "G_1") (pintype "passive"))
    )
    (net (code "194") (name "QB_OC") (class "Default")
      (node (ref "C345") (pin "2") (pinfunction "2_2") (pintype "passive"))
      (node (ref "D317") (pin "C") (pinfunction "C_C") (pintype "passive"))
      (node (ref "IC307") (pin "2") (pinfunction "OC_2") (pintype "passive"))
      (node (ref "R411") (pin "1") (pinfunction "1_1") (pintype "passive"))
      (node (ref "R426") (pin "2") (pinfunction "2_2") (pintype "passive"))
    )
    (net (code "195") (name "QC_GATE") (class "Default")
      (node (ref "C351") (pin "2") (pinfunction "2_2") (pintype "passive"))
      (node (ref "IC310") (pin "7") (pinfunction "CLAMPI_7") (pintype "passive"))
      (node (ref "R312") (pin "2") (pinfunction "2_2") (pintype "passive"))
      (node (ref "R332") (pin "1") (pinfunction "1_1") (pintype "passive"))
      (node (ref "R385") (pin "1") (pinfunction "1_1") (pintype "passive"))
      (node (ref "T300") (pin "1") (pinfunction "G_1") (pintype "passive"))
    )
    (net (code "196") (name "QC_OC") (class "Default")
      (node (ref "C362") (pin "2") (pinfunction "2_2") (pintype "passive"))
      (node (ref "D319") (pin "C") (pinfunction "C_C") (pintype "passive"))
      (node (ref "IC310") (pin "2") (pinfunction "OC_2") (pintype "passive"))
      (node (ref "R412") (pin "2") (pinfunction "2_2") (pintype "passive"))
      (node (ref "R417") (pin "1") (pinfunction "1_1") (pintype "passive"))
    )
    (net (code "197") (name "QD_GATE") (class "Default")
      (node (ref "C352") (pin "2") (pinfunction "2_2") (pintype "passive"))
      (node (ref "IC311") (pin "7") (pinfunction "CLAMPI_7") (pintype "passive"))
      (node (ref "R331") (pin "2") (pinfunction "2_2") (pintype "passive"))
      (node (ref "R387") (pin "1") (pinfunction "1_1") (pintype "passive"))
      (node (ref "R396") (pin "1") (pinfunction "1_1") (pintype "passive"))
      (node (ref "T303") (pin "1") (pinfunction "G_1") (pintype "passive"))
    )
    (net (code "198") (name "QD_OC") (class "Default")
      (node (ref "C365") (pin "2") (pinfunction "2_2") (pintype "passive"))
      (node (ref "D320") (pin "C") (pinfunction "C_C") (pintype "passive"))
      (node (ref "IC311") (pin "2") (pinfunction "OC_2") (pintype "passive"))
      (node (ref "R423") (pin "1") (pinfunction "1_1") (pintype "passive"))
      (node (ref "R429") (pin "2") (pinfunction "2_2") (pintype "passive"))
    )
    (net (code "199") (name "RS485-A") (class "Default")
      (node (ref "IC500") (pin "6") (pinfunction "A_6") (pintype "bidirectional"))
      (node (ref "R523") (pin "1") (pinfunction "1_1") (pintype "passive"))
      (node (ref "R527") (pin "1") (pinfunction "1_1") (pintype "passive"))
      (node (ref "V503") (pin "2") (pinfunction "2_2") (pintype "passive"))
      (node (ref "X5") (pin "1") (pinfunction "1_1") (pintype "passive"))
    )
    (net (code "200") (name "RS485-A-NEXT") (class "Default")
      (node (ref "R527") (pin "2") (pinfunction "2_2") (pintype "passive"))
      (node (ref "X6") (pin "1") (pinfunction "1_1") (pintype "passive"))
    )
    (net (code "201") (name "RS485-B") (class "Default")
      (node (ref "IC500") (pin "7") (pinfunction "B_7") (pintype "bidirectional"))
      (node (ref "R521") (pin "1") (pinfunction "1_1") (pintype "passive"))
      (node (ref "R526") (pin "1") (pinfunction "1_1") (pintype "passive"))
      (node (ref "V504") (pin "2") (pinfunction "2_2") (pintype "passive"))
      (node (ref "X5") (pin "2") (pinfunction "2_2") (pintype "passive"))
    )
    (net (code "202") (name "RS485-B-NEXT") (class "Default")
      (node (ref "R526") (pin "2") (pinfunction "2_2") (pintype "passive"))
      (node (ref "X6") (pin "2") (pinfunction "2_2") (pintype "passive"))
    )
    (net (code "203") (name "SS-EN") (class "Default")
      (node (ref "C324") (pin "2") (pinfunction "2_2") (pintype "passive"))
      (node (ref "IC1") (pin "5") (pinfunction "SS/EN_5") (pintype "bidirectional"))
      (node (ref "Q300") (pin "3") (pinfunction "D_3") (pintype "passive"))
      (node (ref "R389") (pin "2") (pinfunction "2_2") (pintype "passive"))
    )
    (net (code "204") (name "VBATT") (class "Default")
      (node (ref "IC400") (pin "14") (pinfunction "VBATT_14") (pintype "power_in"))
    )
    (net (code "205") (name "VCC_USBHS") (class "Default")
      (node (ref "IC400") (pin "40") (pinfunction "VCC_USBHS_40") (pintype "power_in"))
    )
    (net (code "206") (name "VDDA_REG") (class "Default")
      (node (ref "C388") (pin "2") (pinfunction "2_2") (pintype "passive"))
      (node (ref "C389") (pin "2") (pinfunction "2_2") (pintype "passive"))
      (node (ref "C409") (pin "2") (pinfunction "2_2") (pintype "passive"))
      (node (ref "C413") (pin "1") (pinfunction "1_1") (pintype "passive"))
      (node (ref "C430") (pin "2") (pinfunction "2_2") (pintype "passive"))
      (node (ref "C431") (pin "2") (pinfunction "2_2") (pintype "passive"))
      (node (ref "C432") (pin "2") (pinfunction "2_2") (pintype "passive"))
      (node (ref "D321") (pin "A") (pinfunction "A_A") (pintype "passive"))
      (node (ref "IC306") (pin "5") (pinfunction "VDD_5") (pintype "passive"))
      (node (ref "IC308") (pin "6") (pinfunction "V+/1_6") (pintype "bidirectional"))
      (node (ref "IC308") (pin "7") (pinfunction "V+/2_7") (pintype "bidirectional"))
      (node (ref "IC312") (pin "2") (pinfunction "OUT_2") (pintype "power_in"))
      (node (ref "IC312") (pin "4") (pinfunction "TAB_4") (pintype "power_in"))
      (node (ref "R397") (pin "1") (pinfunction "1_1") (pintype "passive"))
      (node (ref "R430") (pin "2") (pinfunction "2_2") (pintype "passive"))
    )
    (net (code "207") (name "VDDC_REG") (class "Default")
      (node (ref "C384") (pin "2") (pinfunction "2_2") (pintype "passive"))
      (node (ref "C385") (pin "2") (pinfunction "2_2") (pintype "passive"))
      (node (ref "C395") (pin "2") (pinfunction "2_2") (pintype "passive"))
      (node (ref "C410") (pin "2") (pinfunction "2_2") (pintype "passive"))
      (node (ref "C414") (pin "1") (pinfunction "1_1") (pintype "passive"))
      (node (ref "C434") (pin "2") (pinfunction "2_2") (pintype "passive"))
      (node (ref "C435") (pin "2") (pinfunction "2_2") (pintype "passive"))
      (node (ref "C436") (pin "2") (pinfunction "2_2") (pintype "passive"))
      (node (ref "D322") (pin "A") (pinfunction "A_A") (pintype "passive"))
      (node (ref "IC309") (pin "6") (pinfunction "V+/1_6") (pintype "bidirectional"))
      (node (ref "IC309") (pin "7") (pinfunction "V+/2_7") (pintype "bidirectional"))
      (node (ref "IC310") (pin "5") (pinfunction "VDD_5") (pintype "passive"))
      (node (ref "IC313") (pin "2") (pinfunction "OUT_2") (pintype "power_in"))
      (node (ref "IC313") (pin "4") (pinfunction "TAB_4") (pintype "power_in"))
      (node (ref "R428") (pin "1") (pinfunction "1_1") (pintype "passive"))
      (node (ref "R431") (pin "2") (pinfunction "2_2") (pintype "passive"))
    )
    (net (code "208") (name "VDD_A") (class "Default")
      (node (ref "C330") (pin "1") (pinfunction "1_1") (pintype "passive"))
      (node (ref "C331") (pin "1") (pinfunction "1_1") (pintype "passive"))
      (node (ref "C358") (pin "1") (pinfunction "1_1") (pintype "passive"))
      (node (ref "C411") (pin "2") (pinfunction "2_2") (pintype "passive"))
      (node (ref "C427") (pin "1") (pinfunction "1_1") (pintype "passive"))
      (node (ref "D313") (pin "K") (pinfunction "C_K") (pintype "passive"))
      (node (ref "D321") (pin "C") (pinfunction "C_C") (pintype "passive"))
      (node (ref "IC312") (pin "3") (pinfunction "IN_3") (pintype "power_in"))
    )
    (net (code "209") (name "VDD_C") (class "Default")
      (node (ref "C357") (pin "1") (pinfunction "1_1") (pintype "passive"))
      (node (ref "C386") (pin "1") (pinfunction "1_1") (pintype "passive"))
      (node (ref "C412") (pin "2") (pinfunction "2_2") (pintype "passive"))
      (node (ref "C428") (pin "1") (pinfunction "1_1") (pintype "passive"))
      (node (ref "C429") (pin "1") (pinfunction "1_1") (pintype "passive"))
      (node (ref "D314") (pin "K") (pinfunction "C_K") (pintype "passive"))
      (node (ref "D322") (pin "C") (pinfunction "C_C") (pintype "passive"))
      (node (ref "IC313") (pin "3") (pinfunction "IN_3") (pintype "power_in"))
    )
    (net (code "210") (name "VEE_A") (class "Default")
      (node (ref "C339") (pin "2") (pinfunction "2_2") (pintype "passive"))
      (node (ref "C340") (pin "2") (pinfunction "2_2") (pintype "passive"))
      (node (ref "C390") (pin "2") (pinfunction "2_2") (pintype "passive"))
      (node (ref "C391") (pin "2") (pinfunction "2_2") (pintype "passive"))
      (node (ref "D316") (pin "2") (pinfunction "A_2") (pintype "passive"))
      (node (ref "IC306") (pin "8") (pinfunction "VEE_8") (pintype "passive"))
      (node (ref "IC308") (pin "1") (pinfunction "OUT_1") (pintype "bidirectional"))
      (node (ref "R399") (pin "1") (pinfunction "1_1") (pintype "passive"))
    )
    (net (code "211") (name "VEE_C") (class "Default")
      (node (ref "C355") (pin "2") (pinfunction "2_2") (pintype "passive"))
      (node (ref "C356") (pin "2") (pinfunction "2_2") (pintype "passive"))
      (node (ref "C396") (pin "2") (pinfunction "2_2") (pintype "passive"))
      (node (ref "C397") (pin "2") (pinfunction "2_2") (pintype "passive"))
      (node (ref "C398") (pin "2") (pinfunction "2_2") (pintype "passive"))
      (node (ref "C399") (pin "2") (pinfunction "2_2") (pintype "passive"))
      (node (ref "D318") (pin "2") (pinfunction "A_2") (pintype "passive"))
      (node (ref "IC309") (pin "1") (pinfunction "OUT_1") (pintype "bidirectional"))
      (node (ref "IC310") (pin "8") (pinfunction "VEE_8") (pintype "passive"))
      (node (ref "R402") (pin "1") (pinfunction "1_1") (pintype "passive"))
    )
    (net (code "212") (name "VREF") (class "Default")
      (node (ref "C319") (pin "1") (pinfunction "1_1") (pintype "passive"))
      (node (ref "IC1") (pin "1") (pinfunction "VREF_1") (pintype "bidirectional"))
      (node (ref "R352") (pin "1") (pinfunction "1_1") (pintype "passive"))
      (node (ref "R368") (pin "2") (pinfunction "2_2") (pintype "passive"))
      (node (ref "R369") (pin "2") (pinfunction "2_2") (pintype "passive"))
      (node (ref "R374") (pin "1") (pinfunction "1_1") (pintype "passive"))
    )
    (net (code "213") (name "VREFH0") (class "Default")
      (node (ref "IC400") (pin "130") (pinfunction "VREFH0_130") (pintype "power_in"))
    )
    (net (code "214") (name "VREFL0") (class "Default")
      (node (ref "IC400") (pin "129") (pinfunction "VREFL0_129") (pintype "power_in"))
    )
    (net (code "215") (name "VSS_USB") (class "Default")
      (node (ref "IC400") (pin "37") (pinfunction "VSS_USB_37") (pintype "power_in"))
    )
    (net (code "216") (name "V_-5V0_AUX") (class "Default")
      (node (ref "C210") (pin "2") (pinfunction "2_2") (pintype "passive"))
      (node (ref "C211") (pin "2") (pinfunction "-_2") (pintype "passive"))
      (node (ref "C349") (pin "2") (pinfunction "2_2") (pintype "passive"))
      (node (ref "C350") (pin "2") (pinfunction "2_2") (pintype "passive"))
      (node (ref "C368") (pin "2") (pinfunction "2_2") (pintype "passive"))
      (node (ref "C369") (pin "2") (pinfunction "2_2") (pintype "passive"))
      (node (ref "C392") (pin "2") (pinfunction "2_2") (pintype "passive"))
      (node (ref "C408") (pin "2") (pinfunction "2_2") (pintype "passive"))
      (node (ref "IC307") (pin "8") (pinfunction "VEE_8") (pintype "passive"))
      (node (ref "IC311") (pin "8") (pinfunction "VEE_8") (pintype "passive"))
      (node (ref "X205") (pin "6") (pinfunction "6_6") (pintype "passive"))
    )
    (net (code "217") (name "V_3V3") (class "Default")
      (node (ref "C202") (pin "1") (pinfunction "+_1") (pintype "passive"))
      (node (ref "C203") (pin "2") (pinfunction "2_2") (pintype "passive"))
      (node (ref "C323") (pin "2") (pinfunction "2_2") (pintype "passive"))
      (node (ref "C325") (pin "1") (pinfunction "1_1") (pintype "passive"))
      (node (ref "C328") (pin "2") (pinfunction "2_2") (pintype "passive"))
      (node (ref "C329") (pin "2") (pinfunction "2_2") (pintype "passive"))
      (node (ref "C334") (pin "2") (pinfunction "2_2") (pintype "passive"))
      (node (ref "C347") (pin "1") (pinfunction "1_1") (pintype "passive"))
      (node (ref "C402") (pin "2") (pinfunction "2_2") (pintype "passive"))
      (node (ref "C439") (pin "2") (pinfunction "2_2") (pintype "passive"))
      (node (ref "C440") (pin "1") (pinfunction "1_1") (pintype "passive"))
      (node (ref "C441") (pin "1") (pinfunction "1_1") (pintype "passive"))
      (node (ref "C442") (pin "2") (pinfunction "2_2") (pintype "passive"))
      (node (ref "C443") (pin "2") (pinfunction "2_2") (pintype "passive"))
      (node (ref "C444") (pin "2") (pinfunction "2_2") (pintype "passive"))
      (node (ref "C445") (pin "1") (pinfunction "1_1") (pintype "passive"))
      (node (ref "C446") (pin "1") (pinfunction "1_1") (pintype "passive"))
      (node (ref "C447") (pin "1") (pinfunction "1_1") (pintype "passive"))
      (node (ref "C448") (pin "2") (pinfunction "2_2") (pintype "passive"))
      (node (ref "C449") (pin "2") (pinfunction "2_2") (pintype "passive"))
      (node (ref "C453") (pin "1") (pinfunction "1_1") (pintype "passive"))
      (node (ref "C454") (pin "1") (pinfunction "1_1") (pintype "passive"))
      (node (ref "C455") (pin "1") (pinfunction "1_1") (pintype "passive"))
      (node (ref "C456") (pin "1") (pinfunction "1_1") (pintype "passive"))
      (node (ref "C457") (pin "1") (pinfunction "1_1") (pintype "passive"))
      (node (ref "C458") (pin "1") (pinfunction "1_1") (pintype "passive"))
      (node (ref "C503") (pin "2") (pinfunction "2_2") (pintype "passive"))
      (node (ref "D324") (pin "2") (pinfunction "C2_2") (pintype "passive"))
      (node (ref "IC301") (pin "5") (pinfunction "VCC_5") (pintype "passive"))
      (node (ref "IC400") (pin "111") (pinfunction "VCC_5_111") (pintype "power_in"))
      (node (ref "IC400") (pin "121") (pinfunction "VCC_6_121") (pintype "power_in"))
      (node (ref "IC400") (pin "126") (pinfunction "VREFH_126") (pintype "power_in"))
      (node (ref "IC400") (pin "127") (pinfunction "AVCC0_127") (pintype "power_in"))
      (node (ref "IC400") (pin "142") (pinfunction "VCC_142") (pintype "power_in"))
      (node (ref "IC400") (pin "21") (pinfunction "VCC_2_21") (pintype "power_in"))
      (node (ref "IC400") (pin "49") (pinfunction "VCC_3_49") (pintype "power_in"))
      (node (ref "IC400") (pin "68") (pinfunction "VCC_68") (pintype "power_in"))
      (node (ref "IC400") (pin "81") (pinfunction "VCC_2_81") (pintype "power_in"))
      (node (ref "IC400") (pin "90") (pinfunction "VCC_3_90") (pintype "power_in"))
      (node (ref "IC400") (pin "99") (pinfunction "VCC_4_99") (pintype "power_in"))
      (node (ref "L302") (pin "1") (pinfunction "P$1_1") (pintype "bidirectional"))
      (node (ref "L304") (pin "1") (pinfunction "P$1_1") (pintype "bidirectional"))
      (node (ref "L308") (pin "1") (pinfunction "P$1_1") (pintype "bidirectional"))
      (node (ref "L309") (pin "1") (pinfunction "P$1_1") (pintype "bidirectional"))
      (node (ref "R443") (pin "2") (pinfunction "2_2") (pintype "passive"))
      (node (ref "R444") (pin "2") (pinfunction "2_2") (pintype "passive"))
      (node (ref "R445") (pin "2") (pinfunction "2_2") (pintype "passive"))
      (node (ref "R446") (pin "2") (pinfunction "2_2") (pintype "passive"))
      (node (ref "R447") (pin "2") (pinfunction "2_2") (pintype "passive"))
      (node (ref "R448") (pin "2") (pinfunction "2_2") (pintype "passive"))
      (node (ref "R449") (pin "1") (pinfunction "1_1") (pintype "passive"))
      (node (ref "R515") (pin "1") (pinfunction "1_1") (pintype "passive"))
      (node (ref "R516") (pin "1") (pinfunction "1_1") (pintype "passive"))
      (node (ref "T307") (pin "3") (pinfunction "D_3") (pintype "passive"))
      (node (ref "T308") (pin "3") (pinfunction "D_3") (pintype "passive"))
      (node (ref "T309") (pin "3") (pinfunction "D_3") (pintype "passive"))
      (node (ref "T310") (pin "3") (pinfunction "D_3") (pintype "passive"))
      (node (ref "X204") (pin "4") (pinfunction "4_4") (pintype "passive"))
      (node (ref "X400") (pin "3") (pinfunction "3_3") (pintype "bidirectional"))
      (node (ref "X403") (pin "2") (pinfunction "2_2") (pintype "bidirectional"))
      (node (ref "X403") (pin "4") (pinfunction "4_4") (pintype "bidirectional"))
    )
    (net (code "218") (name "V_5V0") (class "Default")
      (node (ref "C200") (pin "2") (pinfunction "2_2") (pintype "passive"))
      (node (ref "C201") (pin "1") (pinfunction "+_1") (pintype "passive"))
      (node (ref "C346") (pin "1") (pinfunction "1_1") (pintype "passive"))
      (node (ref "C348") (pin "1") (pinfunction "1_1") (pintype "passive"))
      (node (ref "C504") (pin "2") (pinfunction "2_2") (pintype "passive"))
      (node (ref "IC300") (pin "5") (pinfunction "VCC_5") (pintype "passive"))
      (node (ref "IC302") (pin "5") (pinfunction "VCC_5") (pintype "passive"))
      (node (ref "IC500") (pin "8") (pinfunction "VCC_8") (pintype "bidirectional"))
      (node (ref "Q500") (pin "3") (pinfunction "SOURCE_3") (pintype "passive"))
      (node (ref "Q502") (pin "3") (pinfunction "SOURCE_3") (pintype "passive"))
      (node (ref "Q504") (pin "3") (pinfunction "SOURCE_3") (pintype "passive"))
      (node (ref "R319") (pin "2") (pinfunction "2_2") (pintype "passive"))
      (node (ref "R343") (pin "2") (pinfunction "2_2") (pintype "passive"))
      (node (ref "R348") (pin "2") (pinfunction "2_2") (pintype "passive"))
      (node (ref "R500") (pin "2") (pinfunction "2_2") (pintype "passive"))
      (node (ref "R505") (pin "2") (pinfunction "2_2") (pintype "passive"))
      (node (ref "R512") (pin "2") (pinfunction "2_2") (pintype "passive"))
      (node (ref "X204") (pin "2") (pinfunction "2_2") (pintype "passive"))
    )
    (net (code "219") (name "V_12V0") (class "Default")
      (node (ref "C204") (pin "2") (pinfunction "2_2") (pintype "passive"))
      (node (ref "C205") (pin "1") (pinfunction "+_1") (pintype "passive"))
      (node (ref "C337") (pin "1") (pinfunction "1_1") (pintype "passive"))
      (node (ref "C338") (pin "2") (pinfunction "2_2") (pintype "passive"))
      (node (ref "D201") (pin "1") (pinfunction "A_1") (pintype "passive"))
      (node (ref "L300") (pin "2") (pinfunction "P$2_2") (pintype "bidirectional"))
      (node (ref "R108") (pin "1") (pinfunction "1_1") (pintype "passive"))
      (node (ref "R111") (pin "1") (pinfunction "1_1") (pintype "passive"))
      (node (ref "R113") (pin "1") (pinfunction "1_1") (pintype "passive"))
      (node (ref "R388") (pin "2") (pinfunction "2_2") (pintype "passive"))
      (node (ref "X204") (pin "1") (pinfunction "1_1") (pintype "passive"))
    )
    (net (code "220") (name "V_12V0_AUX") (class "Default")
      (node (ref "C206") (pin "2") (pinfunction "2_2") (pintype "passive"))
      (node (ref "C207") (pin "1") (pinfunction "+_1") (pintype "passive"))
      (node (ref "C335") (pin "2") (pinfunction "2_2") (pintype "passive"))
      (node (ref "C336") (pin "2") (pinfunction "2_2") (pintype "passive"))
      (node (ref "C366") (pin "2") (pinfunction "2_2") (pintype "passive"))
      (node (ref "C367") (pin "2") (pinfunction "2_2") (pintype "passive"))
      (node (ref "C382") (pin "2") (pinfunction "2_2") (pintype "passive"))
      (node (ref "C393") (pin "1") (pinfunction "+_1") (pintype "passive"))
      (node (ref "C394") (pin "2") (pinfunction "2_2") (pintype "passive"))
      (node (ref "D200") (pin "1") (pinfunction "A_1") (pintype "passive"))
      (node (ref "IC307") (pin "5") (pinfunction "VDD_5") (pintype "passive"))
      (node (ref "IC311") (pin "5") (pinfunction "VDD_5") (pintype "passive"))
      (node (ref "R372") (pin "2") (pinfunction "2_2") (pintype "passive"))
      (node (ref "R401") (pin "2") (pinfunction "2_2") (pintype "passive"))
      (node (ref "R406") (pin "1") (pinfunction "1_1") (pintype "passive"))
      (node (ref "R418") (pin "1") (pinfunction "1_1") (pintype "passive"))
      (node (ref "R424") (pin "2") (pinfunction "2_2") (pintype "passive"))
      (node (ref "R427") (pin "2") (pinfunction "2_2") (pintype "passive"))
      (node (ref "X205") (pin "1") (pinfunction "1_1") (pintype "passive"))
    )
    (net (code "221") (name "V_CS_F") (class "Default")
      (node (ref "C306") (pin "2") (pinfunction "2_2") (pintype "passive"))
      (node (ref "D324") (pin "3") (pinfunction "C1_A2_3") (pintype "passive"))
      (node (ref "IC1") (pin "15") (pinfunction "CS_15") (pintype "bidirectional"))
      (node (ref "R315") (pin "2") (pinfunction "2_2") (pintype "passive"))
      (node (ref "R363") (pin "1") (pinfunction "1_1") (pintype "passive"))
      (node (ref "R366") (pin "1") (pinfunction "1_1") (pintype "passive"))
    )
    (net (code "222") (name "V_RECT_F_MINUS") (class "Default")
      (node (ref "C103") (pin "2") (pinfunction "-_2") (pintype "passive"))
      (node (ref "C104") (pin "2") (pinfunction "-_2") (pintype "passive"))
      (node (ref "C106") (pin "2") (pinfunction "-_2") (pintype "passive"))
      (node (ref "C206") (pin "1") (pinfunction "1_1") (pintype "passive"))
      (node (ref "C207") (pin "2") (pinfunction "-_2") (pintype "passive"))
      (node (ref "C210") (pin "1") (pinfunction "1_1") (pintype "passive"))
      (node (ref "C211") (pin "1") (pinfunction "+_1") (pintype "passive"))
      (node (ref "C335") (pin "1") (pinfunction "1_1") (pintype "passive"))
      (node (ref "C336") (pin "1") (pinfunction "1_1") (pintype "passive"))
      (node (ref "C345") (pin "1") (pinfunction "1_1") (pintype "passive"))
      (node (ref "C349") (pin "1") (pinfunction "1_1") (pintype "passive"))
      (node (ref "C350") (pin "1") (pinfunction "1_1") (pintype "passive"))
      (node (ref "C352") (pin "1") (pinfunction "1_1") (pintype "passive"))
      (node (ref "C353") (pin "1") (pinfunction "1_1") (pintype "passive"))
      (node (ref "C365") (pin "1") (pinfunction "1_1") (pintype "passive"))
      (node (ref "C366") (pin "1") (pinfunction "1_1") (pintype "passive"))
      (node (ref "C367") (pin "1") (pinfunction "1_1") (pintype "passive"))
      (node (ref "C368") (pin "1") (pinfunction "1_1") (pintype "passive"))
      (node (ref "C369") (pin "1") (pinfunction "1_1") (pintype "passive"))
      (node (ref "C382") (pin "1") (pinfunction "1_1") (pintype "passive"))
      (node (ref "C387") (pin "2") (pinfunction "2_2") (pintype "passive"))
      (node (ref "C392") (pin "1") (pinfunction "1_1") (pintype "passive"))
      (node (ref "C393") (pin "2") (pinfunction "-_2") (pintype "passive"))
      (node (ref "C394") (pin "1") (pinfunction "1_1") (pintype "passive"))
      (node (ref "C408") (pin "1") (pinfunction "1_1") (pintype "passive"))
      (node (ref "C424") (pin "1") (pinfunction "1_1") (pintype "passive"))
      (node (ref "C426") (pin "1") (pinfunction "1_1") (pintype "passive"))
      (node (ref "D101") (pin "3") (pinfunction "-_3") (pintype "bidirectional"))
      (node (ref "D104") (pin "A") (pinfunction "A_A") (pintype "passive"))
      (node (ref "D317") (pin "A") (pinfunction "A_A") (pintype "passive"))
      (node (ref "D320") (pin "A") (pinfunction "A_A") (pintype "passive"))
      (node (ref "IC100") (pin "2") (pinfunction "CATHODE_2") (pintype "passive"))
      (node (ref "IC307") (pin "3") (pinfunction "COM_3") (pintype "passive"))
      (node (ref "IC311") (pin "3") (pinfunction "COM_3") (pintype "passive"))
      (node (ref "R104") (pin "1") (pinfunction "1_1") (pintype "passive"))
      (node (ref "R110") (pin "1") (pinfunction "1_1") (pintype "passive"))
      (node (ref "R200") (pin "1") (pinfunction "1_1") (pintype "passive"))
      (node (ref "R328") (pin "1") (pinfunction "1_1") (pintype "passive"))
      (node (ref "R329") (pin "1") (pinfunction "1_1") (pintype "passive"))
      (node (ref "R330") (pin "1") (pinfunction "1_1") (pintype "passive"))
      (node (ref "R331") (pin "1") (pinfunction "1_1") (pintype "passive"))
      (node (ref "R398") (pin "1") (pinfunction "1_1") (pintype "passive"))
      (node (ref "R411") (pin "2") (pinfunction "2_2") (pintype "passive"))
      (node (ref "R423") (pin "2") (pinfunction "2_2") (pintype "passive"))
      (node (ref "T303") (pin "3") (pinfunction "S_3") (pintype "passive"))
      (node (ref "T304") (pin "3") (pinfunction "S_3") (pintype "passive"))
      (node (ref "X205") (pin "5") (pinfunction "5_5") (pintype "passive"))
    )
    (net (code "223") (name "V_RECT_F_PLUS") (class "Default")
      (node (ref "C100") (pin "1") (pinfunction "+_1") (pintype "passive"))
      (node (ref "C101") (pin "1") (pinfunction "+_1") (pintype "passive"))
      (node (ref "C105") (pin "1") (pinfunction "+_1") (pintype "passive"))
      (node (ref "D100") (pin "A") (pinfunction "A_A") (pintype "passive"))
      (node (ref "K100") (pin "3") (pinfunction "NO_3") (pintype "passive"))
      (node (ref "K101") (pin "3") (pinfunction "NO_3") (pintype "passive"))
      (node (ref "R100") (pin "2") (pinfunction "2_2") (pintype "passive"))
      (node (ref "R102") (pin "2") (pinfunction "2_2") (pintype "passive"))
      (node (ref "R112") (pin "2") (pinfunction "2_2") (pintype "passive"))
      (node (ref "U300") (pin "1") (pinfunction "P$1_1") (pintype "bidirectional"))
    )
    (net (code "224") (name "WELDER+") (class "Default")
      (node (ref "C415") (pin "1") (pinfunction "1_1") (pintype "passive"))
      (node (ref "C419") (pin "2") (pinfunction "2_2") (pintype "passive"))
      (node (ref "C420") (pin "2") (pinfunction "2_2") (pintype "passive"))
      (node (ref "D307") (pin "2") (pinfunction "2_2") (pintype "passive"))
      (node (ref "D308") (pin "2") (pinfunction "2_2") (pintype "passive"))
      (node (ref "D309") (pin "2") (pinfunction "2_2") (pintype "passive"))
      (node (ref "D310") (pin "2") (pinfunction "2_2") (pintype "passive"))
      (node (ref "D311") (pin "2") (pinfunction "2_2") (pintype "passive"))
      (node (ref "D312") (pin "2") (pinfunction "2_2") (pintype "passive"))
      (node (ref "D323") (pin "A") (pinfunction "A_A") (pintype "passive"))
      (node (ref "V300") (pin "2") (pinfunction "2_2") (pintype "passive"))
      (node (ref "X2") (pin "1") (pinfunction "P$1_1") (pintype "bidirectional"))
      (node (ref "X2") (pin "1-1") (pinfunction "P$1_1-1") (pintype "bidirectional"))
      (node (ref "X2") (pin "1-10") (pinfunction "P$1_1-10") (pintype "bidirectional"))
      (node (ref "X2") (pin "1-11") (pinfunction "P$1_1-11") (pintype "bidirectional"))
      (node (ref "X2") (pin "1-12") (pinfunction "P$1_1-12") (pintype "bidirectional"))
      (node (ref "X2") (pin "1-13") (pinfunction "P$1_1-13") (pintype "bidirectional"))
      (node (ref "X2") (pin "1-14") (pinfunction "P$1_1-14") (pintype "bidirectional"))
      (node (ref "X2") (pin "1-15") (pinfunction "P$1_1-15") (pintype "bidirectional"))
      (node (ref "X2") (pin "1-16") (pinfunction "P$1_1-16") (pintype "bidirectional"))
      (node (ref "X2") (pin "1-17") (pinfunction "P$1_1-17") (pintype "bidirectional"))
      (node (ref "X2") (pin "1-18") (pinfunction "P$1_1-18") (pintype "bidirectional"))
      (node (ref "X2") (pin "1-19") (pinfunction "P$1_1-19") (pintype "bidirectional"))
      (node (ref "X2") (pin "1-2") (pinfunction "P$1_1-2") (pintype "bidirectional"))
      (node (ref "X2") (pin "1-20") (pinfunction "P$1_1-20") (pintype "bidirectional"))
      (node (ref "X2") (pin "1-21") (pinfunction "P$1_1-21") (pintype "bidirectional"))
      (node (ref "X2") (pin "1-22") (pinfunction "P$1_1-22") (pintype "bidirectional"))
      (node (ref "X2") (pin "1-23") (pinfunction "P$1_1-23") (pintype "bidirectional"))
      (node (ref "X2") (pin "1-24") (pinfunction "P$1_1-24") (pintype "bidirectional"))
      (node (ref "X2") (pin "1-25") (pinfunction "P$1_1-25") (pintype "bidirectional"))
      (node (ref "X2") (pin "1-26") (pinfunction "P$1_1-26") (pintype "bidirectional"))
      (node (ref "X2") (pin "1-27") (pinfunction "P$1_1-27") (pintype "bidirectional"))
      (node (ref "X2") (pin "1-28") (pinfunction "P$1_1-28") (pintype "bidirectional"))
      (node (ref "X2") (pin "1-29") (pinfunction "P$1_1-29") (pintype "bidirectional"))
      (node (ref "X2") (pin "1-3") (pinfunction "P$1_1-3") (pintype "bidirectional"))
      (node (ref "X2") (pin "1-30") (pinfunction "P$1_1-30") (pintype "bidirectional"))
      (node (ref "X2") (pin "1-31") (pinfunction "P$1_1-31") (pintype "bidirectional"))
      (node (ref "X2") (pin "1-32") (pinfunction "P$1_1-32") (pintype "bidirectional"))
      (node (ref "X2") (pin "1-33") (pinfunction "P$1_1-33") (pintype "bidirectional"))
      (node (ref "X2") (pin "1-34") (pinfunction "P$1_1-34") (pintype "bidirectional"))
      (node (ref "X2") (pin "1-35") (pinfunction "P$1_1-35") (pintype "bidirectional"))
      (node (ref "X2") (pin "1-4") (pinfunction "P$1_1-4") (pintype "bidirectional"))
      (node (ref "X2") (pin "1-5") (pinfunction "P$1_1-5") (pintype "bidirectional"))
      (node (ref "X2") (pin "1-6") (pinfunction "P$1_1-6") (pintype "bidirectional"))
      (node (ref "X2") (pin "1-7") (pinfunction "P$1_1-7") (pintype "bidirectional"))
      (node (ref "X2") (pin "1-8") (pinfunction "P$1_1-8") (pintype "bidirectional"))
      (node (ref "X2") (pin "1-9") (pinfunction "P$1_1-9") (pintype "bidirectional"))
    )
    (net (code "225") (name "WELDER-") (class "Default")
      (node (ref "R335") (pin "1") (pinfunction "1_1") (pintype "passive"))
      (node (ref "R340") (pin "2") (pinfunction "2_2") (pintype "passive"))
      (node (ref "V300") (pin "1") (pinfunction "1_1") (pintype "passive"))
      (node (ref "X4") (pin "1") (pinfunction "P$1_1") (pintype "bidirectional"))
      (node (ref "X4") (pin "1-1") (pinfunction "P$1_1-1") (pintype "bidirectional"))
      (node (ref "X4") (pin "1-10") (pinfunction "P$1_1-10") (pintype "bidirectional"))
      (node (ref "X4") (pin "1-11") (pinfunction "P$1_1-11") (pintype "bidirectional"))
      (node (ref "X4") (pin "1-12") (pinfunction "P$1_1-12") (pintype "bidirectional"))
      (node (ref "X4") (pin "1-13") (pinfunction "P$1_1-13") (pintype "bidirectional"))
      (node (ref "X4") (pin "1-14") (pinfunction "P$1_1-14") (pintype "bidirectional"))
      (node (ref "X4") (pin "1-15") (pinfunction "P$1_1-15") (pintype "bidirectional"))
      (node (ref "X4") (pin "1-16") (pinfunction "P$1_1-16") (pintype "bidirectional"))
      (node (ref "X4") (pin "1-17") (pinfunction "P$1_1-17") (pintype "bidirectional"))
      (node (ref "X4") (pin "1-18") (pinfunction "P$1_1-18") (pintype "bidirectional"))
      (node (ref "X4") (pin "1-19") (pinfunction "P$1_1-19") (pintype "bidirectional"))
      (node (ref "X4") (pin "1-2") (pinfunction "P$1_1-2") (pintype "bidirectional"))
      (node (ref "X4") (pin "1-20") (pinfunction "P$1_1-20") (pintype "bidirectional"))
      (node (ref "X4") (pin "1-21") (pinfunction "P$1_1-21") (pintype "bidirectional"))
      (node (ref "X4") (pin "1-22") (pinfunction "P$1_1-22") (pintype "bidirectional"))
      (node (ref "X4") (pin "1-23") (pinfunction "P$1_1-23") (pintype "bidirectional"))
      (node (ref "X4") (pin "1-24") (pinfunction "P$1_1-24") (pintype "bidirectional"))
      (node (ref "X4") (pin "1-25") (pinfunction "P$1_1-25") (pintype "bidirectional"))
      (node (ref "X4") (pin "1-26") (pinfunction "P$1_1-26") (pintype "bidirectional"))
      (node (ref "X4") (pin "1-27") (pinfunction "P$1_1-27") (pintype "bidirectional"))
      (node (ref "X4") (pin "1-28") (pinfunction "P$1_1-28") (pintype "bidirectional"))
      (node (ref "X4") (pin "1-29") (pinfunction "P$1_1-29") (pintype "bidirectional"))
      (node (ref "X4") (pin "1-3") (pinfunction "P$1_1-3") (pintype "bidirectional"))
      (node (ref "X4") (pin "1-30") (pinfunction "P$1_1-30") (pintype "bidirectional"))
      (node (ref "X4") (pin "1-31") (pinfunction "P$1_1-31") (pintype "bidirectional"))
      (node (ref "X4") (pin "1-32") (pinfunction "P$1_1-32") (pintype "bidirectional"))
      (node (ref "X4") (pin "1-33") (pinfunction "P$1_1-33") (pintype "bidirectional"))
      (node (ref "X4") (pin "1-34") (pinfunction "P$1_1-34") (pintype "bidirectional"))
      (node (ref "X4") (pin "1-35") (pinfunction "P$1_1-35") (pintype "bidirectional"))
      (node (ref "X4") (pin "1-4") (pinfunction "P$1_1-4") (pintype "bidirectional"))
      (node (ref "X4") (pin "1-5") (pinfunction "P$1_1-5") (pintype "bidirectional"))
      (node (ref "X4") (pin "1-6") (pinfunction "P$1_1-6") (pintype "bidirectional"))
      (node (ref "X4") (pin "1-7") (pinfunction "P$1_1-7") (pintype "bidirectional"))
      (node (ref "X4") (pin "1-8") (pinfunction "P$1_1-8") (pintype "bidirectional"))
      (node (ref "X4") (pin "1-9") (pinfunction "P$1_1-9") (pintype "bidirectional"))
    )
    (net (code "226") (name "unconnected-(IC1-OUTE-Pad18)") (class "Default")
      (node (ref "IC1") (pin "18") (pinfunction "OUTE_18") (pintype "bidirectional"))
    )
    (net (code "227") (name "unconnected-(IC1-OUTF-Pad17)") (class "Default")
      (node (ref "IC1") (pin "17") (pinfunction "OUTF_17") (pintype "bidirectional"))
    )
    (net (code "228") (name "unconnected-(IC306-AIN-Pad1)") (class "Default")
      (node (ref "IC306") (pin "1") (pinfunction "AIN_1") (pintype "passive"))
    )
    (net (code "229") (name "unconnected-(IC306-APWM-Pad16)") (class "Default")
      (node (ref "IC306") (pin "16") (pinfunction "APWM_16") (pintype "passive"))
    )
    (net (code "230") (name "unconnected-(IC307-AIN-Pad1)") (class "Default")
      (node (ref "IC307") (pin "1") (pinfunction "AIN_1") (pintype "passive"))
    )
    (net (code "231") (name "unconnected-(IC307-APWM-Pad16)") (class "Default")
      (node (ref "IC307") (pin "16") (pinfunction "APWM_16") (pintype "passive"))
    )
    (net (code "232") (name "unconnected-(IC310-AIN-Pad1)") (class "Default")
      (node (ref "IC310") (pin "1") (pinfunction "AIN_1") (pintype "passive"))
    )
    (net (code "233") (name "unconnected-(IC310-APWM-Pad16)") (class "Default")
      (node (ref "IC310") (pin "16") (pinfunction "APWM_16") (pintype "passive"))
    )
    (net (code "234") (name "unconnected-(IC311-AIN-Pad1)") (class "Default")
      (node (ref "IC311") (pin "1") (pinfunction "AIN_1") (pintype "passive"))
    )
    (net (code "235") (name "unconnected-(IC311-APWM-Pad16)") (class "Default")
      (node (ref "IC311") (pin "16") (pinfunction "APWM_16") (pintype "passive"))
    )
    (net (code "236") (name "unconnected-(IC400A-P200-Pad57)") (class "Default")
      (node (ref "IC400") (pin "57") (pinfunction "P200_57") (pintype "bidirectional"))
    )
    (net (code "237") (name "unconnected-(IC400A-P201{slash}MD-Pad56)") (class "Default")
      (node (ref "IC400") (pin "56") (pinfunction "P201/MD_56") (pintype "bidirectional"))
    )
    (net (code "238") (name "unconnected-(IC400A-P202-Pad46)") (class "Default")
      (node (ref "IC400") (pin "46") (pinfunction "P202_46") (pintype "bidirectional"))
    )
    (net (code "239") (name "unconnected-(IC400A-P203-Pad45)") (class "Default")
      (node (ref "IC400") (pin "45") (pinfunction "P203_45") (pintype "bidirectional"))
    )
    (net (code "240") (name "unconnected-(IC400A-P204-Pad44)") (class "Default")
      (node (ref "IC400") (pin "44") (pinfunction "P204_44") (pintype "bidirectional"))
    )
    (net (code "241") (name "unconnected-(IC400A-P205-Pad43)") (class "Default")
      (node (ref "IC400") (pin "43") (pinfunction "P205_43") (pintype "bidirectional"))
    )
    (net (code "242") (name "unconnected-(IC400A-P206-Pad42)") (class "Default")
      (node (ref "IC400") (pin "42") (pinfunction "P206_42") (pintype "bidirectional"))
    )
    (net (code "243") (name "unconnected-(IC400A-P207-Pad41)") (class "Default")
      (node (ref "IC400") (pin "41") (pinfunction "P207_41") (pintype "bidirectional"))
    )
    (net (code "244") (name "unconnected-(IC400A-P208-Pad54)") (class "Default")
      (node (ref "IC400") (pin "54") (pinfunction "P208_54") (pintype "bidirectional"))
    )
    (net (code "245") (name "unconnected-(IC400A-P209-Pad53)") (class "Default")
      (node (ref "IC400") (pin "53") (pinfunction "P209_53") (pintype "bidirectional"))
    )
    (net (code "246") (name "unconnected-(IC400A-P210-Pad52)") (class "Default")
      (node (ref "IC400") (pin "52") (pinfunction "P210_52") (pintype "bidirectional"))
    )
    (net (code "247") (name "unconnected-(IC400A-P211-Pad51)") (class "Default")
      (node (ref "IC400") (pin "51") (pinfunction "P211_51") (pintype "bidirectional"))
    )
    (net (code "248") (name "unconnected-(IC400A-P214-Pad50)") (class "Default")
      (node (ref "IC400") (pin "50") (pinfunction "P214_50") (pintype "bidirectional"))
    )
    (net (code "249") (name "unconnected-(IC400A-P308-Pad62)") (class "Default")
      (node (ref "IC400") (pin "62") (pinfunction "P308_62") (pintype "bidirectional"))
    )
    (net (code "250") (name "unconnected-(IC400A-P309-Pad61)") (class "Default")
      (node (ref "IC400") (pin "61") (pinfunction "P309_61") (pintype "bidirectional"))
    )
    (net (code "251") (name "unconnected-(IC400A-P310-Pad60)") (class "Default")
      (node (ref "IC400") (pin "60") (pinfunction "P310_60") (pintype "bidirectional"))
    )
    (net (code "252") (name "unconnected-(IC400A-P311-Pad59)") (class "Default")
      (node (ref "IC400") (pin "59") (pinfunction "P311_59") (pintype "bidirectional"))
    )
    (net (code "253") (name "unconnected-(IC400A-P312-Pad58)") (class "Default")
      (node (ref "IC400") (pin "58") (pinfunction "P312_58") (pintype "bidirectional"))
    )
    (net (code "254") (name "unconnected-(IC400A-P313-Pad47)") (class "Default")
      (node (ref "IC400") (pin "47") (pinfunction "P313_47") (pintype "bidirectional"))
    )
    (net (code "255") (name "unconnected-(IC400A-P400-Pad1)") (class "Default")
      (node (ref "IC400") (pin "1") (pinfunction "P400_1") (pintype "bidirectional"))
    )
    (net (code "256") (name "unconnected-(IC400A-P401-Pad2)") (class "Default")
      (node (ref "IC400") (pin "2") (pinfunction "P401_2") (pintype "bidirectional"))
    )
    (net (code "257") (name "unconnected-(IC400A-P402-Pad3)") (class "Default")
      (node (ref "IC400") (pin "3") (pinfunction "P402_3") (pintype "bidirectional"))
    )
    (net (code "258") (name "unconnected-(IC400A-P403-Pad4)") (class "Default")
      (node (ref "IC400") (pin "4") (pinfunction "P403_4") (pintype "bidirectional"))
    )
    (net (code "259") (name "unconnected-(IC400A-P404-Pad5)") (class "Default")
      (node (ref "IC400") (pin "5") (pinfunction "P404_5") (pintype "bidirectional"))
    )
    (net (code "260") (name "unconnected-(IC400A-P405-Pad6)") (class "Default")
      (node (ref "IC400") (pin "6") (pinfunction "P405_6") (pintype "bidirectional"))
    )
    (net (code "261") (name "unconnected-(IC400A-P406-Pad7)") (class "Default")
      (node (ref "IC400") (pin "7") (pinfunction "P406_7") (pintype "bidirectional"))
    )
    (net (code "262") (name "unconnected-(IC400A-P407-Pad36)") (class "Default")
      (node (ref "IC400") (pin "36") (pinfunction "P407_36") (pintype "bidirectional"))
    )
    (net (code "263") (name "unconnected-(IC400A-P412-Pad31)") (class "Default")
      (node (ref "IC400") (pin "31") (pinfunction "P412_31") (pintype "bidirectional"))
    )
    (net (code "264") (name "unconnected-(IC400A-P413-Pad30)") (class "Default")
      (node (ref "IC400") (pin "30") (pinfunction "P413_30") (pintype "bidirectional"))
    )
    (net (code "265") (name "unconnected-(IC400A-P414-Pad29)") (class "Default")
      (node (ref "IC400") (pin "29") (pinfunction "P414_29") (pintype "bidirectional"))
    )
    (net (code "266") (name "unconnected-(IC400A-P415-Pad28)") (class "Default")
      (node (ref "IC400") (pin "28") (pinfunction "P415_28") (pintype "bidirectional"))
    )
    (net (code "267") (name "unconnected-(IC400A-P700-Pad8)") (class "Default")
      (node (ref "IC400") (pin "8") (pinfunction "P700_8") (pintype "bidirectional"))
    )
    (net (code "268") (name "unconnected-(IC400A-P701-Pad9)") (class "Default")
      (node (ref "IC400") (pin "9") (pinfunction "P701_9") (pintype "bidirectional"))
    )
    (net (code "269") (name "unconnected-(IC400A-P702-Pad10)") (class "Default")
      (node (ref "IC400") (pin "10") (pinfunction "P702_10") (pintype "bidirectional"))
    )
    (net (code "270") (name "unconnected-(IC400A-P703-Pad11)") (class "Default")
      (node (ref "IC400") (pin "11") (pinfunction "P703_11") (pintype "bidirectional"))
    )
    (net (code "271") (name "unconnected-(IC400A-P704-Pad12)") (class "Default")
      (node (ref "IC400") (pin "12") (pinfunction "P704_12") (pintype "bidirectional"))
    )
    (net (code "272") (name "unconnected-(IC400A-P705-Pad13)") (class "Default")
      (node (ref "IC400") (pin "13") (pinfunction "P705_13") (pintype "bidirectional"))
    )
    (net (code "273") (name "unconnected-(IC400A-P708-Pad27)") (class "Default")
      (node (ref "IC400") (pin "27") (pinfunction "P708_27") (pintype "bidirectional"))
    )
    (net (code "274") (name "unconnected-(IC400A-P709-Pad26)") (class "Default")
      (node (ref "IC400") (pin "26") (pinfunction "P709_26") (pintype "bidirectional"))
    )
    (net (code "275") (name "unconnected-(IC400A-P710-Pad25)") (class "Default")
      (node (ref "IC400") (pin "25") (pinfunction "P710_25") (pintype "bidirectional"))
    )
    (net (code "276") (name "unconnected-(IC400A-P711-Pad24)") (class "Default")
      (node (ref "IC400") (pin "24") (pinfunction "P711_24") (pintype "bidirectional"))
    )
    (net (code "277") (name "unconnected-(IC400A-P712-Pad23)") (class "Default")
      (node (ref "IC400") (pin "23") (pinfunction "P712_23") (pintype "bidirectional"))
    )
    (net (code "278") (name "unconnected-(IC400A-P713-Pad22)") (class "Default")
      (node (ref "IC400") (pin "22") (pinfunction "P713_22") (pintype "bidirectional"))
    )
    (net (code "279") (name "unconnected-(IC400A-USB_DM-Pad38)") (class "Default")
      (node (ref "IC400") (pin "38") (pinfunction "USB_DM_38") (pintype "bidirectional"))
    )
    (net (code "280") (name "unconnected-(IC400A-USB_DP-Pad39)") (class "Default")
      (node (ref "IC400") (pin "39") (pinfunction "USB_DP_39") (pintype "bidirectional"))
    )
    (net (code "281") (name "unconnected-(IC400A-XCIN-Pad16)") (class "Default")
      (node (ref "IC400") (pin "16") (pinfunction "XCIN_16") (pintype "input"))
    )
    (net (code "282") (name "unconnected-(IC400A-XCOUT-Pad17)") (class "Default")
      (node (ref "IC400") (pin "17") (pinfunction "XCOUT_17") (pintype "output"))
    )
    (net (code "283") (name "unconnected-(IC400B-P000-Pad140)") (class "Default")
      (node (ref "IC400") (pin "140") (pinfunction "P000_140") (pintype "bidirectional"))
    )
    (net (code "284") (name "unconnected-(IC400B-P001-Pad139)") (class "Default")
      (node (ref "IC400") (pin "139") (pinfunction "P001_139") (pintype "bidirectional"))
    )
    (net (code "285") (name "unconnected-(IC400B-P002-Pad138)") (class "Default")
      (node (ref "IC400") (pin "138") (pinfunction "P002_138") (pintype "bidirectional"))
    )
    (net (code "286") (name "unconnected-(IC400B-P003-Pad137)") (class "Default")
      (node (ref "IC400") (pin "137") (pinfunction "P003_137") (pintype "bidirectional"))
    )
    (net (code "287") (name "unconnected-(IC400B-P004-Pad136)") (class "Default")
      (node (ref "IC400") (pin "136") (pinfunction "P004_136") (pintype "bidirectional"))
    )
    (net (code "288") (name "unconnected-(IC400B-P005-Pad135)") (class "Default")
      (node (ref "IC400") (pin "135") (pinfunction "P005_135") (pintype "bidirectional"))
    )
    (net (code "289") (name "unconnected-(IC400B-P006-Pad134)") (class "Default")
      (node (ref "IC400") (pin "134") (pinfunction "P006_134") (pintype "bidirectional"))
    )
    (net (code "290") (name "unconnected-(IC400B-P007-Pad133)") (class "Default")
      (node (ref "IC400") (pin "133") (pinfunction "P007_133") (pintype "bidirectional"))
    )
    (net (code "291") (name "unconnected-(IC400B-P008-Pad132)") (class "Default")
      (node (ref "IC400") (pin "132") (pinfunction "P008_132") (pintype "bidirectional"))
    )
    (net (code "292") (name "unconnected-(IC400B-P009-Pad131)") (class "Default")
      (node (ref "IC400") (pin "131") (pinfunction "P009_131") (pintype "bidirectional"))
    )
    (net (code "293") (name "unconnected-(IC400B-P014-Pad124)") (class "Default")
      (node (ref "IC400") (pin "124") (pinfunction "P014_124") (pintype "bidirectional"))
    )
    (net (code "294") (name "unconnected-(IC400B-P015-Pad123)") (class "Default")
      (node (ref "IC400") (pin "123") (pinfunction "P015_123") (pintype "bidirectional"))
    )
    (net (code "295") (name "unconnected-(IC400B-P100-Pad108)") (class "Default")
      (node (ref "IC400") (pin "108") (pinfunction "P100_108") (pintype "bidirectional"))
    )
    (net (code "296") (name "unconnected-(IC400B-P101-Pad107)") (class "Default")
      (node (ref "IC400") (pin "107") (pinfunction "P101_107") (pintype "bidirectional"))
    )
    (net (code "297") (name "unconnected-(IC400B-P102-Pad106)") (class "Default")
      (node (ref "IC400") (pin "106") (pinfunction "P102_106") (pintype "bidirectional"))
    )
    (net (code "298") (name "unconnected-(IC400B-P103-Pad105)") (class "Default")
      (node (ref "IC400") (pin "105") (pinfunction "P103_105") (pintype "bidirectional"))
    )
    (net (code "299") (name "unconnected-(IC400B-P104-Pad104)") (class "Default")
      (node (ref "IC400") (pin "104") (pinfunction "P104_104") (pintype "bidirectional"))
    )
    (net (code "300") (name "unconnected-(IC400B-P105-Pad103)") (class "Default")
      (node (ref "IC400") (pin "103") (pinfunction "P105_103") (pintype "bidirectional"))
    )
    (net (code "301") (name "unconnected-(IC400B-P106-Pad102)") (class "Default")
      (node (ref "IC400") (pin "102") (pinfunction "P106_102") (pintype "bidirectional"))
    )
    (net (code "302") (name "unconnected-(IC400B-P107-Pad101)") (class "Default")
      (node (ref "IC400") (pin "101") (pinfunction "P107_101") (pintype "bidirectional"))
    )
    (net (code "303") (name "unconnected-(IC400B-P111-Pad76)") (class "Default")
      (node (ref "IC400") (pin "76") (pinfunction "P111_76") (pintype "bidirectional"))
    )
    (net (code "304") (name "unconnected-(IC400B-P112-Pad77)") (class "Default")
      (node (ref "IC400") (pin "77") (pinfunction "P112_77") (pintype "bidirectional"))
    )
    (net (code "305") (name "unconnected-(IC400B-P113-Pad78)") (class "Default")
      (node (ref "IC400") (pin "78") (pinfunction "P113_78") (pintype "bidirectional"))
    )
    (net (code "306") (name "unconnected-(IC400B-P114-Pad79)") (class "Default")
      (node (ref "IC400") (pin "79") (pinfunction "P114_79") (pintype "bidirectional"))
    )
    (net (code "307") (name "unconnected-(IC400B-P115-Pad80)") (class "Default")
      (node (ref "IC400") (pin "80") (pinfunction "P115_80") (pintype "bidirectional"))
    )
    (net (code "308") (name "unconnected-(IC400B-P501-Pad114)") (class "Default")
      (node (ref "IC400") (pin "114") (pinfunction "P501_114") (pintype "bidirectional"))
    )
    (net (code "309") (name "unconnected-(IC400B-P502-Pad115)") (class "Default")
      (node (ref "IC400") (pin "115") (pinfunction "P502_115") (pintype "bidirectional"))
    )
    (net (code "310") (name "unconnected-(IC400B-P503-Pad116)") (class "Default")
      (node (ref "IC400") (pin "116") (pinfunction "P503_116") (pintype "bidirectional"))
    )
    (net (code "311") (name "unconnected-(IC400B-P504-Pad117)") (class "Default")
      (node (ref "IC400") (pin "117") (pinfunction "P504_117") (pintype "bidirectional"))
    )
    (net (code "312") (name "unconnected-(IC400B-P506-Pad119)") (class "Default")
      (node (ref "IC400") (pin "119") (pinfunction "P506_119") (pintype "bidirectional"))
    )
    (net (code "313") (name "unconnected-(IC400B-P507-Pad120)") (class "Default")
      (node (ref "IC400") (pin "120") (pinfunction "P507_120") (pintype "bidirectional"))
    )
    (net (code "314") (name "unconnected-(IC400B-P511-Pad144)") (class "Default")
      (node (ref "IC400") (pin "144") (pinfunction "P511_144") (pintype "bidirectional"))
    )
    (net (code "315") (name "unconnected-(IC400B-P512-Pad143)") (class "Default")
      (node (ref "IC400") (pin "143") (pinfunction "P512_143") (pintype "bidirectional"))
    )
    (net (code "316") (name "unconnected-(IC400B-P602-Pad96)") (class "Default")
      (node (ref "IC400") (pin "96") (pinfunction "P602_96") (pintype "bidirectional"))
    )
    (net (code "317") (name "unconnected-(IC400B-P603-Pad95)") (class "Default")
      (node (ref "IC400") (pin "95") (pinfunction "P603_95") (pintype "bidirectional"))
    )
    (net (code "318") (name "unconnected-(IC400B-P604-Pad94)") (class "Default")
      (node (ref "IC400") (pin "94") (pinfunction "P604_94") (pintype "bidirectional"))
    )
    (net (code "319") (name "unconnected-(IC400B-P608-Pad83)") (class "Default")
      (node (ref "IC400") (pin "83") (pinfunction "P608_83") (pintype "bidirectional"))
    )
    (net (code "320") (name "unconnected-(IC400B-P609-Pad84)") (class "Default")
      (node (ref "IC400") (pin "84") (pinfunction "P609_84") (pintype "bidirectional"))
    )
    (net (code "321") (name "unconnected-(IC400B-P800-Pad109)") (class "Default")
      (node (ref "IC400") (pin "109") (pinfunction "P800_109") (pintype "bidirectional"))
    )
    (net (code "322") (name "unconnected-(IC400B-P801-Pad110)") (class "Default")
      (node (ref "IC400") (pin "110") (pinfunction "P801_110") (pintype "bidirectional"))
    )
    (net (code "323") (name "unconnected-(X5-Pad3)") (class "Default")
      (node (ref "X5") (pin "3") (pinfunction "3_3") (pintype "passive"))
    )
    (net (code "324") (name "unconnected-(X5-Pad4)") (class "Default")
      (node (ref "X5") (pin "4") (pinfunction "4_4") (pintype "passive"))
    )
    (net (code "325") (name "unconnected-(X5-Pad5)") (class "Default")
      (node (ref "X5") (pin "5") (pinfunction "5_5") (pintype "passive"))
    )
    (net (code "326") (name "unconnected-(X5-Pad6)") (class "Default")
      (node (ref "X5") (pin "6") (pinfunction "6_6") (pintype "passive"))
    )
    (net (code "327") (name "unconnected-(X5-Pad7)") (class "Default")
      (node (ref "X5") (pin "7") (pinfunction "7_7") (pintype "passive"))
    )
    (net (code "328") (name "unconnected-(X5-Pad8)") (class "Default")
      (node (ref "X5") (pin "8") (pinfunction "8_8") (pintype "passive"))
    )
    (net (code "329") (name "unconnected-(X6-Pad3)") (class "Default")
      (node (ref "X6") (pin "3") (pinfunction "3_3") (pintype "passive"))
    )
    (net (code "330") (name "unconnected-(X6-Pad4)") (class "Default")
      (node (ref "X6") (pin "4") (pinfunction "4_4") (pintype "passive"))
    )
    (net (code "331") (name "unconnected-(X6-Pad5)") (class "Default")
      (node (ref "X6") (pin "5") (pinfunction "5_5") (pintype "passive"))
    )
    (net (code "332") (name "unconnected-(X6-Pad6)") (class "Default")
      (node (ref "X6") (pin "6") (pinfunction "6_6") (pintype "passive"))
    )
    (net (code "333") (name "unconnected-(X6-Pad7)") (class "Default")
      (node (ref "X6") (pin "7") (pinfunction "7_7") (pintype "passive"))
    )
    (net (code "334") (name "unconnected-(X6-Pad8)") (class "Default")
      (node (ref "X6") (pin "8") (pinfunction "8_8") (pintype "passive"))
    )
    (net (code "335") (name "unconnected-(X204-Pad3)") (class "Default")
      (node (ref "X204") (pin "3") (pinfunction "3_3") (pintype "passive"))
    )
    (net (code "336") (name "unconnected-(X205-Pad2)") (class "Default")
      (node (ref "X205") (pin "2") (pinfunction "2_2") (pintype "passive"))
    )
    (net (code "337") (name "unconnected-(X205-Pad3)") (class "Default")
      (node (ref "X205") (pin "3") (pinfunction "3_3") (pintype "passive"))
    )
    (net (code "338") (name "unconnected-(X205-Pad4)") (class "Default")
      (node (ref "X205") (pin "4") (pinfunction "4_4") (pintype "passive"))
    )
    (net (code "339") (name "{slash}DO_COMM_RX_EN") (class "Default")
      (node (ref "IC400") (pin "32") (pinfunction "P411_32") (pintype "bidirectional"))
      (node (ref "R520") (pin "2") (pinfunction "2_2") (pintype "passive"))
    )
    (net (code "340") (name "{slash}G_DRV_FAULTA") (class "Default")
      (node (ref "C371") (pin "2") (pinfunction "2_2") (pintype "passive"))
      (node (ref "C404") (pin "2") (pinfunction "2_2") (pintype "passive"))
      (node (ref "IC306") (pin "13") (pinfunction "/FLT_13") (pintype "passive"))
      (node (ref "IC400") (pin "89") (pinfunction "P614_89") (pintype "bidirectional"))
      (node (ref "R308") (pin "2") (pinfunction "2_2") (pintype "passive"))
      (node (ref "R445") (pin "1") (pinfunction "1_1") (pintype "passive"))
      (node (ref "X402") (pin "1") (pinfunction "1_1") (pintype "bidirectional"))
    )
    (net (code "341") (name "{slash}G_DRV_FAULTB") (class "Default")
      (node (ref "C374") (pin "2") (pinfunction "2_2") (pintype "passive"))
      (node (ref "C405") (pin "2") (pinfunction "2_2") (pintype "passive"))
      (node (ref "IC307") (pin "13") (pinfunction "/FLT_13") (pintype "passive"))
      (node (ref "IC400") (pin "88") (pinfunction "P613_88") (pintype "bidirectional"))
      (node (ref "R408") (pin "2") (pinfunction "2_2") (pintype "passive"))
      (node (ref "R443") (pin "1") (pinfunction "1_1") (pintype "passive"))
      (node (ref "X402") (pin "2") (pinfunction "2_2") (pintype "bidirectional"))
    )
    (net (code "342") (name "{slash}G_DRV_FAULTC") (class "Default")
      (node (ref "C377") (pin "2") (pinfunction "2_2") (pintype "passive"))
      (node (ref "C403") (pin "2") (pinfunction "2_2") (pintype "passive"))
      (node (ref "IC310") (pin "13") (pinfunction "/FLT_13") (pintype "passive"))
      (node (ref "IC400") (pin "87") (pinfunction "P612_87") (pintype "bidirectional"))
      (node (ref "R414") (pin "2") (pinfunction "2_2") (pintype "passive"))
      (node (ref "R446") (pin "1") (pinfunction "1_1") (pintype "passive"))
      (node (ref "X402") (pin "3") (pinfunction "3_3") (pintype "bidirectional"))
    )
    (net (code "343") (name "{slash}G_DRV_FAULTD") (class "Default")
      (node (ref "C380") (pin "2") (pinfunction "2_2") (pintype "passive"))
      (node (ref "C407") (pin "2") (pinfunction "2_2") (pintype "passive"))
      (node (ref "IC311") (pin "13") (pinfunction "/FLT_13") (pintype "passive"))
      (node (ref "IC400") (pin "86") (pinfunction "P611_86") (pintype "bidirectional"))
      (node (ref "R420") (pin "2") (pinfunction "2_2") (pintype "passive"))
      (node (ref "R444") (pin "1") (pinfunction "1_1") (pintype "passive"))
      (node (ref "X402") (pin "4") (pinfunction "4_4") (pintype "bidirectional"))
    )
  )
)
